# Titan_Teknic_v1p00a.net
KiCad netlist of a schematic drawn in EAGLE
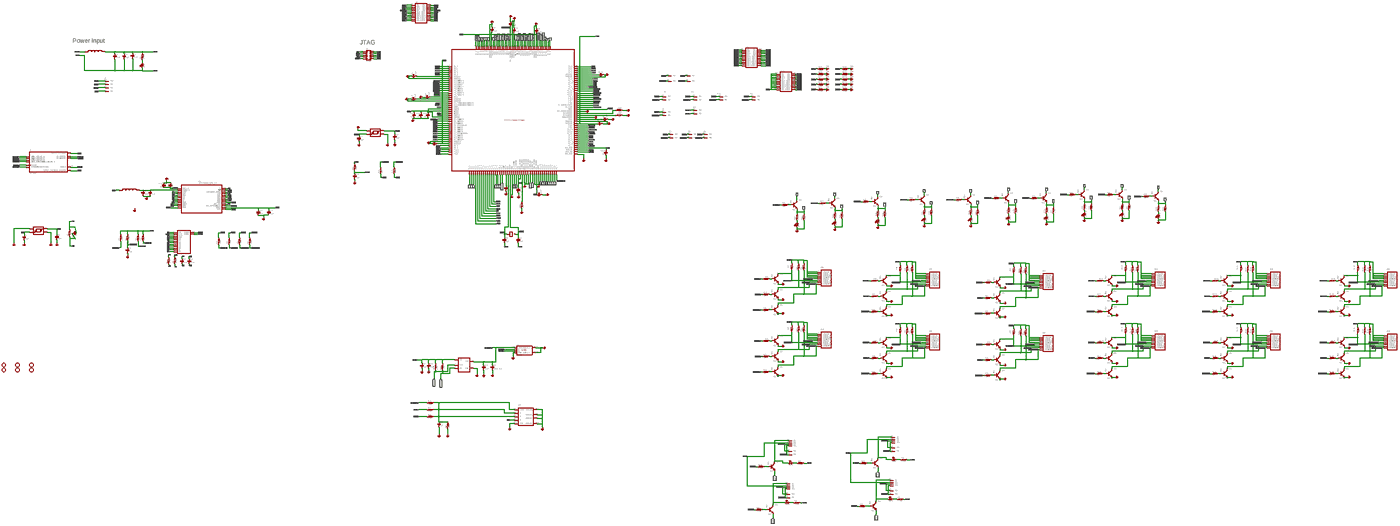
[diagram p0: schematic, sheet 1, overview]
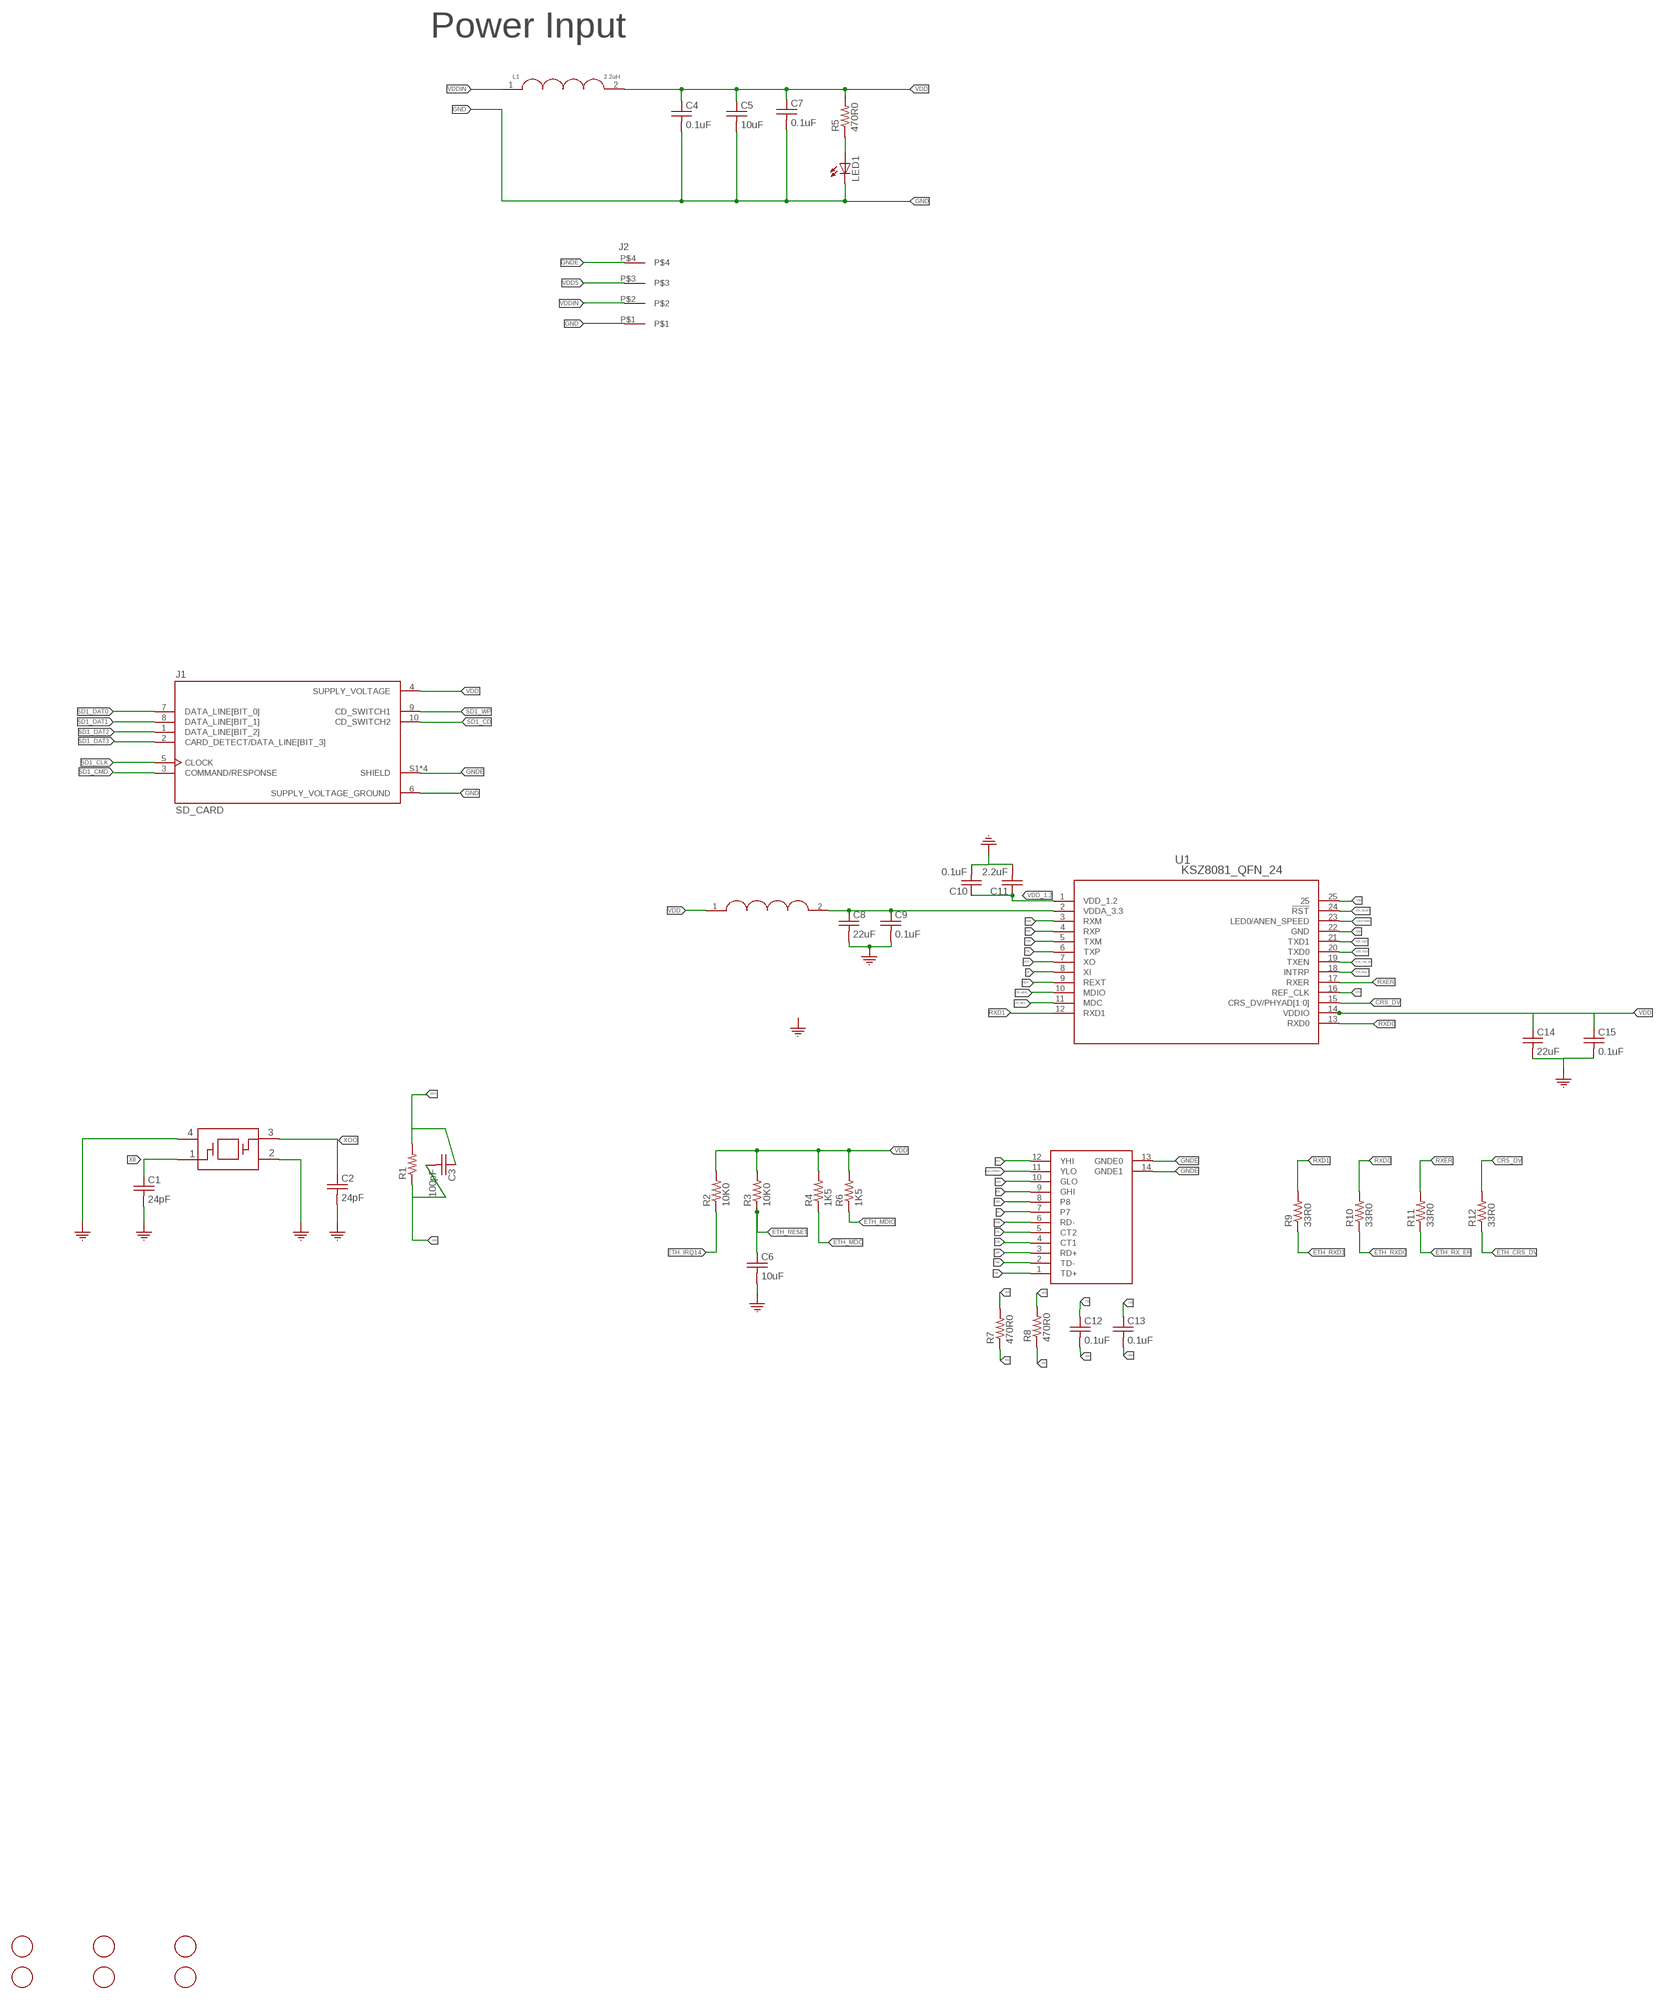
[diagram p1: schematic, sheet 1, part 1 of 6]
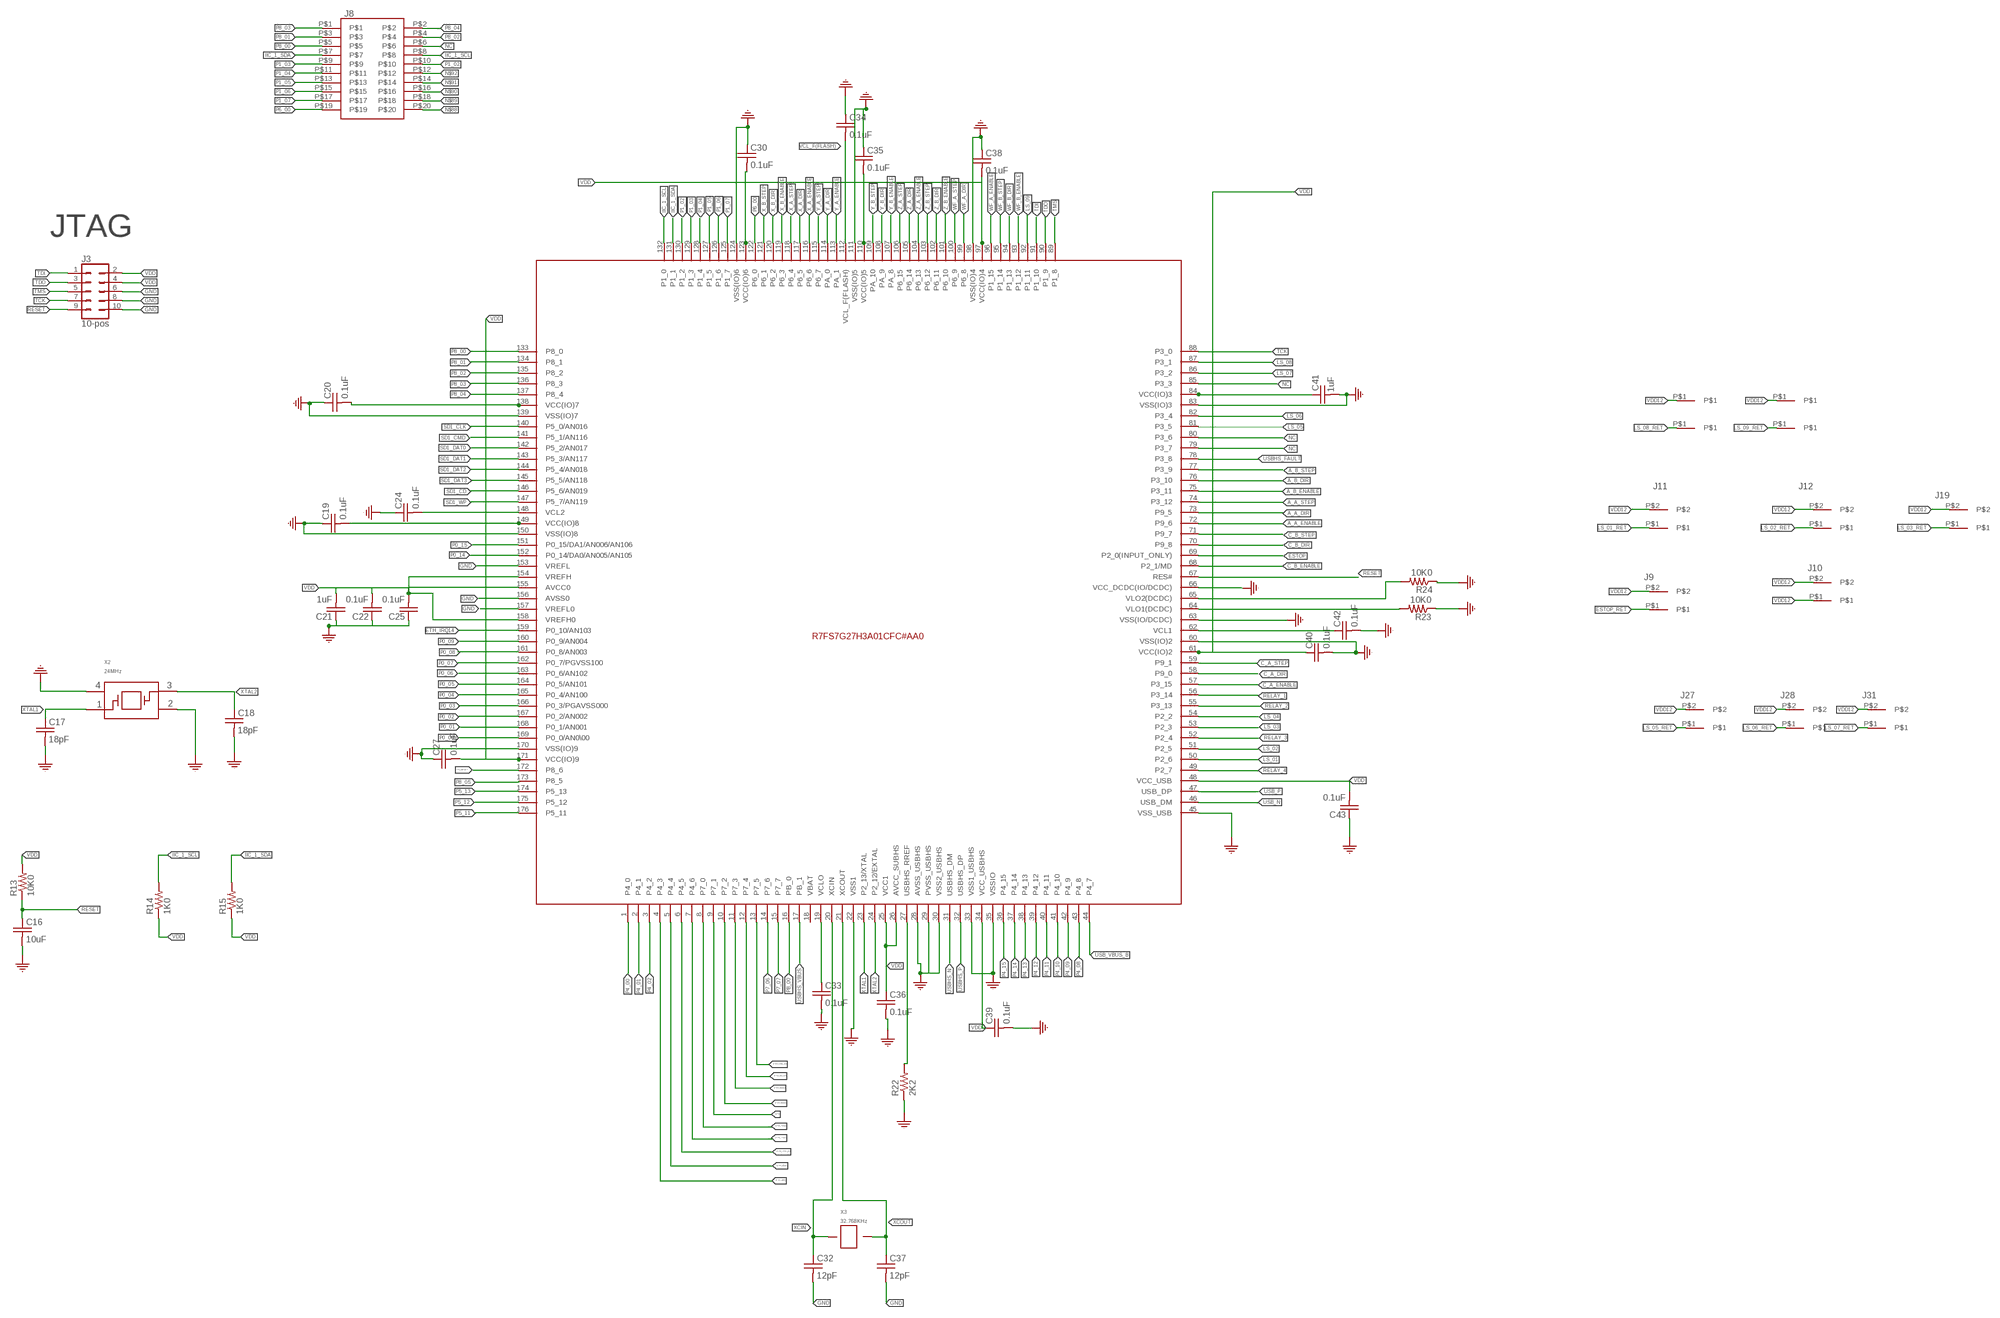
[diagram p2: schematic, sheet 1, part 2 of 6]
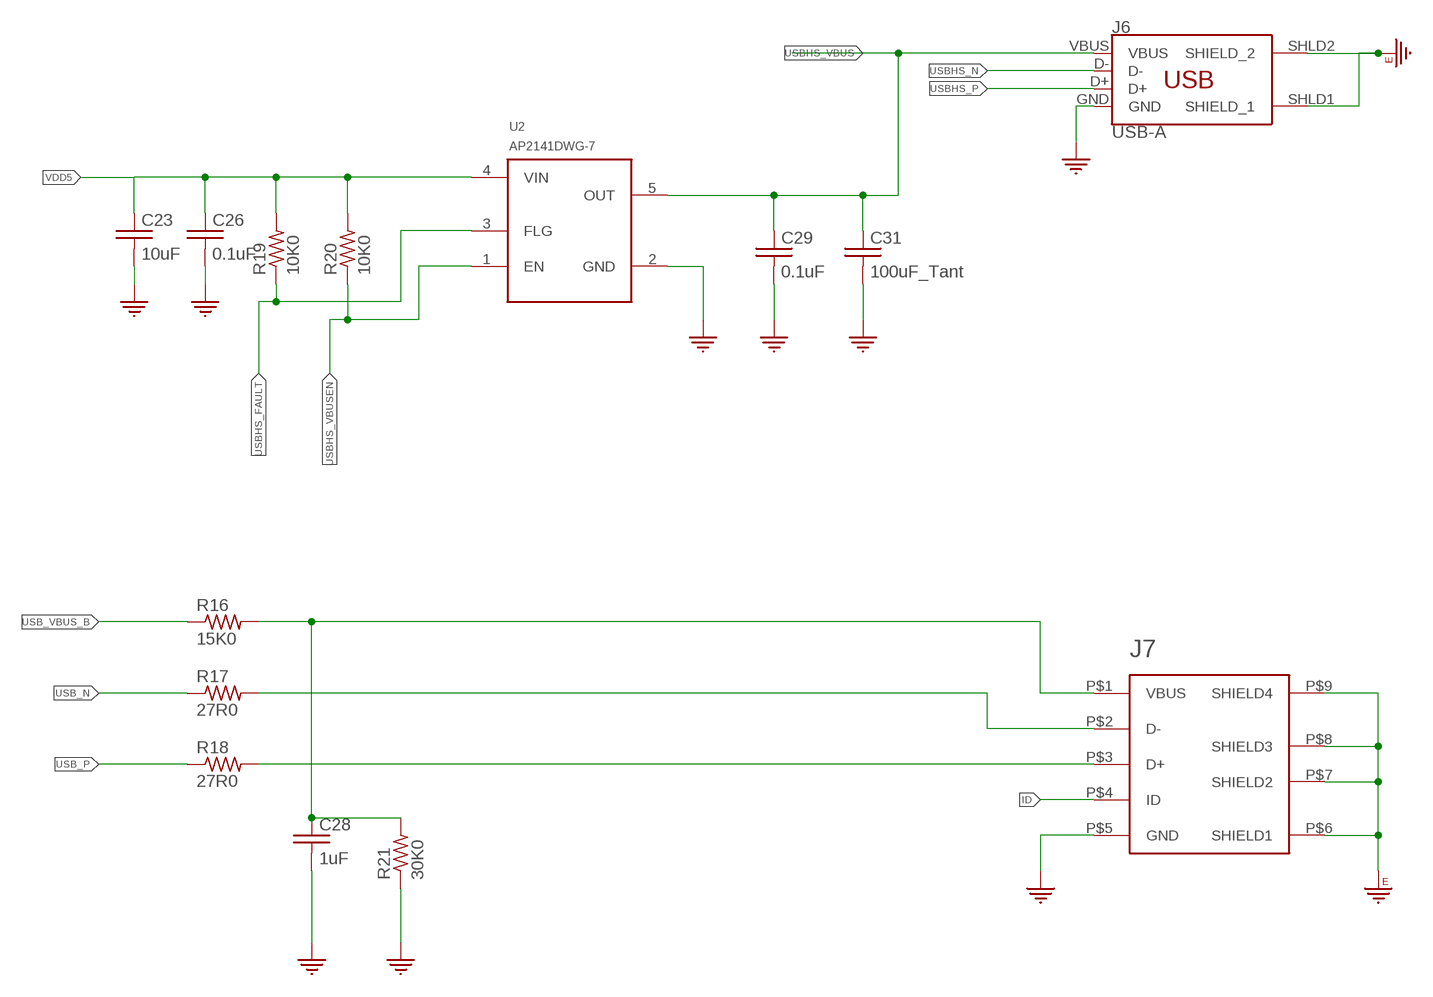
[diagram p3: schematic, sheet 1, part 3 of 6]
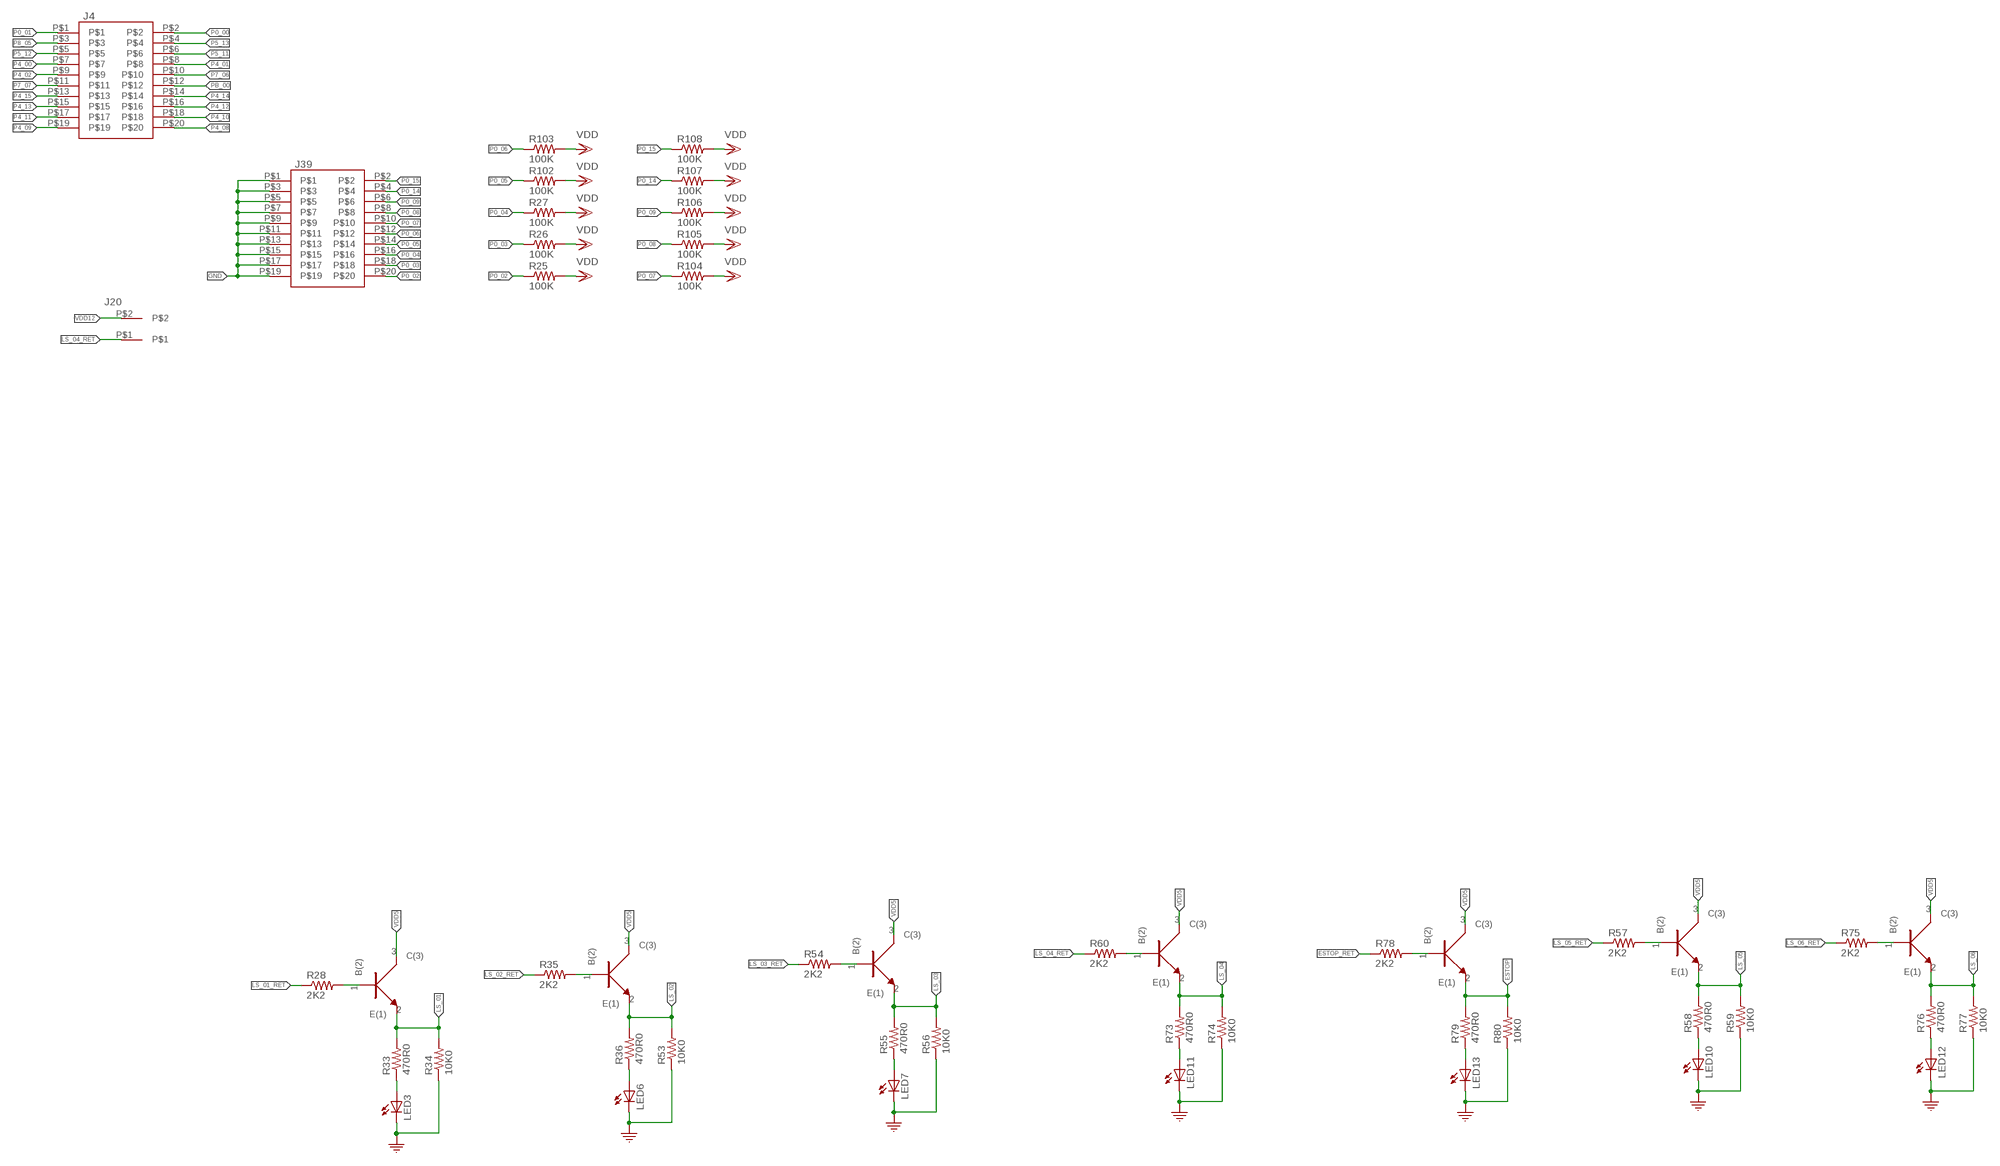
[diagram p4: schematic, sheet 1, part 4 of 6]
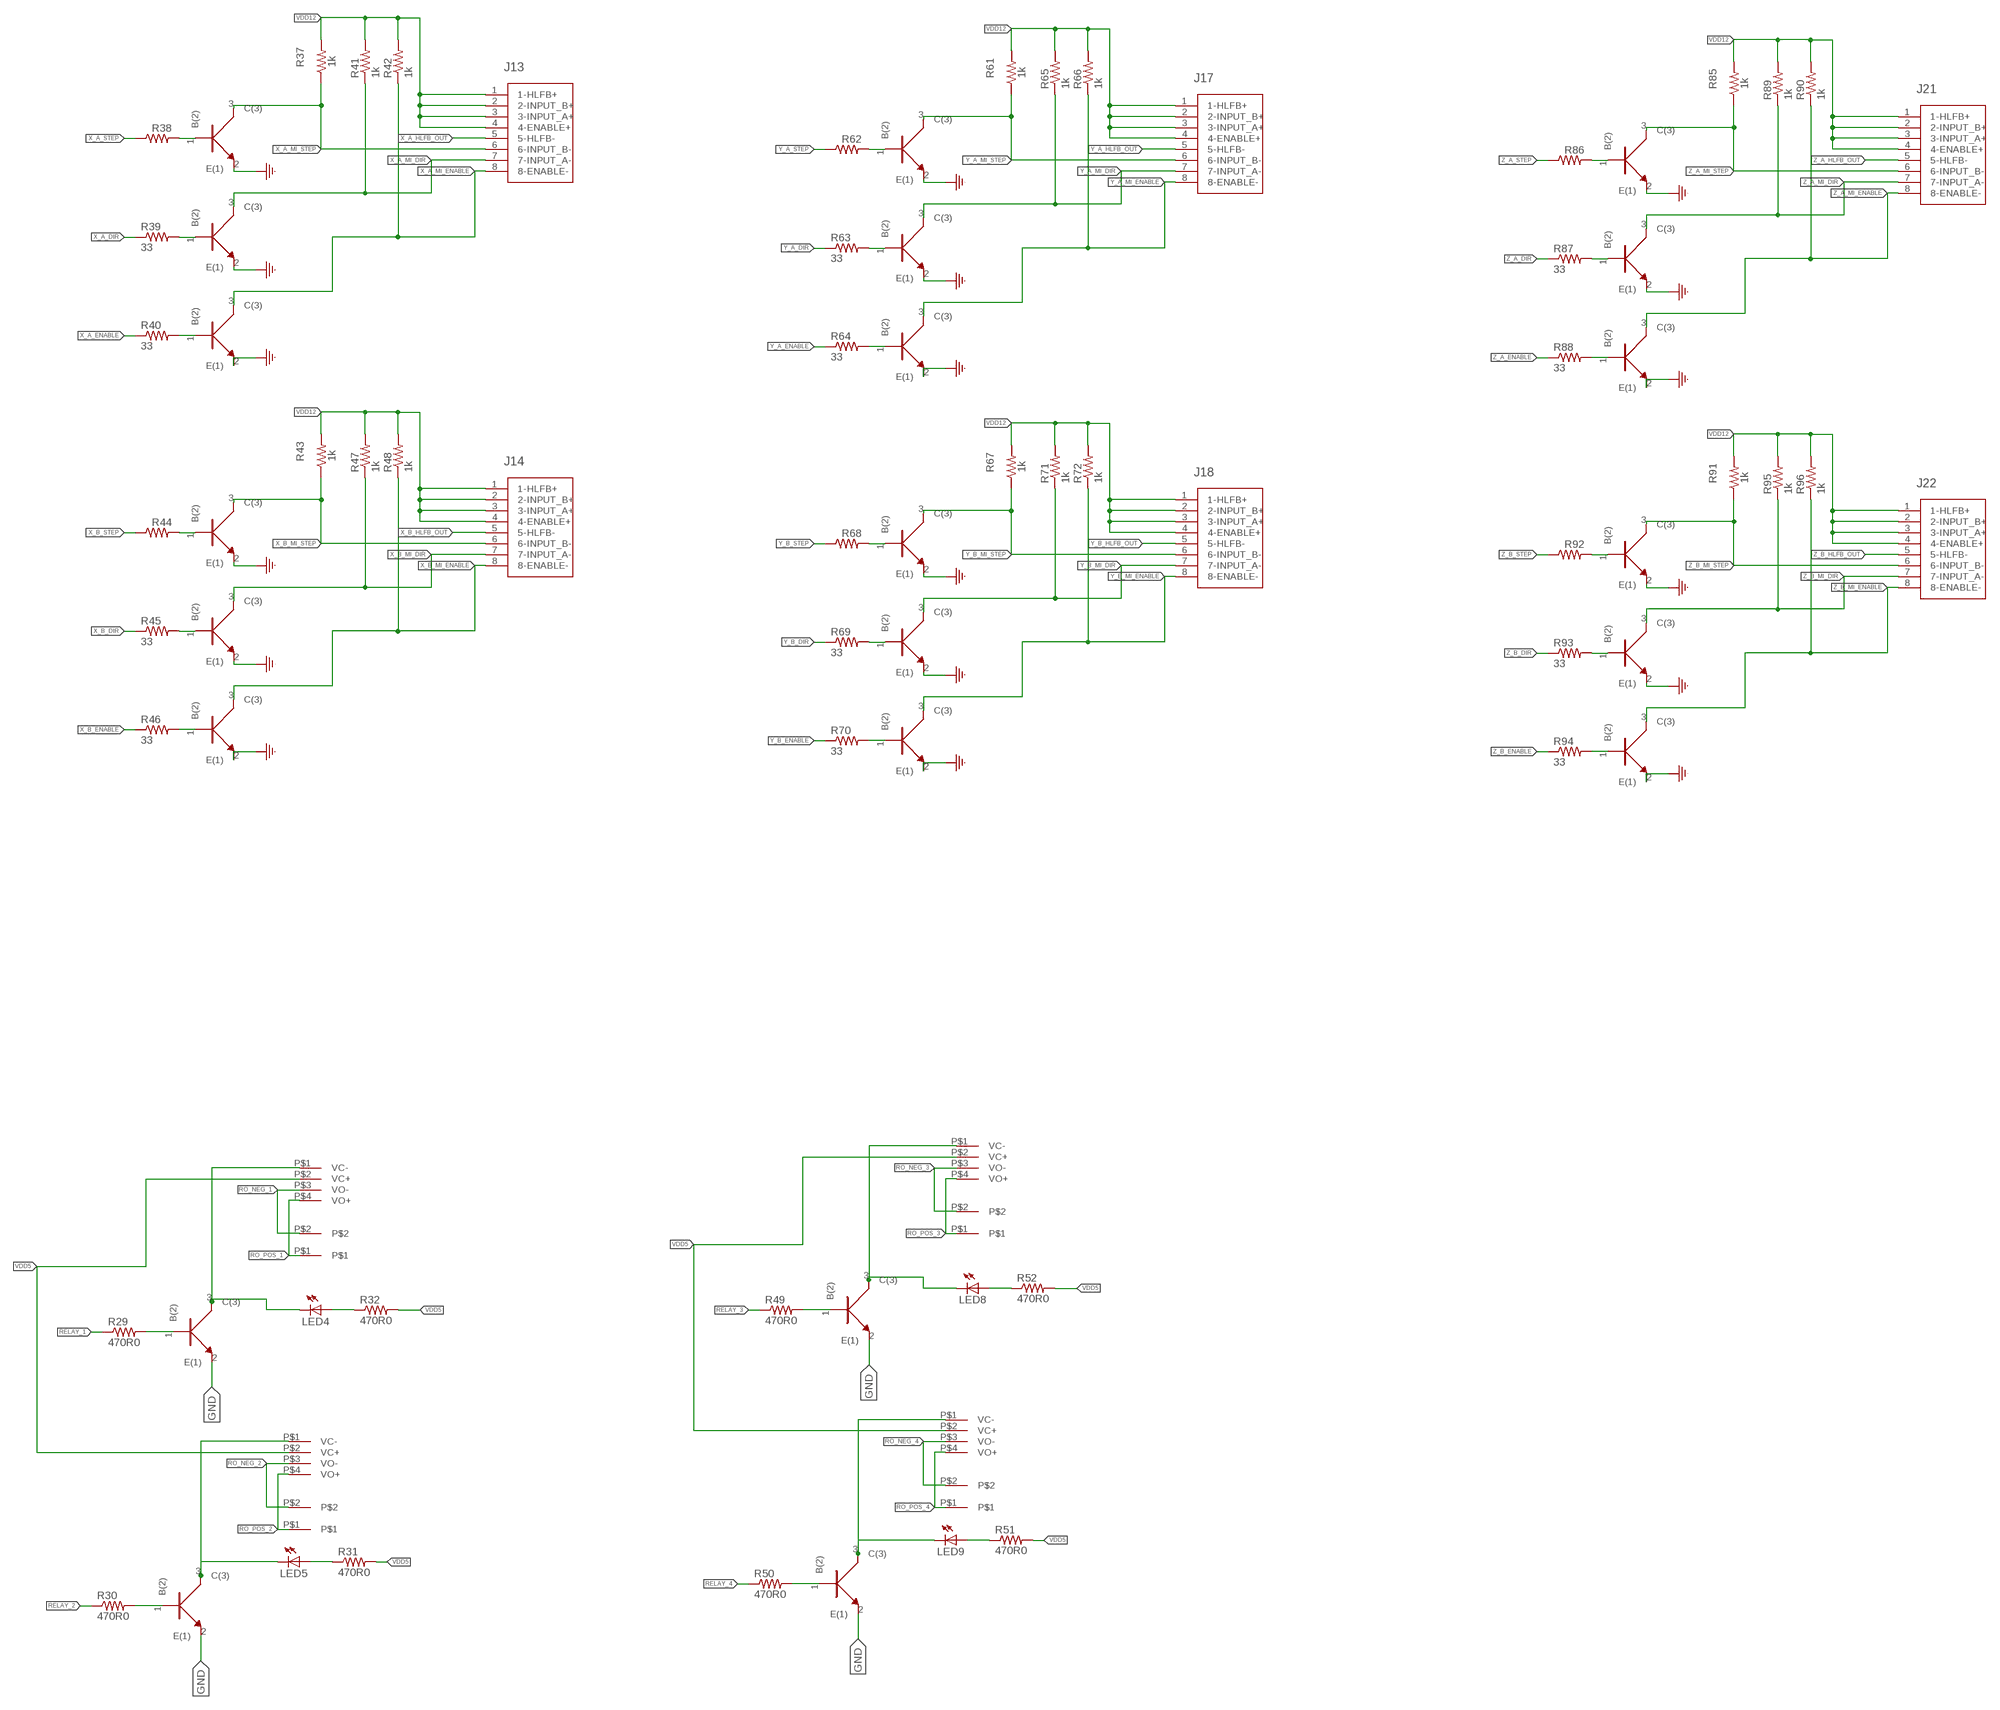
[diagram p5: schematic, sheet 1, part 5 of 6]
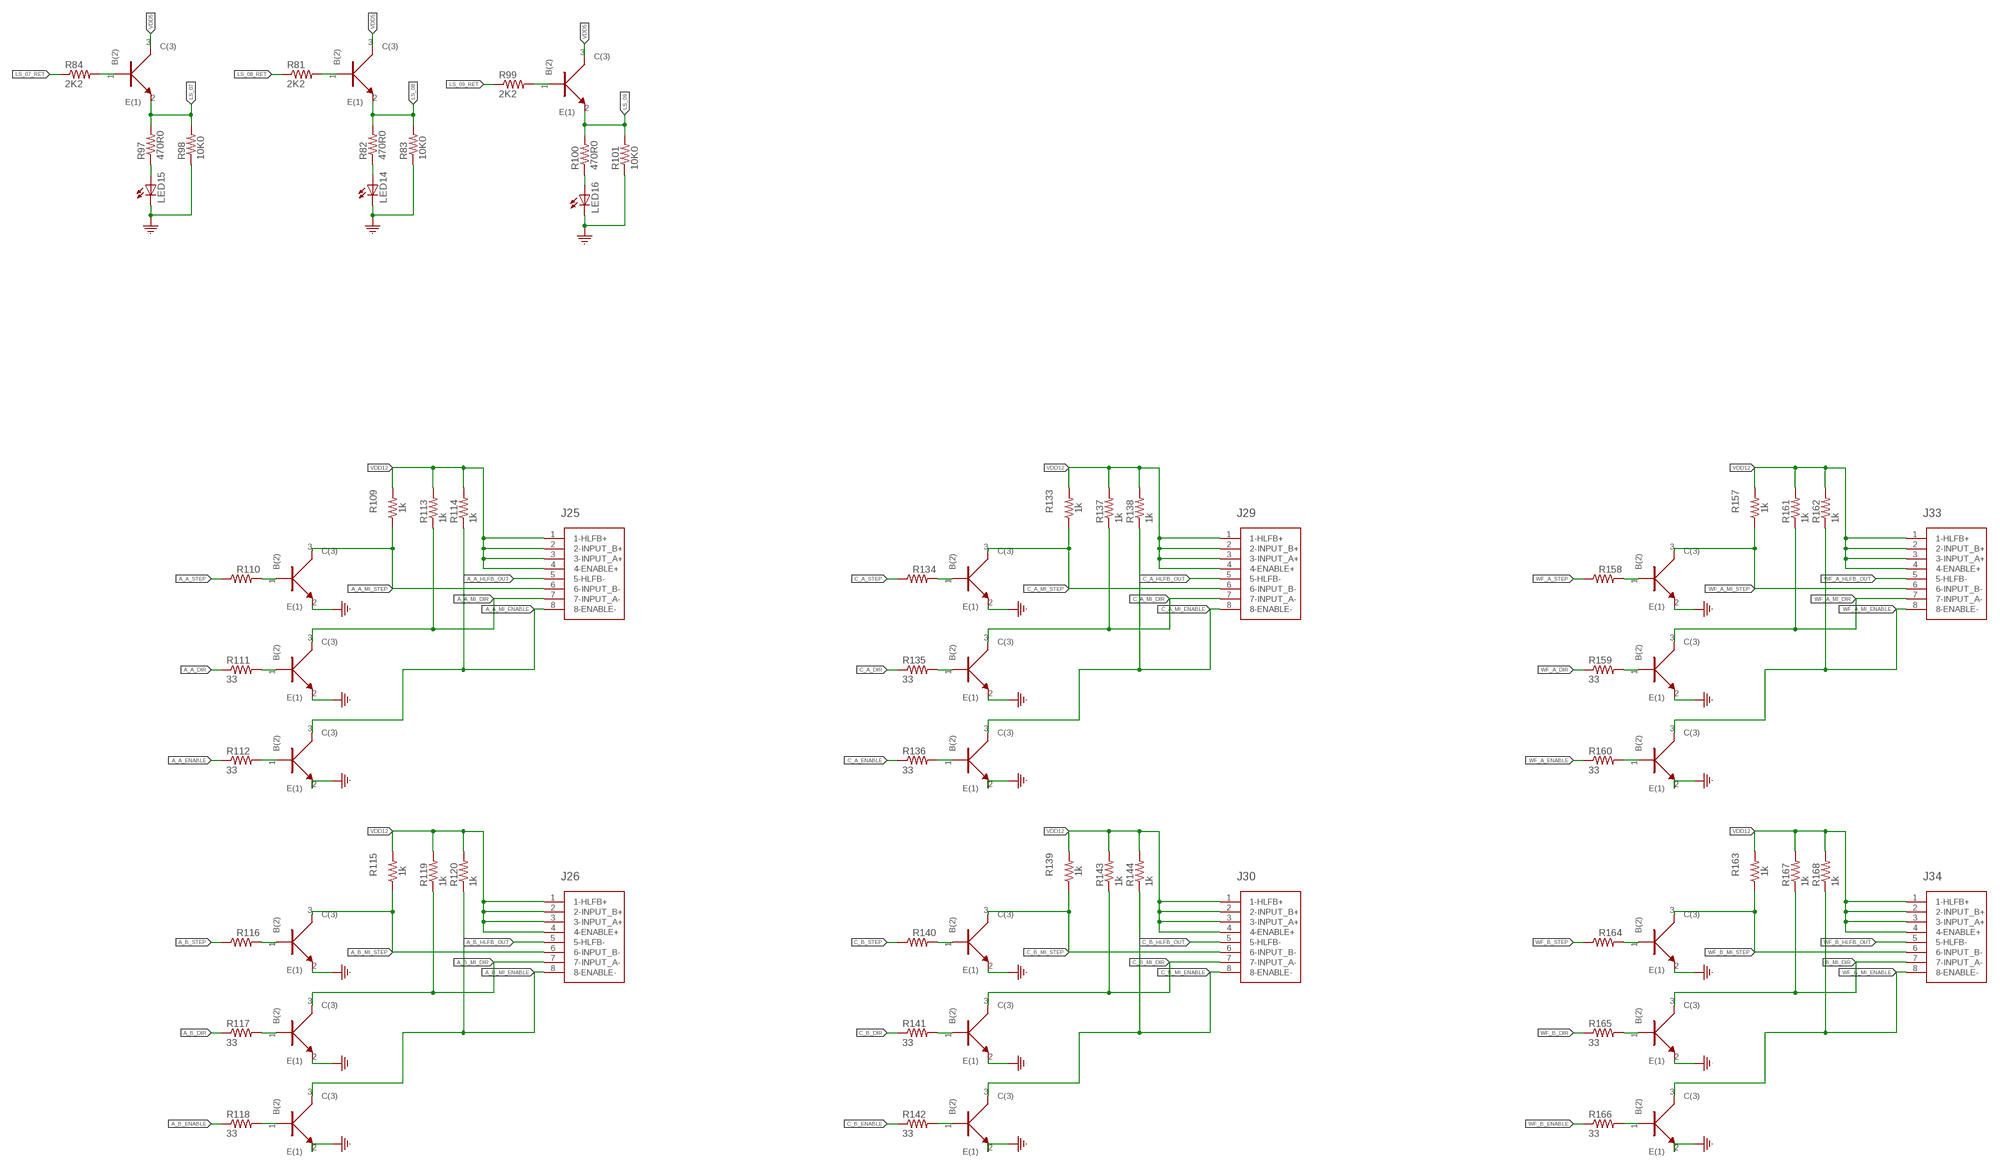
[diagram p6: schematic, sheet 1, part 6 of 6]

(export (version "E")
  (design (tool "Eeschema 10.0.6"))
  (components
    (comp (ref "AFID1")
      (value "FIDUCIAL_1MM")
      (footprint "eagle-import:FIDUCIAL_1MM")
      (libsource (lib "eagle-import") (part "FIDUCIAL_1MM"))
    )
    (comp (ref "AFID2")
      (value "FIDUCIAL_1MM")
      (footprint "eagle-import:FIDUCIAL_1MM")
      (libsource (lib "eagle-import") (part "FIDUCIAL_1MM"))
    )
    (comp (ref "AFID3")
      (value "FIDUCIAL_1MM")
      (footprint "eagle-import:FIDUCIAL_1MM")
      (libsource (lib "eagle-import") (part "FIDUCIAL_1MM"))
    )
    (comp (ref "AFID4")
      (value "FIDUCIAL_1MM")
      (footprint "eagle-import:FIDUCIAL_1MM")
      (libsource (lib "eagle-import") (part "FIDUCIAL_1MM"))
    )
    (comp (ref "AFID5")
      (value "FIDUCIAL_1MM")
      (footprint "eagle-import:FIDUCIAL_1MM")
      (libsource (lib "eagle-import") (part "FIDUCIAL_1MM"))
    )
    (comp (ref "AFID6")
      (value "FIDUCIAL_1MM")
      (footprint "eagle-import:FIDUCIAL_1MM")
      (libsource (lib "eagle-import") (part "FIDUCIAL_1MM"))
    )
    (comp (ref "C1")
      (value "24pF")
      (footprint "eagle-import:0402")
      (fields (field (name "PARTNO") "CC0402GRNPO9BN240"))
      (libsource (lib "eagle-import") (part "C_0402_24PF"))
    )
    (comp (ref "C2")
      (value "24pF")
      (footprint "eagle-import:0402")
      (fields (field (name "PARTNO") "CC0402GRNPO9BN240"))
      (libsource (lib "eagle-import") (part "C_0402_24PF"))
    )
    (comp (ref "C3")
      (value "100pF")
      (footprint "eagle-import:0402")
      (fields (field (name "PARTNO") "CL05C101JB5NNNC"))
      (libsource (lib "eagle-import") (part "C_0402_100PF"))
    )
    (comp (ref "C4")
      (value "0.1uF")
      (footprint "eagle-import:0402")
      (fields (field (name "PARTNO") "CL05F104ZO5NNNC"))
      (libsource (lib "eagle-import") (part "C_0402_0.1UF"))
    )
    (comp (ref "C5")
      (value "10uF")
      (footprint "eagle-import:0402")
      (fields (field (name "PARTNO") "CL05A106MP8NUB8"))
      (libsource (lib "eagle-import") (part "C_0402_10UF"))
    )
    (comp (ref "C6")
      (value "10uF")
      (footprint "eagle-import:0402")
      (fields (field (name "PARTNO") "CL05A106MP8NUB8"))
      (libsource (lib "eagle-import") (part "C_0402_10UF"))
    )
    (comp (ref "C7")
      (value "0.1uF")
      (footprint "eagle-import:0402")
      (fields (field (name "PARTNO") "CL05F104ZO5NNNC"))
      (libsource (lib "eagle-import") (part "C_0402_0.1UF"))
    )
    (comp (ref "C8")
      (value "22uF")
      (footprint "eagle-import:0402")
      (fields (field (name "PARTNO") "CL05A226MQ5N6J8"))
      (libsource (lib "eagle-import") (part "C_0402_22UF"))
    )
    (comp (ref "C9")
      (value "0.1uF")
      (footprint "eagle-import:0402")
      (fields (field (name "PARTNO") "CL05F104ZO5NNNC"))
      (libsource (lib "eagle-import") (part "C_0402_0.1UF"))
    )
    (comp (ref "C10")
      (value "0.1uF")
      (footprint "eagle-import:0402")
      (fields (field (name "PARTNO") "CL05F104ZO5NNNC"))
      (libsource (lib "eagle-import") (part "C_0402_0.1UF"))
    )
    (comp (ref "C11")
      (value "2.2uF")
      (footprint "eagle-import:0402")
      (fields (field (name "PARTNO") "GRM155C81C225ME15D"))
      (libsource (lib "eagle-import") (part "C_0402_2.2UF"))
    )
    (comp (ref "C12")
      (value "0.1uF")
      (footprint "eagle-import:0402")
      (fields (field (name "PARTNO") "CL05F104ZO5NNNC"))
      (libsource (lib "eagle-import") (part "C_0402_0.1UF"))
    )
    (comp (ref "C13")
      (value "0.1uF")
      (footprint "eagle-import:0402")
      (fields (field (name "PARTNO") "CL05F104ZO5NNNC"))
      (libsource (lib "eagle-import") (part "C_0402_0.1UF"))
    )
    (comp (ref "C14")
      (value "22uF")
      (footprint "eagle-import:0402")
      (fields (field (name "PARTNO") "CL05A226MQ5N6J8"))
      (libsource (lib "eagle-import") (part "C_0402_22UF"))
    )
    (comp (ref "C15")
      (value "0.1uF")
      (footprint "eagle-import:0402")
      (fields (field (name "PARTNO") "CL05F104ZO5NNNC"))
      (libsource (lib "eagle-import") (part "C_0402_0.1UF"))
    )
    (comp (ref "C16")
      (value "10uF")
      (footprint "eagle-import:0402")
      (fields (field (name "PARTNO") "CL05A106MP8NUB8"))
      (libsource (lib "eagle-import") (part "C_0402_10UF"))
    )
    (comp (ref "C17")
      (value "18pF")
      (footprint "eagle-import:0402")
      (fields (field (name "PARTNO") "UMK105CG180JV-F"))
      (libsource (lib "eagle-import") (part "C_0402_18PF"))
    )
    (comp (ref "C18")
      (value "18pF")
      (footprint "eagle-import:0402")
      (fields (field (name "PARTNO") "UMK105CG180JV-F"))
      (libsource (lib "eagle-import") (part "C_0402_18PF"))
    )
    (comp (ref "C19")
      (value "0.1uF")
      (footprint "eagle-import:0402")
      (fields (field (name "PARTNO") "CL05F104ZO5NNNC"))
      (libsource (lib "eagle-import") (part "C_0402_0.1UF"))
    )
    (comp (ref "C20")
      (value "0.1uF")
      (footprint "eagle-import:0402")
      (fields (field (name "PARTNO") "CL05F104ZO5NNNC"))
      (libsource (lib "eagle-import") (part "C_0402_0.1UF"))
    )
    (comp (ref "C21")
      (value "1uF")
      (footprint "eagle-import:0402")
      (fields (field (name "PARTNO") "CL05A105KO5NNNC"))
      (libsource (lib "eagle-import") (part "C_0402_1UF"))
    )
    (comp (ref "C22")
      (value "0.1uF")
      (footprint "eagle-import:0402")
      (fields (field (name "PARTNO") "CL05F104ZO5NNNC"))
      (libsource (lib "eagle-import") (part "C_0402_0.1UF"))
    )
    (comp (ref "C23")
      (value "10uF")
      (footprint "eagle-import:0402")
      (fields (field (name "PARTNO") "CL05A106MP8NUB8"))
      (libsource (lib "eagle-import") (part "C_0402_10UF"))
    )
    (comp (ref "C24")
      (value "0.1uF")
      (footprint "eagle-import:0402")
      (fields (field (name "PARTNO") "CL05F104ZO5NNNC"))
      (libsource (lib "eagle-import") (part "C_0402_0.1UF"))
    )
    (comp (ref "C25")
      (value "0.1uF")
      (footprint "eagle-import:0402")
      (fields (field (name "PARTNO") "CL05F104ZO5NNNC"))
      (libsource (lib "eagle-import") (part "C_0402_0.1UF"))
    )
    (comp (ref "C26")
      (value "0.1uF")
      (footprint "eagle-import:0402")
      (fields (field (name "PARTNO") "CL05F104ZO5NNNC"))
      (libsource (lib "eagle-import") (part "C_0402_0.1UF"))
    )
    (comp (ref "C27")
      (value "0.1uF")
      (footprint "eagle-import:0402")
      (fields (field (name "PARTNO") "CL05F104ZO5NNNC"))
      (libsource (lib "eagle-import") (part "C_0402_0.1UF"))
    )
    (comp (ref "C28")
      (value "1uF")
      (footprint "eagle-import:0402")
      (fields (field (name "PARTNO") "CL05A105KO5NNNC"))
      (libsource (lib "eagle-import") (part "C_0402_1UF"))
    )
    (comp (ref "C29")
      (value "0.1uF")
      (footprint "eagle-import:0402")
      (fields (field (name "PARTNO") "CL05F104ZO5NNNC"))
      (libsource (lib "eagle-import") (part "C_0402_0.1UF"))
    )
    (comp (ref "C30")
      (value "0.1uF")
      (footprint "eagle-import:0402")
      (fields (field (name "PARTNO") "CL05F104ZO5NNNC"))
      (libsource (lib "eagle-import") (part "C_0402_0.1UF"))
    )
    (comp (ref "C31")
      (value "100uF_Tant")
      (footprint "eagle-import:C1210")
      (fields (field (name "PARTNO") "TLJT107M010R0900"))
      (libsource (lib "eagle-import") (part "C_1210_100UF_TANT"))
    )
    (comp (ref "C32")
      (value "12pF")
      (footprint "eagle-import:0402")
      (fields (field (name "PARTNO") "CL05C120JB5NNNC"))
      (libsource (lib "eagle-import") (part "C_0402_12PF"))
    )
    (comp (ref "C33")
      (value "0.1uF")
      (footprint "eagle-import:0402")
      (fields (field (name "PARTNO") "CL05F104ZO5NNNC"))
      (libsource (lib "eagle-import") (part "C_0402_0.1UF"))
    )
    (comp (ref "C34")
      (value "0.1uF")
      (footprint "eagle-import:0402")
      (fields (field (name "PARTNO") "CL05F104ZO5NNNC"))
      (libsource (lib "eagle-import") (part "C_0402_0.1UF"))
    )
    (comp (ref "C35")
      (value "0.1uF")
      (footprint "eagle-import:0402")
      (fields (field (name "PARTNO") "CL05F104ZO5NNNC"))
      (libsource (lib "eagle-import") (part "C_0402_0.1UF"))
    )
    (comp (ref "C36")
      (value "0.1uF")
      (footprint "eagle-import:0402")
      (fields (field (name "PARTNO") "CL05F104ZO5NNNC"))
      (libsource (lib "eagle-import") (part "C_0402_0.1UF"))
    )
    (comp (ref "C37")
      (value "12pF")
      (footprint "eagle-import:0402")
      (fields (field (name "PARTNO") "CL05C120JB5NNNC"))
      (libsource (lib "eagle-import") (part "C_0402_12PF"))
    )
    (comp (ref "C38")
      (value "0.1uF")
      (footprint "eagle-import:0402")
      (fields (field (name "PARTNO") "CL05F104ZO5NNNC"))
      (libsource (lib "eagle-import") (part "C_0402_0.1UF"))
    )
    (comp (ref "C39")
      (value "0.1uF")
      (footprint "eagle-import:0402")
      (fields (field (name "PARTNO") "CL05F104ZO5NNNC"))
      (libsource (lib "eagle-import") (part "C_0402_0.1UF"))
    )
    (comp (ref "C40")
      (value "0.1uF")
      (footprint "eagle-import:0402")
      (fields (field (name "PARTNO") "CL05F104ZO5NNNC"))
      (libsource (lib "eagle-import") (part "C_0402_0.1UF"))
    )
    (comp (ref "C41")
      (value "1uF")
      (footprint "eagle-import:0402")
      (fields (field (name "PARTNO") "CL05A105KO5NNNC"))
      (libsource (lib "eagle-import") (part "C_0402_1UF"))
    )
    (comp (ref "C42")
      (value "0.1uF")
      (footprint "eagle-import:0402")
      (fields (field (name "PARTNO") "CL05F104ZO5NNNC"))
      (libsource (lib "eagle-import") (part "C_0402_0.1UF"))
    )
    (comp (ref "C43")
      (value "0.1uF")
      (footprint "eagle-import:0402")
      (fields (field (name "PARTNO") "CL05F104ZO5NNNC"))
      (libsource (lib "eagle-import") (part "C_0402_0.1UF"))
    )
    (comp (ref "FB1")
      (value "FB2_603")
      (footprint "eagle-import:0603")
      (fields (field (name "PARTNO") "BLM18PG121SN1D"))
      (libsource (lib "eagle-import") (part "FB_0603_120_OHM0603"))
    )
    (comp (ref "J1")
      (value "SD_CARD")
      (footprint "eagle-import:SD_CARD")
      (fields (field (name "MF") "Amphenol ICC") (field (name "PARTNO") "114-00841-68"))
      (libsource (lib "eagle-import") (part "SD_CARD_1140084168"))
    )
    (comp (ref "J2")
      (value "4-pos")
      (footprint "eagle-import:1X4_3.81MM_PITCH")
      (fields (field (name "PARTNO") "691322310004"))
      (libsource (lib "eagle-import") (part "3.81MM_1_X_4_RT_ANGLE_PLUG_HEADER"))
    )
    (comp (ref "J3")
      (value "10-pos")
      (footprint "eagle-import:2X5")
      (fields (field (name "PARTNO") "PH2RA-10-UA"))
      (libsource (lib "eagle-import") (part "CONN_05X2_RAPTH"))
    )
    (comp (ref "J4")
      (value "20-pos")
      (footprint "eagle-import:2_X_10_.1_INCH")
      (fields (field (name "PARTNO") "67996-420HLF"))
      (libsource (lib "eagle-import") (part "2_X_10_HEADER_GENERIC"))
    )
    (comp (ref "J6")
      (value "USB-A")
      (footprint "eagle-import:USB_A_SMT")
      (fields (field (name "PARTNO") "87583-3010RPALF"))
      (libsource (lib "eagle-import") (part "USB_A"))
    )
    (comp (ref "J7")
      (value "USB-B-Micro")
      (footprint "eagle-import:USB_MICRO-B")
      (fields (field (name "PARTNO") "10118192-0002LF"))
      (libsource (lib "eagle-import") (part "USB_MICRO-B"))
    )
    (comp (ref "J8")
      (value "2_X_10_HEADER_GENERIC")
      (footprint "eagle-import:2_X_10_.1_INCH")
      (fields (field (name "PARTNO") "67996-420HLF"))
      (libsource (lib "eagle-import") (part "2_X_10_HEADER_GENERIC"))
    )
    (comp (ref "J9")
      (value "2-pos")
      (footprint "eagle-import:2_3.81MM_PITCH")
      (fields (field (name "PARTNO") "691322310002"))
      (libsource (lib "eagle-import") (part "3.81MM_1_X_2_RT_ANGLE_PLUG_HEADER"))
    )
    (comp (ref "J10")
      (value "2-pos")
      (footprint "eagle-import:2_3.81MM_PITCH")
      (fields (field (name "PARTNO") "691322310002"))
      (libsource (lib "eagle-import") (part "3.81MM_1_X_2_RT_ANGLE_PLUG_HEADER"))
    )
    (comp (ref "J11")
      (value "2-pos")
      (footprint "eagle-import:2_3.81MM_PITCH")
      (fields (field (name "PARTNO") "691322310002"))
      (libsource (lib "eagle-import") (part "3.81MM_1_X_2_RT_ANGLE_PLUG_HEADER"))
    )
    (comp (ref "J12")
      (value "2-pos")
      (footprint "eagle-import:2_3.81MM_PITCH")
      (fields (field (name "PARTNO") "691322310002"))
      (libsource (lib "eagle-import") (part "3.81MM_1_X_2_RT_ANGLE_PLUG_HEADER"))
    )
    (comp (ref "J13")
      (value "TEKNIC_8PIN_MOTOR")
      (footprint "eagle-import:CON_39281083")
      (fields
        (field (name "MANUFACTURER_PART_NUMBER") "39281083")
        (field (name "COPYRIGHT") "Copyright (C) 2022 Ultra Librarian. All rights reserved.")
      )
      (libsource (lib "eagle-import") (part "TEKNIC_8PIN_MOTOR"))
    )
    (comp (ref "J14")
      (value "TEKNIC_8PIN_MOTOR")
      (footprint "eagle-import:CON_39281083")
      (fields
        (field (name "MANUFACTURER_PART_NUMBER") "39281083")
        (field (name "COPYRIGHT") "Copyright (C) 2022 Ultra Librarian. All rights reserved.")
      )
      (libsource (lib "eagle-import") (part "TEKNIC_8PIN_MOTOR"))
    )
    (comp (ref "J15")
      (value "2-pos")
      (footprint "eagle-import:2_3.81MM_PITCH")
      (fields (field (name "PARTNO") "691322310002"))
      (libsource (lib "eagle-import") (part "3.81MM_1_X_2_RT_ANGLE_PLUG_HEADER"))
    )
    (comp (ref "J16")
      (value "2-pos")
      (footprint "eagle-import:2_3.81MM_PITCH")
      (fields (field (name "PARTNO") "691322310002"))
      (libsource (lib "eagle-import") (part "3.81MM_1_X_2_RT_ANGLE_PLUG_HEADER"))
    )
    (comp (ref "J17")
      (value "TEKNIC_8PIN_MOTOR")
      (footprint "eagle-import:CON_39281083")
      (fields
        (field (name "MANUFACTURER_PART_NUMBER") "39281083")
        (field (name "COPYRIGHT") "Copyright (C) 2022 Ultra Librarian. All rights reserved.")
      )
      (libsource (lib "eagle-import") (part "TEKNIC_8PIN_MOTOR"))
    )
    (comp (ref "J18")
      (value "TEKNIC_8PIN_MOTOR")
      (footprint "eagle-import:CON_39281083")
      (fields
        (field (name "MANUFACTURER_PART_NUMBER") "39281083")
        (field (name "COPYRIGHT") "Copyright (C) 2022 Ultra Librarian. All rights reserved.")
      )
      (libsource (lib "eagle-import") (part "TEKNIC_8PIN_MOTOR"))
    )
    (comp (ref "J19")
      (value "2-pos")
      (footprint "eagle-import:2_3.81MM_PITCH")
      (fields (field (name "PARTNO") "691322310002"))
      (libsource (lib "eagle-import") (part "3.81MM_1_X_2_RT_ANGLE_PLUG_HEADER"))
    )
    (comp (ref "J20")
      (value "2-pos")
      (footprint "eagle-import:2_3.81MM_PITCH")
      (fields (field (name "PARTNO") "691322310002"))
      (libsource (lib "eagle-import") (part "3.81MM_1_X_2_RT_ANGLE_PLUG_HEADER"))
    )
    (comp (ref "J21")
      (value "TEKNIC_8PIN_MOTOR")
      (footprint "eagle-import:CON_39281083")
      (fields
        (field (name "MANUFACTURER_PART_NUMBER") "39281083")
        (field (name "COPYRIGHT") "Copyright (C) 2022 Ultra Librarian. All rights reserved.")
      )
      (libsource (lib "eagle-import") (part "TEKNIC_8PIN_MOTOR"))
    )
    (comp (ref "J22")
      (value "TEKNIC_8PIN_MOTOR")
      (footprint "eagle-import:CON_39281083")
      (fields
        (field (name "MANUFACTURER_PART_NUMBER") "39281083")
        (field (name "COPYRIGHT") "Copyright (C) 2022 Ultra Librarian. All rights reserved.")
      )
      (libsource (lib "eagle-import") (part "TEKNIC_8PIN_MOTOR"))
    )
    (comp (ref "J23")
      (value "2-pos")
      (footprint "eagle-import:2_3.81MM_PITCH")
      (fields (field (name "PARTNO") "691322310002"))
      (libsource (lib "eagle-import") (part "3.81MM_1_X_2_RT_ANGLE_PLUG_HEADER"))
    )
    (comp (ref "J24")
      (value "2-pos")
      (footprint "eagle-import:2_3.81MM_PITCH")
      (fields (field (name "PARTNO") "691322310002"))
      (libsource (lib "eagle-import") (part "3.81MM_1_X_2_RT_ANGLE_PLUG_HEADER"))
    )
    (comp (ref "J25")
      (value "TEKNIC_8PIN_MOTOR")
      (footprint "eagle-import:CON_39281083")
      (fields
        (field (name "MANUFACTURER_PART_NUMBER") "39281083")
        (field (name "COPYRIGHT") "Copyright (C) 2022 Ultra Librarian. All rights reserved.")
      )
      (libsource (lib "eagle-import") (part "TEKNIC_8PIN_MOTOR"))
    )
    (comp (ref "J26")
      (value "TEKNIC_8PIN_MOTOR")
      (footprint "eagle-import:CON_39281083")
      (fields
        (field (name "MANUFACTURER_PART_NUMBER") "39281083")
        (field (name "COPYRIGHT") "Copyright (C) 2022 Ultra Librarian. All rights reserved.")
      )
      (libsource (lib "eagle-import") (part "TEKNIC_8PIN_MOTOR"))
    )
    (comp (ref "J27")
      (value "2-pos")
      (footprint "eagle-import:2_3.81MM_PITCH")
      (fields (field (name "PARTNO") "691322310002"))
      (libsource (lib "eagle-import") (part "3.81MM_1_X_2_RT_ANGLE_PLUG_HEADER"))
    )
    (comp (ref "J28")
      (value "2-pos")
      (footprint "eagle-import:2_3.81MM_PITCH")
      (fields (field (name "PARTNO") "691322310002"))
      (libsource (lib "eagle-import") (part "3.81MM_1_X_2_RT_ANGLE_PLUG_HEADER"))
    )
    (comp (ref "J29")
      (value "TEKNIC_8PIN_MOTOR")
      (footprint "eagle-import:CON_39281083")
      (fields
        (field (name "MANUFACTURER_PART_NUMBER") "39281083")
        (field (name "COPYRIGHT") "Copyright (C) 2022 Ultra Librarian. All rights reserved.")
      )
      (libsource (lib "eagle-import") (part "TEKNIC_8PIN_MOTOR"))
    )
    (comp (ref "J30")
      (value "TEKNIC_8PIN_MOTOR")
      (footprint "eagle-import:CON_39281083")
      (fields
        (field (name "MANUFACTURER_PART_NUMBER") "39281083")
        (field (name "COPYRIGHT") "Copyright (C) 2022 Ultra Librarian. All rights reserved.")
      )
      (libsource (lib "eagle-import") (part "TEKNIC_8PIN_MOTOR"))
    )
    (comp (ref "J31")
      (value "2-pos")
      (footprint "eagle-import:2_3.81MM_PITCH")
      (fields (field (name "PARTNO") "691322310002"))
      (libsource (lib "eagle-import") (part "3.81MM_1_X_2_RT_ANGLE_PLUG_HEADER"))
    )
    (comp (ref "J33")
      (value "TEKNIC_8PIN_MOTOR")
      (footprint "eagle-import:CON_39281083")
      (fields
        (field (name "MANUFACTURER_PART_NUMBER") "39281083")
        (field (name "COPYRIGHT") "Copyright (C) 2022 Ultra Librarian. All rights reserved.")
      )
      (libsource (lib "eagle-import") (part "TEKNIC_8PIN_MOTOR"))
    )
    (comp (ref "J34")
      (value "TEKNIC_8PIN_MOTOR")
      (footprint "eagle-import:CON_39281083")
      (fields
        (field (name "MANUFACTURER_PART_NUMBER") "39281083")
        (field (name "COPYRIGHT") "Copyright (C) 2022 Ultra Librarian. All rights reserved.")
      )
      (libsource (lib "eagle-import") (part "TEKNIC_8PIN_MOTOR"))
    )
    (comp (ref "J39")
      (value "2_X_10_HEADER_GENERIC")
      (footprint "eagle-import:2_X_10_.1_INCH")
      (fields (field (name "PARTNO") "67996-420HLF"))
      (libsource (lib "eagle-import") (part "2_X_10_HEADER_GENERIC"))
    )
    (comp (ref "L1")
      (value "2.2uH")
      (footprint "eagle-import:1008")
      (fields (field (name "PARTNO") "LQM2HPN2R2MG0L"))
      (libsource (lib "eagle-import") (part "INDUCTOR_1008_2.2_MH_1.3A"))
    )
    (comp (ref "LED1")
      (value "Green")
      (footprint "eagle-import:0805")
      (fields (field (name "PARTNO") "LG R971-KN-1"))
      (libsource (lib "eagle-import") (part "LED_0805_GREEN"))
    )
    (comp (ref "LED3")
      (value "Green")
      (footprint "eagle-import:0805")
      (fields (field (name "PARTNO") "LG R971-KN-1"))
      (libsource (lib "eagle-import") (part "LED_0805_GREEN"))
    )
    (comp (ref "LED4")
      (value "Green")
      (footprint "eagle-import:0805")
      (fields (field (name "PARTNO") "LG R971-KN-1"))
      (libsource (lib "eagle-import") (part "LED_0805_GREEN"))
    )
    (comp (ref "LED5")
      (value "Green")
      (footprint "eagle-import:0805")
      (fields (field (name "PARTNO") "LG R971-KN-1"))
      (libsource (lib "eagle-import") (part "LED_0805_GREEN"))
    )
    (comp (ref "LED6")
      (value "Green")
      (footprint "eagle-import:0805")
      (fields (field (name "PARTNO") "LG R971-KN-1"))
      (libsource (lib "eagle-import") (part "LED_0805_GREEN"))
    )
    (comp (ref "LED7")
      (value "Green")
      (footprint "eagle-import:0805")
      (fields (field (name "PARTNO") "LG R971-KN-1"))
      (libsource (lib "eagle-import") (part "LED_0805_GREEN"))
    )
    (comp (ref "LED8")
      (value "Green")
      (footprint "eagle-import:0805")
      (fields (field (name "PARTNO") "LG R971-KN-1"))
      (libsource (lib "eagle-import") (part "LED_0805_GREEN"))
    )
    (comp (ref "LED9")
      (value "Green")
      (footprint "eagle-import:0805")
      (fields (field (name "PARTNO") "LG R971-KN-1"))
      (libsource (lib "eagle-import") (part "LED_0805_GREEN"))
    )
    (comp (ref "LED10")
      (value "Green")
      (footprint "eagle-import:0805")
      (fields (field (name "PARTNO") "LG R971-KN-1"))
      (libsource (lib "eagle-import") (part "LED_0805_GREEN"))
    )
    (comp (ref "LED11")
      (value "Green")
      (footprint "eagle-import:0805")
      (fields (field (name "PARTNO") "LG R971-KN-1"))
      (libsource (lib "eagle-import") (part "LED_0805_GREEN"))
    )
    (comp (ref "LED12")
      (value "Green")
      (footprint "eagle-import:0805")
      (fields (field (name "PARTNO") "LG R971-KN-1"))
      (libsource (lib "eagle-import") (part "LED_0805_GREEN"))
    )
    (comp (ref "LED13")
      (value "Green")
      (footprint "eagle-import:0805")
      (fields (field (name "PARTNO") "LG R971-KN-1"))
      (libsource (lib "eagle-import") (part "LED_0805_GREEN"))
    )
    (comp (ref "LED14")
      (value "Green")
      (footprint "eagle-import:0805")
      (fields (field (name "PARTNO") "LG R971-KN-1"))
      (libsource (lib "eagle-import") (part "LED_0805_GREEN"))
    )
    (comp (ref "LED15")
      (value "Green")
      (footprint "eagle-import:0805")
      (fields (field (name "PARTNO") "LG R971-KN-1"))
      (libsource (lib "eagle-import") (part "LED_0805_GREEN"))
    )
    (comp (ref "LED16")
      (value "Green")
      (footprint "eagle-import:0805")
      (fields (field (name "PARTNO") "LG R971-KN-1"))
      (libsource (lib "eagle-import") (part "LED_0805_GREEN"))
    )
    (comp (ref "P1")
      (value "1_X_1_1MM_PIN")
      (footprint "eagle-import:1_X_1_1MM_PIN")
      (libsource (lib "eagle-import") (part "1_X_1_1MM_PIN"))
    )
    (comp (ref "P2")
      (value "1_X_1_1MM_PIN")
      (footprint "eagle-import:1_X_1_1MM_PIN")
      (libsource (lib "eagle-import") (part "1_X_1_1MM_PIN"))
    )
    (comp (ref "P3")
      (value "1_X_1_1MM_PIN")
      (footprint "eagle-import:1_X_1_1MM_PIN")
      (libsource (lib "eagle-import") (part "1_X_1_1MM_PIN"))
    )
    (comp (ref "P4")
      (value "1_X_1_1MM_PIN")
      (footprint "eagle-import:1_X_1_1MM_PIN")
      (libsource (lib "eagle-import") (part "1_X_1_1MM_PIN"))
    )
    (comp (ref "R1")
      (value "6K49")
      (footprint "eagle-import:0402")
      (fields (field (name "PARTNO") "RMCF0402FT6K49"))
      (libsource (lib "eagle-import") (part "R_0402_6K49"))
    )
    (comp (ref "R2")
      (value "10K0")
      (footprint "eagle-import:0402")
      (fields (field (name "PARTNO") "RMCF0402JT10K0"))
      (libsource (lib "eagle-import") (part "R_0402_10K0"))
    )
    (comp (ref "R3")
      (value "10K0")
      (footprint "eagle-import:0402")
      (fields (field (name "PARTNO") "RMCF0402JT10K0"))
      (libsource (lib "eagle-import") (part "R_0402_10K0"))
    )
    (comp (ref "R4")
      (value "1K5")
      (footprint "eagle-import:0402")
      (fields (field (name "PARTNO") "RMCF0402JT1K50"))
      (libsource (lib "eagle-import") (part "R_0402_1K5"))
    )
    (comp (ref "R5")
      (value "470R0")
      (footprint "eagle-import:0402")
      (fields (field (name "PARTNO") "RMCF0402JT470R"))
      (libsource (lib "eagle-import") (part "R_0402_470R0"))
    )
    (comp (ref "R6")
      (value "1K5")
      (footprint "eagle-import:0402")
      (fields (field (name "PARTNO") "RMCF0402JT1K50"))
      (libsource (lib "eagle-import") (part "R_0402_1K5"))
    )
    (comp (ref "R7")
      (value "470R0")
      (footprint "eagle-import:0402")
      (fields (field (name "PARTNO") "RMCF0402JT470R"))
      (libsource (lib "eagle-import") (part "R_0402_470R0"))
    )
    (comp (ref "R8")
      (value "470R0")
      (footprint "eagle-import:0402")
      (fields (field (name "PARTNO") "RMCF0402JT470R"))
      (libsource (lib "eagle-import") (part "R_0402_470R0"))
    )
    (comp (ref "R9")
      (value "33R0")
      (footprint "eagle-import:0402")
      (fields (field (name "PARTNO") "RMCF0402JT33R0"))
      (libsource (lib "eagle-import") (part "R_0402_33R0"))
    )
    (comp (ref "R10")
      (value "33R0")
      (footprint "eagle-import:0402")
      (fields (field (name "PARTNO") "RMCF0402JT33R0"))
      (libsource (lib "eagle-import") (part "R_0402_33R0"))
    )
    (comp (ref "R11")
      (value "33R0")
      (footprint "eagle-import:0402")
      (fields (field (name "PARTNO") "RMCF0402JT33R0"))
      (libsource (lib "eagle-import") (part "R_0402_33R0"))
    )
    (comp (ref "R12")
      (value "33R0")
      (footprint "eagle-import:0402")
      (fields (field (name "PARTNO") "RMCF0402JT33R0"))
      (libsource (lib "eagle-import") (part "R_0402_33R0"))
    )
    (comp (ref "R13")
      (value "10K0")
      (footprint "eagle-import:0402")
      (fields (field (name "PARTNO") "RMCF0402JT10K0"))
      (libsource (lib "eagle-import") (part "R_0402_10K0"))
    )
    (comp (ref "R14")
      (value "1K0")
      (footprint "eagle-import:0402")
      (fields (field (name "PARTNO") "CRG0402J1K0"))
      (libsource (lib "eagle-import") (part "R_0402_1K0"))
    )
    (comp (ref "R15")
      (value "1K0")
      (footprint "eagle-import:0402")
      (fields (field (name "PARTNO") "CRG0402J1K0"))
      (libsource (lib "eagle-import") (part "R_0402_1K0"))
    )
    (comp (ref "R16")
      (value "15K0")
      (footprint "eagle-import:0402")
      (fields (field (name "PARTNO") "RMCF0402JT15K0"))
      (libsource (lib "eagle-import") (part "R_0402_15K0"))
    )
    (comp (ref "R17")
      (value "27R0")
      (footprint "eagle-import:0402")
      (fields (field (name "PARTNO") "RMCF0402JT27R0"))
      (libsource (lib "eagle-import") (part "R_0402_27R0"))
    )
    (comp (ref "R18")
      (value "27R0")
      (footprint "eagle-import:0402")
      (fields (field (name "PARTNO") "RMCF0402JT27R0"))
      (libsource (lib "eagle-import") (part "R_0402_27R0"))
    )
    (comp (ref "R19")
      (value "10K0")
      (footprint "eagle-import:0402")
      (fields (field (name "PARTNO") "RMCF0402JT10K0"))
      (libsource (lib "eagle-import") (part "R_0402_10K0"))
    )
    (comp (ref "R20")
      (value "10K0")
      (footprint "eagle-import:0402")
      (fields (field (name "PARTNO") "RMCF0402JT10K0"))
      (libsource (lib "eagle-import") (part "R_0402_10K0"))
    )
    (comp (ref "R21")
      (value "30K0")
      (footprint "eagle-import:0402")
      (fields (field (name "PARTNO") "RC0402JR-0730KL"))
      (libsource (lib "eagle-import") (part "R_0402_30K0"))
    )
    (comp (ref "R22")
      (value "2K2")
      (footprint "eagle-import:0402")
      (fields (field (name "PARTNO") "RMCF0402JT2K20"))
      (libsource (lib "eagle-import") (part "R_0402_2K2"))
    )
    (comp (ref "R23")
      (value "10K0")
      (footprint "eagle-import:0402")
      (fields (field (name "PARTNO") "RMCF0402JT10K0"))
      (libsource (lib "eagle-import") (part "R_0402_10K0"))
    )
    (comp (ref "R24")
      (value "10K0")
      (footprint "eagle-import:0402")
      (fields (field (name "PARTNO") "RMCF0402JT10K0"))
      (libsource (lib "eagle-import") (part "R_0402_10K0"))
    )
    (comp (ref "R25")
      (value "100K")
      (footprint "eagle-import:0402")
      (libsource (lib "eagle-import") (part "R_0402"))
    )
    (comp (ref "R26")
      (value "100K")
      (footprint "eagle-import:0402")
      (libsource (lib "eagle-import") (part "R_0402"))
    )
    (comp (ref "R27")
      (value "100K")
      (footprint "eagle-import:0402")
      (libsource (lib "eagle-import") (part "R_0402"))
    )
    (comp (ref "R28")
      (value "2K2")
      (footprint "eagle-import:0402")
      (libsource (lib "eagle-import") (part "R_0402"))
    )
    (comp (ref "R29")
      (value "470R0")
      (footprint "eagle-import:0402")
      (libsource (lib "eagle-import") (part "R_0402"))
    )
    (comp (ref "R30")
      (value "470R0")
      (footprint "eagle-import:0402")
      (libsource (lib "eagle-import") (part "R_0402"))
    )
    (comp (ref "R31")
      (value "470R0")
      (footprint "eagle-import:0402")
      (fields (field (name "PARTNO") "RMCF0402JT470R"))
      (libsource (lib "eagle-import") (part "R_0402_470R0"))
    )
    (comp (ref "R32")
      (value "470R0")
      (footprint "eagle-import:0402")
      (fields (field (name "PARTNO") "RMCF0402JT470R"))
      (libsource (lib "eagle-import") (part "R_0402_470R0"))
    )
    (comp (ref "R33")
      (value "470R0")
      (footprint "eagle-import:0402")
      (fields (field (name "PARTNO") "RMCF0402JT470R"))
      (libsource (lib "eagle-import") (part "R_0402_470R0"))
    )
    (comp (ref "R34")
      (value "10K0")
      (footprint "eagle-import:0402")
      (fields (field (name "PARTNO") "RMCF0402JT10K0"))
      (libsource (lib "eagle-import") (part "R_0402_10K0"))
    )
    (comp (ref "R35")
      (value "2K2")
      (footprint "eagle-import:0402")
      (libsource (lib "eagle-import") (part "R_0402"))
    )
    (comp (ref "R36")
      (value "470R0")
      (footprint "eagle-import:0402")
      (fields (field (name "PARTNO") "RMCF0402JT470R"))
      (libsource (lib "eagle-import") (part "R_0402_470R0"))
    )
    (comp (ref "R37")
      (value "1k")
      (footprint "eagle-import:0805")
      (libsource (lib "eagle-import") (part "R_0805"))
    )
    (comp (ref "R38")
      (value "33")
      (footprint "eagle-import:0805")
      (libsource (lib "eagle-import") (part "R_0805"))
    )
    (comp (ref "R39")
      (value "33")
      (footprint "eagle-import:0805")
      (libsource (lib "eagle-import") (part "R_0805"))
    )
    (comp (ref "R40")
      (value "33")
      (footprint "eagle-import:0805")
      (libsource (lib "eagle-import") (part "R_0805"))
    )
    (comp (ref "R41")
      (value "1k")
      (footprint "eagle-import:0805")
      (libsource (lib "eagle-import") (part "R_0805"))
    )
    (comp (ref "R42")
      (value "1k")
      (footprint "eagle-import:0805")
      (libsource (lib "eagle-import") (part "R_0805"))
    )
    (comp (ref "R43")
      (value "1k")
      (footprint "eagle-import:0805")
      (libsource (lib "eagle-import") (part "R_0805"))
    )
    (comp (ref "R44")
      (value "33")
      (footprint "eagle-import:0805")
      (libsource (lib "eagle-import") (part "R_0805"))
    )
    (comp (ref "R45")
      (value "33")
      (footprint "eagle-import:0805")
      (libsource (lib "eagle-import") (part "R_0805"))
    )
    (comp (ref "R46")
      (value "33")
      (footprint "eagle-import:0805")
      (libsource (lib "eagle-import") (part "R_0805"))
    )
    (comp (ref "R47")
      (value "1k")
      (footprint "eagle-import:0805")
      (libsource (lib "eagle-import") (part "R_0805"))
    )
    (comp (ref "R48")
      (value "1k")
      (footprint "eagle-import:0805")
      (libsource (lib "eagle-import") (part "R_0805"))
    )
    (comp (ref "R49")
      (value "470R0")
      (footprint "eagle-import:0402")
      (libsource (lib "eagle-import") (part "R_0402"))
    )
    (comp (ref "R50")
      (value "470R0")
      (footprint "eagle-import:0402")
      (libsource (lib "eagle-import") (part "R_0402"))
    )
    (comp (ref "R51")
      (value "470R0")
      (footprint "eagle-import:0402")
      (fields (field (name "PARTNO") "RMCF0402JT470R"))
      (libsource (lib "eagle-import") (part "R_0402_470R0"))
    )
    (comp (ref "R52")
      (value "470R0")
      (footprint "eagle-import:0402")
      (fields (field (name "PARTNO") "RMCF0402JT470R"))
      (libsource (lib "eagle-import") (part "R_0402_470R0"))
    )
    (comp (ref "R53")
      (value "10K0")
      (footprint "eagle-import:0402")
      (fields (field (name "PARTNO") "RMCF0402JT10K0"))
      (libsource (lib "eagle-import") (part "R_0402_10K0"))
    )
    (comp (ref "R54")
      (value "2K2")
      (footprint "eagle-import:0402")
      (libsource (lib "eagle-import") (part "R_0402"))
    )
    (comp (ref "R55")
      (value "470R0")
      (footprint "eagle-import:0402")
      (fields (field (name "PARTNO") "RMCF0402JT470R"))
      (libsource (lib "eagle-import") (part "R_0402_470R0"))
    )
    (comp (ref "R56")
      (value "10K0")
      (footprint "eagle-import:0402")
      (fields (field (name "PARTNO") "RMCF0402JT10K0"))
      (libsource (lib "eagle-import") (part "R_0402_10K0"))
    )
    (comp (ref "R57")
      (value "2K2")
      (footprint "eagle-import:0402")
      (libsource (lib "eagle-import") (part "R_0402"))
    )
    (comp (ref "R58")
      (value "470R0")
      (footprint "eagle-import:0402")
      (fields (field (name "PARTNO") "RMCF0402JT470R"))
      (libsource (lib "eagle-import") (part "R_0402_470R0"))
    )
    (comp (ref "R59")
      (value "10K0")
      (footprint "eagle-import:0402")
      (fields (field (name "PARTNO") "RMCF0402JT10K0"))
      (libsource (lib "eagle-import") (part "R_0402_10K0"))
    )
    (comp (ref "R60")
      (value "2K2")
      (footprint "eagle-import:0402")
      (libsource (lib "eagle-import") (part "R_0402"))
    )
    (comp (ref "R61")
      (value "1k")
      (footprint "eagle-import:0805")
      (libsource (lib "eagle-import") (part "R_0805"))
    )
    (comp (ref "R62")
      (value "33")
      (footprint "eagle-import:0805")
      (libsource (lib "eagle-import") (part "R_0805"))
    )
    (comp (ref "R63")
      (value "33")
      (footprint "eagle-import:0805")
      (libsource (lib "eagle-import") (part "R_0805"))
    )
    (comp (ref "R64")
      (value "33")
      (footprint "eagle-import:0805")
      (libsource (lib "eagle-import") (part "R_0805"))
    )
    (comp (ref "R65")
      (value "1k")
      (footprint "eagle-import:0805")
      (libsource (lib "eagle-import") (part "R_0805"))
    )
    (comp (ref "R66")
      (value "1k")
      (footprint "eagle-import:0805")
      (libsource (lib "eagle-import") (part "R_0805"))
    )
    (comp (ref "R67")
      (value "1k")
      (footprint "eagle-import:0805")
      (libsource (lib "eagle-import") (part "R_0805"))
    )
    (comp (ref "R68")
      (value "33")
      (footprint "eagle-import:0805")
      (libsource (lib "eagle-import") (part "R_0805"))
    )
    (comp (ref "R69")
      (value "33")
      (footprint "eagle-import:0805")
      (libsource (lib "eagle-import") (part "R_0805"))
    )
    (comp (ref "R70")
      (value "33")
      (footprint "eagle-import:0805")
      (libsource (lib "eagle-import") (part "R_0805"))
    )
    (comp (ref "R71")
      (value "1k")
      (footprint "eagle-import:0805")
      (libsource (lib "eagle-import") (part "R_0805"))
    )
    (comp (ref "R72")
      (value "1k")
      (footprint "eagle-import:0805")
      (libsource (lib "eagle-import") (part "R_0805"))
    )
    (comp (ref "R73")
      (value "470R0")
      (footprint "eagle-import:0402")
      (fields (field (name "PARTNO") "RMCF0402JT470R"))
      (libsource (lib "eagle-import") (part "R_0402_470R0"))
    )
    (comp (ref "R74")
      (value "10K0")
      (footprint "eagle-import:0402")
      (fields (field (name "PARTNO") "RMCF0402JT10K0"))
      (libsource (lib "eagle-import") (part "R_0402_10K0"))
    )
    (comp (ref "R75")
      (value "2K2")
      (footprint "eagle-import:0402")
      (libsource (lib "eagle-import") (part "R_0402"))
    )
    (comp (ref "R76")
      (value "470R0")
      (footprint "eagle-import:0402")
      (fields (field (name "PARTNO") "RMCF0402JT470R"))
      (libsource (lib "eagle-import") (part "R_0402_470R0"))
    )
    (comp (ref "R77")
      (value "10K0")
      (footprint "eagle-import:0402")
      (fields (field (name "PARTNO") "RMCF0402JT10K0"))
      (libsource (lib "eagle-import") (part "R_0402_10K0"))
    )
    (comp (ref "R78")
      (value "2K2")
      (footprint "eagle-import:0402")
      (libsource (lib "eagle-import") (part "R_0402"))
    )
    (comp (ref "R79")
      (value "470R0")
      (footprint "eagle-import:0402")
      (fields (field (name "PARTNO") "RMCF0402JT470R"))
      (libsource (lib "eagle-import") (part "R_0402_470R0"))
    )
    (comp (ref "R80")
      (value "10K0")
      (footprint "eagle-import:0402")
      (fields (field (name "PARTNO") "RMCF0402JT10K0"))
      (libsource (lib "eagle-import") (part "R_0402_10K0"))
    )
    (comp (ref "R81")
      (value "2K2")
      (footprint "eagle-import:0402")
      (libsource (lib "eagle-import") (part "R_0402"))
    )
    (comp (ref "R82")
      (value "470R0")
      (footprint "eagle-import:0402")
      (fields (field (name "PARTNO") "RMCF0402JT470R"))
      (libsource (lib "eagle-import") (part "R_0402_470R0"))
    )
    (comp (ref "R83")
      (value "10K0")
      (footprint "eagle-import:0402")
      (fields (field (name "PARTNO") "RMCF0402JT10K0"))
      (libsource (lib "eagle-import") (part "R_0402_10K0"))
    )
    (comp (ref "R84")
      (value "2K2")
      (footprint "eagle-import:0402")
      (libsource (lib "eagle-import") (part "R_0402"))
    )
    (comp (ref "R85")
      (value "1k")
      (footprint "eagle-import:0805")
      (libsource (lib "eagle-import") (part "R_0805"))
    )
    (comp (ref "R86")
      (value "33")
      (footprint "eagle-import:0805")
      (libsource (lib "eagle-import") (part "R_0805"))
    )
    (comp (ref "R87")
      (value "33")
      (footprint "eagle-import:0805")
      (libsource (lib "eagle-import") (part "R_0805"))
    )
    (comp (ref "R88")
      (value "33")
      (footprint "eagle-import:0805")
      (libsource (lib "eagle-import") (part "R_0805"))
    )
    (comp (ref "R89")
      (value "1k")
      (footprint "eagle-import:0805")
      (libsource (lib "eagle-import") (part "R_0805"))
    )
    (comp (ref "R90")
      (value "1k")
      (footprint "eagle-import:0805")
      (libsource (lib "eagle-import") (part "R_0805"))
    )
    (comp (ref "R91")
      (value "1k")
      (footprint "eagle-import:0805")
      (libsource (lib "eagle-import") (part "R_0805"))
    )
    (comp (ref "R92")
      (value "33")
      (footprint "eagle-import:0805")
      (libsource (lib "eagle-import") (part "R_0805"))
    )
    (comp (ref "R93")
      (value "33")
      (footprint "eagle-import:0805")
      (libsource (lib "eagle-import") (part "R_0805"))
    )
    (comp (ref "R94")
      (value "33")
      (footprint "eagle-import:0805")
      (libsource (lib "eagle-import") (part "R_0805"))
    )
    (comp (ref "R95")
      (value "1k")
      (footprint "eagle-import:0805")
      (libsource (lib "eagle-import") (part "R_0805"))
    )
    (comp (ref "R96")
      (value "1k")
      (footprint "eagle-import:0805")
      (libsource (lib "eagle-import") (part "R_0805"))
    )
    (comp (ref "R97")
      (value "470R0")
      (footprint "eagle-import:0402")
      (fields (field (name "PARTNO") "RMCF0402JT470R"))
      (libsource (lib "eagle-import") (part "R_0402_470R0"))
    )
    (comp (ref "R98")
      (value "10K0")
      (footprint "eagle-import:0402")
      (fields (field (name "PARTNO") "RMCF0402JT10K0"))
      (libsource (lib "eagle-import") (part "R_0402_10K0"))
    )
    (comp (ref "R99")
      (value "2K2")
      (footprint "eagle-import:0402")
      (libsource (lib "eagle-import") (part "R_0402"))
    )
    (comp (ref "R100")
      (value "470R0")
      (footprint "eagle-import:0402")
      (fields (field (name "PARTNO") "RMCF0402JT470R"))
      (libsource (lib "eagle-import") (part "R_0402_470R0"))
    )
    (comp (ref "R101")
      (value "10K0")
      (footprint "eagle-import:0402")
      (fields (field (name "PARTNO") "RMCF0402JT10K0"))
      (libsource (lib "eagle-import") (part "R_0402_10K0"))
    )
    (comp (ref "R102")
      (value "100K")
      (footprint "eagle-import:0402")
      (libsource (lib "eagle-import") (part "R_0402"))
    )
    (comp (ref "R103")
      (value "100K")
      (footprint "eagle-import:0402")
      (libsource (lib "eagle-import") (part "R_0402"))
    )
    (comp (ref "R104")
      (value "100K")
      (footprint "eagle-import:0402")
      (libsource (lib "eagle-import") (part "R_0402"))
    )
    (comp (ref "R105")
      (value "100K")
      (footprint "eagle-import:0402")
      (libsource (lib "eagle-import") (part "R_0402"))
    )
    (comp (ref "R106")
      (value "100K")
      (footprint "eagle-import:0402")
      (libsource (lib "eagle-import") (part "R_0402"))
    )
    (comp (ref "R107")
      (value "100K")
      (footprint "eagle-import:0402")
      (libsource (lib "eagle-import") (part "R_0402"))
    )
    (comp (ref "R108")
      (value "100K")
      (footprint "eagle-import:0402")
      (libsource (lib "eagle-import") (part "R_0402"))
    )
    (comp (ref "R109")
      (value "1k")
      (footprint "eagle-import:0805")
      (libsource (lib "eagle-import") (part "R_0805"))
    )
    (comp (ref "R110")
      (value "33")
      (footprint "eagle-import:0805")
      (libsource (lib "eagle-import") (part "R_0805"))
    )
    (comp (ref "R111")
      (value "33")
      (footprint "eagle-import:0805")
      (libsource (lib "eagle-import") (part "R_0805"))
    )
    (comp (ref "R112")
      (value "33")
      (footprint "eagle-import:0805")
      (libsource (lib "eagle-import") (part "R_0805"))
    )
    (comp (ref "R113")
      (value "1k")
      (footprint "eagle-import:0805")
      (libsource (lib "eagle-import") (part "R_0805"))
    )
    (comp (ref "R114")
      (value "1k")
      (footprint "eagle-import:0805")
      (libsource (lib "eagle-import") (part "R_0805"))
    )
    (comp (ref "R115")
      (value "1k")
      (footprint "eagle-import:0805")
      (libsource (lib "eagle-import") (part "R_0805"))
    )
    (comp (ref "R116")
      (value "33")
      (footprint "eagle-import:0805")
      (libsource (lib "eagle-import") (part "R_0805"))
    )
    (comp (ref "R117")
      (value "33")
      (footprint "eagle-import:0805")
      (libsource (lib "eagle-import") (part "R_0805"))
    )
    (comp (ref "R118")
      (value "33")
      (footprint "eagle-import:0805")
      (libsource (lib "eagle-import") (part "R_0805"))
    )
    (comp (ref "R119")
      (value "1k")
      (footprint "eagle-import:0805")
      (libsource (lib "eagle-import") (part "R_0805"))
    )
    (comp (ref "R120")
      (value "1k")
      (footprint "eagle-import:0805")
      (libsource (lib "eagle-import") (part "R_0805"))
    )
    (comp (ref "R133")
      (value "1k")
      (footprint "eagle-import:0805")
      (libsource (lib "eagle-import") (part "R_0805"))
    )
    (comp (ref "R134")
      (value "33")
      (footprint "eagle-import:0805")
      (libsource (lib "eagle-import") (part "R_0805"))
    )
    (comp (ref "R135")
      (value "33")
      (footprint "eagle-import:0805")
      (libsource (lib "eagle-import") (part "R_0805"))
    )
    (comp (ref "R136")
      (value "33")
      (footprint "eagle-import:0805")
      (libsource (lib "eagle-import") (part "R_0805"))
    )
    (comp (ref "R137")
      (value "1k")
      (footprint "eagle-import:0805")
      (libsource (lib "eagle-import") (part "R_0805"))
    )
    (comp (ref "R138")
      (value "1k")
      (footprint "eagle-import:0805")
      (libsource (lib "eagle-import") (part "R_0805"))
    )
    (comp (ref "R139")
      (value "1k")
      (footprint "eagle-import:0805")
      (libsource (lib "eagle-import") (part "R_0805"))
    )
    (comp (ref "R140")
      (value "33")
      (footprint "eagle-import:0805")
      (libsource (lib "eagle-import") (part "R_0805"))
    )
    (comp (ref "R141")
      (value "33")
      (footprint "eagle-import:0805")
      (libsource (lib "eagle-import") (part "R_0805"))
    )
    (comp (ref "R142")
      (value "33")
      (footprint "eagle-import:0805")
      (libsource (lib "eagle-import") (part "R_0805"))
    )
    (comp (ref "R143")
      (value "1k")
      (footprint "eagle-import:0805")
      (libsource (lib "eagle-import") (part "R_0805"))
    )
    (comp (ref "R144")
      (value "1k")
      (footprint "eagle-import:0805")
      (libsource (lib "eagle-import") (part "R_0805"))
    )
    (comp (ref "R157")
      (value "1k")
      (footprint "eagle-import:0805")
      (libsource (lib "eagle-import") (part "R_0805"))
    )
    (comp (ref "R158")
      (value "33")
      (footprint "eagle-import:0805")
      (libsource (lib "eagle-import") (part "R_0805"))
    )
    (comp (ref "R159")
      (value "33")
      (footprint "eagle-import:0805")
      (libsource (lib "eagle-import") (part "R_0805"))
    )
    (comp (ref "R160")
      (value "33")
      (footprint "eagle-import:0805")
      (libsource (lib "eagle-import") (part "R_0805"))
    )
    (comp (ref "R161")
      (value "1k")
      (footprint "eagle-import:0805")
      (libsource (lib "eagle-import") (part "R_0805"))
    )
    (comp (ref "R162")
      (value "1k")
      (footprint "eagle-import:0805")
      (libsource (lib "eagle-import") (part "R_0805"))
    )
    (comp (ref "R163")
      (value "1k")
      (footprint "eagle-import:0805")
      (libsource (lib "eagle-import") (part "R_0805"))
    )
    (comp (ref "R164")
      (value "33")
      (footprint "eagle-import:0805")
      (libsource (lib "eagle-import") (part "R_0805"))
    )
    (comp (ref "R165")
      (value "33")
      (footprint "eagle-import:0805")
      (libsource (lib "eagle-import") (part "R_0805"))
    )
    (comp (ref "R166")
      (value "33")
      (footprint "eagle-import:0805")
      (libsource (lib "eagle-import") (part "R_0805"))
    )
    (comp (ref "R167")
      (value "1k")
      (footprint "eagle-import:0805")
      (libsource (lib "eagle-import") (part "R_0805"))
    )
    (comp (ref "R168")
      (value "1k")
      (footprint "eagle-import:0805")
      (libsource (lib "eagle-import") (part "R_0805"))
    )
    (comp (ref "RJ1")
      (value "RJ45")
      (footprint "eagle-import:RJ45_TH_ELEC")
      (fields (field (name "PARTNO") "13F-64GYD2PL2NL"))
      (libsource (lib "eagle-import") (part "RJ45_WITH_ELEC"))
    )
    (comp (ref "U$1")
      (value "RELAY_KYOTO_KF0604D")
      (footprint "eagle-import:RELAY_KYOTO_KF0604D")
      (libsource (lib "eagle-import") (part "RELAY_KYOTO_KF0604D"))
    )
    (comp (ref "U$2")
      (value "RELAY_KYOTO_KF0604D")
      (footprint "eagle-import:RELAY_KYOTO_KF0604D")
      (libsource (lib "eagle-import") (part "RELAY_KYOTO_KF0604D"))
    )
    (comp (ref "U$7")
      (value "RELAY_KYOTO_KF0604D")
      (footprint "eagle-import:RELAY_KYOTO_KF0604D")
      (libsource (lib "eagle-import") (part "RELAY_KYOTO_KF0604D"))
    )
    (comp (ref "U$8")
      (value "RELAY_KYOTO_KF0604D")
      (footprint "eagle-import:RELAY_KYOTO_KF0604D")
      (libsource (lib "eagle-import") (part "RELAY_KYOTO_KF0604D"))
    )
    (comp (ref "U1")
      (value "KSZ8081_QFN_24")
      (footprint "eagle-import:QFN-24-M")
      (fields (field (name "PARTNO") "KSZ8081RNACA"))
      (libsource (lib "eagle-import") (part "KSZ8081RNACAQFN-24-M"))
    )
    (comp (ref "U2")
      (value "AP2151DWG-7")
      (footprint "eagle-import:SOT-23-5")
      (fields (field (name "PARTNO") "AP2151WG-7"))
      (libsource (lib "eagle-import") (part "AP2151DWG-7"))
    )
    (comp (ref "U3")
      (value "S7G2LQFP176")
      (footprint "eagle-import:LQFP176_24X24")
      (fields (field (name "PARTNO") "R7FS7G27H3A01CFC#AA0"))
      (libsource (lib "eagle-import") (part "RENESAS_S7G2_X_176"))
    )
    (comp (ref "U5")
      (value "NPN")
      (footprint "eagle-import:SOT323")
      (fields (field (name "PARTNO") "BC846BW_NPN"))
      (libsource (lib "eagle-import") (part "BC846BW"))
    )
    (comp (ref "U6")
      (value "NPN")
      (footprint "eagle-import:SOT323")
      (fields (field (name "PARTNO") "BC846BW_NPN"))
      (libsource (lib "eagle-import") (part "BC846BW"))
    )
    (comp (ref "U7")
      (value "NPN")
      (footprint "eagle-import:SOT323")
      (fields (field (name "PARTNO") "BC846BW_NPN"))
      (libsource (lib "eagle-import") (part "BC846BW"))
    )
    (comp (ref "U8")
      (value "NPN")
      (footprint "eagle-import:SOT323")
      (fields (field (name "PARTNO") "BC846BW_NPN"))
      (libsource (lib "eagle-import") (part "BC846BW"))
    )
    (comp (ref "U9")
      (value "NPN")
      (footprint "eagle-import:SOT323")
      (fields (field (name "PARTNO") "BC846BW_NPN"))
      (libsource (lib "eagle-import") (part "BC846BW"))
    )
    (comp (ref "U10")
      (value "NPN")
      (footprint "eagle-import:SOT323")
      (fields (field (name "PARTNO") "BC846BW_NPN"))
      (libsource (lib "eagle-import") (part "BC846BW"))
    )
    (comp (ref "U11")
      (value "NPN")
      (footprint "eagle-import:SOT323")
      (fields (field (name "PARTNO") "BC846BW_NPN"))
      (libsource (lib "eagle-import") (part "BC846BW"))
    )
    (comp (ref "U12")
      (value "NPN")
      (footprint "eagle-import:SOT323")
      (fields (field (name "PARTNO") "BC846BW_NPN"))
      (libsource (lib "eagle-import") (part "BC846BW"))
    )
    (comp (ref "U13")
      (value "NPN")
      (footprint "eagle-import:SOT323")
      (fields (field (name "PARTNO") "BC846BW_NPN"))
      (libsource (lib "eagle-import") (part "BC846BW"))
    )
    (comp (ref "U14")
      (value "NPN")
      (footprint "eagle-import:SOT323")
      (fields (field (name "PARTNO") "BC846BW_NPN"))
      (libsource (lib "eagle-import") (part "BC846BW"))
    )
    (comp (ref "U15")
      (value "NPN")
      (footprint "eagle-import:SOT323")
      (fields (field (name "PARTNO") "BC846BW_NPN"))
      (libsource (lib "eagle-import") (part "BC846BW"))
    )
    (comp (ref "U16")
      (value "NPN")
      (footprint "eagle-import:SOT323")
      (fields (field (name "PARTNO") "BC846BW_NPN"))
      (libsource (lib "eagle-import") (part "BC846BW"))
    )
    (comp (ref "U17")
      (value "NPN")
      (footprint "eagle-import:SOT323")
      (fields (field (name "PARTNO") "BC846BW_NPN"))
      (libsource (lib "eagle-import") (part "BC846BW"))
    )
    (comp (ref "U18")
      (value "NPN")
      (footprint "eagle-import:SOT323")
      (fields (field (name "PARTNO") "BC846BW_NPN"))
      (libsource (lib "eagle-import") (part "BC846BW"))
    )
    (comp (ref "U19")
      (value "NPN")
      (footprint "eagle-import:SOT323")
      (fields (field (name "PARTNO") "BC846BW_NPN"))
      (libsource (lib "eagle-import") (part "BC846BW"))
    )
    (comp (ref "U20")
      (value "NPN")
      (footprint "eagle-import:SOT323")
      (fields (field (name "PARTNO") "BC846BW_NPN"))
      (libsource (lib "eagle-import") (part "BC846BW"))
    )
    (comp (ref "U21")
      (value "NPN")
      (footprint "eagle-import:SOT323")
      (fields (field (name "PARTNO") "BC846BW_NPN"))
      (libsource (lib "eagle-import") (part "BC846BW"))
    )
    (comp (ref "U22")
      (value "NPN")
      (footprint "eagle-import:SOT323")
      (fields (field (name "PARTNO") "BC846BW_NPN"))
      (libsource (lib "eagle-import") (part "BC846BW"))
    )
    (comp (ref "U23")
      (value "NPN")
      (footprint "eagle-import:SOT323")
      (fields (field (name "PARTNO") "BC846BW_NPN"))
      (libsource (lib "eagle-import") (part "BC846BW"))
    )
    (comp (ref "U24")
      (value "NPN")
      (footprint "eagle-import:SOT323")
      (fields (field (name "PARTNO") "BC846BW_NPN"))
      (libsource (lib "eagle-import") (part "BC846BW"))
    )
    (comp (ref "U25")
      (value "NPN")
      (footprint "eagle-import:SOT323")
      (fields (field (name "PARTNO") "BC846BW_NPN"))
      (libsource (lib "eagle-import") (part "BC846BW"))
    )
    (comp (ref "U26")
      (value "NPN")
      (footprint "eagle-import:SOT323")
      (fields (field (name "PARTNO") "BC846BW_NPN"))
      (libsource (lib "eagle-import") (part "BC846BW"))
    )
    (comp (ref "U27")
      (value "NPN")
      (footprint "eagle-import:SOT323")
      (fields (field (name "PARTNO") "BC846BW_NPN"))
      (libsource (lib "eagle-import") (part "BC846BW"))
    )
    (comp (ref "U28")
      (value "NPN")
      (footprint "eagle-import:SOT323")
      (fields (field (name "PARTNO") "BC846BW_NPN"))
      (libsource (lib "eagle-import") (part "BC846BW"))
    )
    (comp (ref "U29")
      (value "NPN")
      (footprint "eagle-import:SOT323")
      (fields (field (name "PARTNO") "BC846BW_NPN"))
      (libsource (lib "eagle-import") (part "BC846BW"))
    )
    (comp (ref "U30")
      (value "NPN")
      (footprint "eagle-import:SOT323")
      (fields (field (name "PARTNO") "BC846BW_NPN"))
      (libsource (lib "eagle-import") (part "BC846BW"))
    )
    (comp (ref "U34")
      (value "NPN")
      (footprint "eagle-import:SOT323")
      (fields (field (name "PARTNO") "BC846BW_NPN"))
      (libsource (lib "eagle-import") (part "BC846BW"))
    )
    (comp (ref "U35")
      (value "NPN")
      (footprint "eagle-import:SOT323")
      (fields (field (name "PARTNO") "BC846BW_NPN"))
      (libsource (lib "eagle-import") (part "BC846BW"))
    )
    (comp (ref "U36")
      (value "NPN")
      (footprint "eagle-import:SOT323")
      (fields (field (name "PARTNO") "BC846BW_NPN"))
      (libsource (lib "eagle-import") (part "BC846BW"))
    )
    (comp (ref "U37")
      (value "NPN")
      (footprint "eagle-import:SOT323")
      (fields (field (name "PARTNO") "BC846BW_NPN"))
      (libsource (lib "eagle-import") (part "BC846BW"))
    )
    (comp (ref "U38")
      (value "NPN")
      (footprint "eagle-import:SOT323")
      (fields (field (name "PARTNO") "BC846BW_NPN"))
      (libsource (lib "eagle-import") (part "BC846BW"))
    )
    (comp (ref "U39")
      (value "NPN")
      (footprint "eagle-import:SOT323")
      (fields (field (name "PARTNO") "BC846BW_NPN"))
      (libsource (lib "eagle-import") (part "BC846BW"))
    )
    (comp (ref "U46")
      (value "NPN")
      (footprint "eagle-import:SOT323")
      (fields (field (name "PARTNO") "BC846BW_NPN"))
      (libsource (lib "eagle-import") (part "BC846BW"))
    )
    (comp (ref "U47")
      (value "NPN")
      (footprint "eagle-import:SOT323")
      (fields (field (name "PARTNO") "BC846BW_NPN"))
      (libsource (lib "eagle-import") (part "BC846BW"))
    )
    (comp (ref "U48")
      (value "NPN")
      (footprint "eagle-import:SOT323")
      (fields (field (name "PARTNO") "BC846BW_NPN"))
      (libsource (lib "eagle-import") (part "BC846BW"))
    )
    (comp (ref "U49")
      (value "NPN")
      (footprint "eagle-import:SOT323")
      (fields (field (name "PARTNO") "BC846BW_NPN"))
      (libsource (lib "eagle-import") (part "BC846BW"))
    )
    (comp (ref "U50")
      (value "NPN")
      (footprint "eagle-import:SOT323")
      (fields (field (name "PARTNO") "BC846BW_NPN"))
      (libsource (lib "eagle-import") (part "BC846BW"))
    )
    (comp (ref "U51")
      (value "NPN")
      (footprint "eagle-import:SOT323")
      (fields (field (name "PARTNO") "BC846BW_NPN"))
      (libsource (lib "eagle-import") (part "BC846BW"))
    )
    (comp (ref "U58")
      (value "NPN")
      (footprint "eagle-import:SOT323")
      (fields (field (name "PARTNO") "BC846BW_NPN"))
      (libsource (lib "eagle-import") (part "BC846BW"))
    )
    (comp (ref "U59")
      (value "NPN")
      (footprint "eagle-import:SOT323")
      (fields (field (name "PARTNO") "BC846BW_NPN"))
      (libsource (lib "eagle-import") (part "BC846BW"))
    )
    (comp (ref "U60")
      (value "NPN")
      (footprint "eagle-import:SOT323")
      (fields (field (name "PARTNO") "BC846BW_NPN"))
      (libsource (lib "eagle-import") (part "BC846BW"))
    )
    (comp (ref "U61")
      (value "NPN")
      (footprint "eagle-import:SOT323")
      (fields (field (name "PARTNO") "BC846BW_NPN"))
      (libsource (lib "eagle-import") (part "BC846BW"))
    )
    (comp (ref "U62")
      (value "NPN")
      (footprint "eagle-import:SOT323")
      (fields (field (name "PARTNO") "BC846BW_NPN"))
      (libsource (lib "eagle-import") (part "BC846BW"))
    )
    (comp (ref "U63")
      (value "NPN")
      (footprint "eagle-import:SOT323")
      (fields (field (name "PARTNO") "BC846BW_NPN"))
      (libsource (lib "eagle-import") (part "BC846BW"))
    )
    (comp (ref "U70")
      (value "NPN")
      (footprint "eagle-import:SOT323")
      (fields (field (name "PARTNO") "BC846BW_NPN"))
      (libsource (lib "eagle-import") (part "BC846BW"))
    )
    (comp (ref "U71")
      (value "NPN")
      (footprint "eagle-import:SOT323")
      (fields (field (name "PARTNO") "BC846BW_NPN"))
      (libsource (lib "eagle-import") (part "BC846BW"))
    )
    (comp (ref "U72")
      (value "NPN")
      (footprint "eagle-import:SOT323")
      (fields (field (name "PARTNO") "BC846BW_NPN"))
      (libsource (lib "eagle-import") (part "BC846BW"))
    )
    (comp (ref "U73")
      (value "NPN")
      (footprint "eagle-import:SOT323")
      (fields (field (name "PARTNO") "BC846BW_NPN"))
      (libsource (lib "eagle-import") (part "BC846BW"))
    )
    (comp (ref "U74")
      (value "NPN")
      (footprint "eagle-import:SOT323")
      (fields (field (name "PARTNO") "BC846BW_NPN"))
      (libsource (lib "eagle-import") (part "BC846BW"))
    )
    (comp (ref "U75")
      (value "NPN")
      (footprint "eagle-import:SOT323")
      (fields (field (name "PARTNO") "BC846BW_NPN"))
      (libsource (lib "eagle-import") (part "BC846BW"))
    )
    (comp (ref "X1")
      (value "25MHz")
      (footprint "eagle-import:SMD_3225")
      (fields (field (name "PARTNO") "FA-238 25.0000MB-B3"))
      (libsource (lib "eagle-import") (part "XTAL_25_MHZ"))
    )
    (comp (ref "X2")
      (value "24MHz")
      (footprint "eagle-import:SMD_3225")
      (fields (field (name "PARTNO") "FA-238 24.0000MB-C3 "))
      (libsource (lib "eagle-import") (part "XTAL_24_MHZ"))
    )
    (comp (ref "X3")
      (value "32.768KHz")
      (footprint "eagle-import:SMD_X_2_PADS")
      (fields (field (name "PARTNO") "ABS07-32.768KHZ-T"))
      (libsource (lib "eagle-import") (part "XTAL_32.768KHZ"))
    )
  )
  (nets
    (net (code "1") (name "A_A_DIR") (class "Default")
      (node (ref "R111") (pin "1") (pinfunction "1_1") (pintype "passive"))
      (node (ref "U3") (pin "73") (pinfunction "P9_5_73") (pintype "bidirectional"))
    )
    (net (code "2") (name "A_A_ENABLE") (class "Default")
      (node (ref "R112") (pin "1") (pinfunction "1_1") (pintype "passive"))
      (node (ref "U3") (pin "72") (pinfunction "P9_6_72") (pintype "bidirectional"))
    )
    (net (code "3") (name "A_A_HLFB_OUT") (class "Default")
      (node (ref "J25") (pin "5") (pinfunction "5-HLFB-_5") (pintype "passive"))
    )
    (net (code "4") (name "A_A_MI_DIR") (class "Default")
      (node (ref "J25") (pin "7") (pinfunction "7-INPUT_A-_7") (pintype "passive"))
      (node (ref "R113") (pin "1") (pinfunction "1_1") (pintype "passive"))
      (node (ref "U47") (pin "3") (pinfunction "C(3)_3") (pintype "input"))
    )
    (net (code "5") (name "A_A_MI_ENABLE") (class "Default")
      (node (ref "J25") (pin "8") (pinfunction "8-ENABLE-_8") (pintype "passive"))
      (node (ref "R114") (pin "1") (pinfunction "1_1") (pintype "passive"))
      (node (ref "U48") (pin "3") (pinfunction "C(3)_3") (pintype "input"))
    )
    (net (code "6") (name "A_A_MI_STEP") (class "Default")
      (node (ref "J25") (pin "6") (pinfunction "6-INPUT_B-_6") (pintype "passive"))
      (node (ref "R109") (pin "1") (pinfunction "1_1") (pintype "passive"))
      (node (ref "U46") (pin "3") (pinfunction "C(3)_3") (pintype "input"))
    )
    (net (code "7") (name "A_A_STEP") (class "Default")
      (node (ref "R110") (pin "1") (pinfunction "1_1") (pintype "passive"))
      (node (ref "U3") (pin "74") (pinfunction "P3_12_74") (pintype "bidirectional"))
    )
    (net (code "8") (name "A_B_DIR") (class "Default")
      (node (ref "R117") (pin "1") (pinfunction "1_1") (pintype "passive"))
      (node (ref "U3") (pin "76") (pinfunction "P3_10_76") (pintype "bidirectional"))
    )
    (net (code "9") (name "A_B_ENABLE") (class "Default")
      (node (ref "R118") (pin "1") (pinfunction "1_1") (pintype "passive"))
      (node (ref "U3") (pin "75") (pinfunction "P3_11_75") (pintype "bidirectional"))
    )
    (net (code "10") (name "A_B_HLFB_OUT") (class "Default")
      (node (ref "J26") (pin "5") (pinfunction "5-HLFB-_5") (pintype "passive"))
    )
    (net (code "11") (name "A_B_MI_DIR") (class "Default")
      (node (ref "J26") (pin "7") (pinfunction "7-INPUT_A-_7") (pintype "passive"))
      (node (ref "R119") (pin "1") (pinfunction "1_1") (pintype "passive"))
      (node (ref "U50") (pin "3") (pinfunction "C(3)_3") (pintype "input"))
    )
    (net (code "12") (name "A_B_MI_ENABLE") (class "Default")
      (node (ref "J26") (pin "8") (pinfunction "8-ENABLE-_8") (pintype "passive"))
      (node (ref "R120") (pin "1") (pinfunction "1_1") (pintype "passive"))
      (node (ref "U51") (pin "3") (pinfunction "C(3)_3") (pintype "input"))
    )
    (net (code "13") (name "A_B_MI_STEP") (class "Default")
      (node (ref "J26") (pin "6") (pinfunction "6-INPUT_B-_6") (pintype "passive"))
      (node (ref "R115") (pin "1") (pinfunction "1_1") (pintype "passive"))
      (node (ref "U49") (pin "3") (pinfunction "C(3)_3") (pintype "input"))
    )
    (net (code "14") (name "A_B_STEP") (class "Default")
      (node (ref "R116") (pin "1") (pinfunction "1_1") (pintype "passive"))
      (node (ref "U3") (pin "77") (pinfunction "P3_9_77") (pintype "bidirectional"))
    )
    (net (code "15") (name "B_MI_DIR") (class "Default")
      (node (ref "J34") (pin "7") (pinfunction "7-INPUT_A-_7") (pintype "passive"))
      (node (ref "R167") (pin "1") (pinfunction "1_1") (pintype "passive"))
      (node (ref "U74") (pin "3") (pinfunction "C(3)_3") (pintype "input"))
    )
    (net (code "16") (name "C58") (class "Default")
      (node (ref "C12") (pin "P$1") (pinfunction "1_P$1") (pintype "passive"))
      (node (ref "RJ1") (pin "4") (pinfunction "CT1_4") (pintype "bidirectional"))
    )
    (net (code "17") (name "C60") (class "Default")
      (node (ref "C13") (pin "P$1") (pinfunction "1_P$1") (pintype "passive"))
      (node (ref "RJ1") (pin "5") (pinfunction "CT2_5") (pintype "bidirectional"))
    )
    (net (code "18") (name "CRS_DV") (class "Default")
      (node (ref "R12") (pin "P$2") (pinfunction "2_P$2") (pintype "passive"))
      (node (ref "U1") (pin "15") (pinfunction "CRS_DV/PHYAD[1:0]_15") (pintype "bidirectional"))
    )
    (net (code "19") (name "C_A_DIR") (class "Default")
      (node (ref "R135") (pin "1") (pinfunction "1_1") (pintype "passive"))
      (node (ref "U3") (pin "58") (pinfunction "P9_0_58") (pintype "bidirectional"))
    )
    (net (code "20") (name "C_A_ENABLE") (class "Default")
      (node (ref "R136") (pin "1") (pinfunction "1_1") (pintype "passive"))
      (node (ref "U3") (pin "57") (pinfunction "P3_15_57") (pintype "bidirectional"))
    )
    (net (code "21") (name "C_A_HLFB_OUT") (class "Default")
      (node (ref "J29") (pin "5") (pinfunction "5-HLFB-_5") (pintype "passive"))
    )
    (net (code "22") (name "C_A_MI_DIR") (class "Default")
      (node (ref "J29") (pin "7") (pinfunction "7-INPUT_A-_7") (pintype "passive"))
      (node (ref "R137") (pin "1") (pinfunction "1_1") (pintype "passive"))
      (node (ref "U59") (pin "3") (pinfunction "C(3)_3") (pintype "input"))
    )
    (net (code "23") (name "C_A_MI_ENABLE") (class "Default")
      (node (ref "J29") (pin "8") (pinfunction "8-ENABLE-_8") (pintype "passive"))
      (node (ref "R138") (pin "1") (pinfunction "1_1") (pintype "passive"))
      (node (ref "U60") (pin "3") (pinfunction "C(3)_3") (pintype "input"))
    )
    (net (code "24") (name "C_A_MI_STEP") (class "Default")
      (node (ref "J29") (pin "6") (pinfunction "6-INPUT_B-_6") (pintype "passive"))
      (node (ref "R133") (pin "1") (pinfunction "1_1") (pintype "passive"))
      (node (ref "U58") (pin "3") (pinfunction "C(3)_3") (pintype "input"))
    )
    (net (code "25") (name "C_A_STEP") (class "Default")
      (node (ref "R134") (pin "1") (pinfunction "1_1") (pintype "passive"))
      (node (ref "U3") (pin "59") (pinfunction "P9_1_59") (pintype "bidirectional"))
    )
    (net (code "26") (name "C_B_DIR") (class "Default")
      (node (ref "R141") (pin "1") (pinfunction "1_1") (pintype "passive"))
      (node (ref "U3") (pin "70") (pinfunction "P9_8_70") (pintype "bidirectional"))
    )
    (net (code "27") (name "C_B_ENABLE") (class "Default")
      (node (ref "R142") (pin "1") (pinfunction "1_1") (pintype "passive"))
      (node (ref "U3") (pin "68") (pinfunction "P2_1/MD_68") (pintype "bidirectional"))
    )
    (net (code "28") (name "C_B_HLFB_OUT") (class "Default")
      (node (ref "J30") (pin "5") (pinfunction "5-HLFB-_5") (pintype "passive"))
    )
    (net (code "29") (name "C_B_MI_DIR") (class "Default")
      (node (ref "J30") (pin "7") (pinfunction "7-INPUT_A-_7") (pintype "passive"))
      (node (ref "R143") (pin "1") (pinfunction "1_1") (pintype "passive"))
      (node (ref "U62") (pin "3") (pinfunction "C(3)_3") (pintype "input"))
    )
    (net (code "30") (name "C_B_MI_ENABLE") (class "Default")
      (node (ref "J30") (pin "8") (pinfunction "8-ENABLE-_8") (pintype "passive"))
      (node (ref "R144") (pin "1") (pinfunction "1_1") (pintype "passive"))
      (node (ref "U63") (pin "3") (pinfunction "C(3)_3") (pintype "input"))
    )
    (net (code "31") (name "C_B_MI_STEP") (class "Default")
      (node (ref "J30") (pin "6") (pinfunction "6-INPUT_B-_6") (pintype "passive"))
      (node (ref "R139") (pin "1") (pinfunction "1_1") (pintype "passive"))
      (node (ref "U61") (pin "3") (pinfunction "C(3)_3") (pintype "input"))
    )
    (net (code "32") (name "C_B_STEP") (class "Default")
      (node (ref "R140") (pin "1") (pinfunction "1_1") (pintype "passive"))
      (node (ref "U3") (pin "71") (pinfunction "P9_7_71") (pintype "bidirectional"))
    )
    (net (code "33") (name "ESTOP") (class "Default")
      (node (ref "R79") (pin "P$2") (pinfunction "2_P$2") (pintype "passive"))
      (node (ref "R80") (pin "P$2") (pinfunction "2_P$2") (pintype "passive"))
      (node (ref "U21") (pin "2") (pinfunction "E(1)_2") (pintype "output"))
      (node (ref "U3") (pin "69") (pinfunction "P2_0(INPUT_ONLY)_69") (pintype "bidirectional"))
    )
    (net (code "34") (name "ESTOP_RET") (class "Default")
      (node (ref "J9") (pin "P$1") (pinfunction "P$1_P$1") (pintype "bidirectional"))
      (node (ref "R78") (pin "P$1") (pinfunction "1_P$1") (pintype "passive"))
    )
    (net (code "35") (name "ETH") (class "Default")
      (node (ref "U1") (pin "16") (pinfunction "REF_CLK_16") (pintype "bidirectional"))
      (node (ref "U3") (pin "9") (pinfunction "P7_1_9") (pintype "bidirectional"))
    )
    (net (code "36") (name "ETH_CRS_DV") (class "Default")
      (node (ref "R12") (pin "P$1") (pinfunction "1_P$1") (pintype "passive"))
      (node (ref "U3") (pin "13") (pinfunction "P7_5_13") (pintype "bidirectional"))
    )
    (net (code "37") (name "ETH_IRQ14") (class "Default")
      (node (ref "R2") (pin "P$1") (pinfunction "1_P$1") (pintype "passive"))
      (node (ref "U1") (pin "18") (pinfunction "INTRP_18") (pintype "bidirectional"))
      (node (ref "U3") (pin "159") (pinfunction "P0_10/AN103_159") (pintype "bidirectional"))
    )
    (net (code "38") (name "ETH_MDC") (class "Default")
      (node (ref "R4") (pin "P$1") (pinfunction "1_P$1") (pintype "passive"))
      (node (ref "U1") (pin "11") (pinfunction "MDC_11") (pintype "input"))
      (node (ref "U3") (pin "4") (pinfunction "P4_3_4") (pintype "bidirectional"))
    )
    (net (code "39") (name "ETH_MDIO") (class "Default")
      (node (ref "R6") (pin "P$1") (pinfunction "1_P$1") (pintype "passive"))
      (node (ref "U1") (pin "10") (pinfunction "MDIO_10") (pintype "bidirectional"))
      (node (ref "U3") (pin "5") (pinfunction "P4_4_5") (pintype "bidirectional"))
    )
    (net (code "40") (name "ETH_RESET") (class "Default")
      (node (ref "C6") (pin "P$1") (pinfunction "1_P$1") (pintype "passive"))
      (node (ref "R3") (pin "P$1") (pinfunction "1_P$1") (pintype "passive"))
      (node (ref "U1") (pin "24") (pinfunction "~{RST}_24") (pintype "input"))
      (node (ref "U3") (pin "172") (pinfunction "P8_6_172") (pintype "bidirectional"))
    )
    (net (code "41") (name "ETH_RXD0") (class "Default")
      (node (ref "R10") (pin "P$1") (pinfunction "1_P$1") (pintype "passive"))
      (node (ref "U3") (pin "10") (pinfunction "P7_2_10") (pintype "bidirectional"))
    )
    (net (code "42") (name "ETH_RXD1") (class "Default")
      (node (ref "R9") (pin "P$1") (pinfunction "1_P$1") (pintype "passive"))
      (node (ref "U3") (pin "11") (pinfunction "P7_3_11") (pintype "bidirectional"))
    )
    (net (code "43") (name "ETH_RX_ER") (class "Default")
      (node (ref "R11") (pin "P$1") (pinfunction "1_P$1") (pintype "passive"))
      (node (ref "U3") (pin "12") (pinfunction "P7_4_12") (pintype "bidirectional"))
    )
    (net (code "44") (name "ETH_TXD0") (class "Default")
      (node (ref "U1") (pin "20") (pinfunction "TXD0_20") (pintype "input"))
      (node (ref "U3") (pin "8") (pinfunction "P7_0_8") (pintype "bidirectional"))
    )
    (net (code "45") (name "ETH_TXD1") (class "Default")
      (node (ref "U1") (pin "21") (pinfunction "TXD1_21") (pintype "bidirectional"))
      (node (ref "U3") (pin "7") (pinfunction "P4_6_7") (pintype "bidirectional"))
    )
    (net (code "46") (name "ETH_TXD_EN") (class "Default")
      (node (ref "U1") (pin "19") (pinfunction "TXEN_19") (pintype "input"))
      (node (ref "U3") (pin "6") (pinfunction "P4_5_6") (pintype "bidirectional"))
    )
    (net (code "47") (name "GND") (class "Default")
      (node (ref "C1") (pin "P$2") (pinfunction "2_P$2") (pintype "passive"))
      (node (ref "C10") (pin "P$2") (pinfunction "2_P$2") (pintype "passive"))
      (node (ref "C11") (pin "P$2") (pinfunction "2_P$2") (pintype "passive"))
      (node (ref "C12") (pin "P$2") (pinfunction "2_P$2") (pintype "passive"))
      (node (ref "C13") (pin "P$2") (pinfunction "2_P$2") (pintype "passive"))
      (node (ref "C14") (pin "P$2") (pinfunction "2_P$2") (pintype "passive"))
      (node (ref "C15") (pin "P$2") (pinfunction "2_P$2") (pintype "passive"))
      (node (ref "C16") (pin "P$2") (pinfunction "2_P$2") (pintype "passive"))
      (node (ref "C17") (pin "P$2") (pinfunction "2_P$2") (pintype "passive"))
      (node (ref "C18") (pin "P$2") (pinfunction "2_P$2") (pintype "passive"))
      (node (ref "C19") (pin "P$1") (pinfunction "1_P$1") (pintype "passive"))
      (node (ref "C2") (pin "P$2") (pinfunction "2_P$2") (pintype "passive"))
      (node (ref "C20") (pin "P$1") (pinfunction "1_P$1") (pintype "passive"))
      (node (ref "C21") (pin "P$1") (pinfunction "1_P$1") (pintype "passive"))
      (node (ref "C22") (pin "P$1") (pinfunction "1_P$1") (pintype "passive"))
      (node (ref "C23") (pin "P$2") (pinfunction "2_P$2") (pintype "passive"))
      (node (ref "C24") (pin "P$1") (pinfunction "1_P$1") (pintype "passive"))
      (node (ref "C25") (pin "P$1") (pinfunction "1_P$1") (pintype "passive"))
      (node (ref "C26") (pin "P$2") (pinfunction "2_P$2") (pintype "passive"))
      (node (ref "C27") (pin "P$1") (pinfunction "1_P$1") (pintype "passive"))
      (node (ref "C28") (pin "P$2") (pinfunction "2_P$2") (pintype "passive"))
      (node (ref "C29") (pin "P$2") (pinfunction "2_P$2") (pintype "passive"))
      (node (ref "C3") (pin "P$2") (pinfunction "2_P$2") (pintype "passive"))
      (node (ref "C30") (pin "P$1") (pinfunction "1_P$1") (pintype "passive"))
      (node (ref "C31") (pin "2") (pinfunction "2_2") (pintype "passive"))
      (node (ref "C32") (pin "P$2") (pinfunction "2_P$2") (pintype "passive"))
      (node (ref "C33") (pin "P$2") (pinfunction "2_P$2") (pintype "passive"))
      (node (ref "C34") (pin "P$1") (pinfunction "1_P$1") (pintype "passive"))
      (node (ref "C35") (pin "P$1") (pinfunction "1_P$1") (pintype "passive"))
      (node (ref "C36") (pin "P$2") (pinfunction "2_P$2") (pintype "passive"))
      (node (ref "C37") (pin "P$2") (pinfunction "2_P$2") (pintype "passive"))
      (node (ref "C38") (pin "P$1") (pinfunction "1_P$1") (pintype "passive"))
      (node (ref "C39") (pin "P$2") (pinfunction "2_P$2") (pintype "passive"))
      (node (ref "C4") (pin "P$2") (pinfunction "2_P$2") (pintype "passive"))
      (node (ref "C40") (pin "P$2") (pinfunction "2_P$2") (pintype "passive"))
      (node (ref "C41") (pin "P$2") (pinfunction "2_P$2") (pintype "passive"))
      (node (ref "C42") (pin "P$2") (pinfunction "2_P$2") (pintype "passive"))
      (node (ref "C43") (pin "P$1") (pinfunction "1_P$1") (pintype "passive"))
      (node (ref "C5") (pin "P$2") (pinfunction "2_P$2") (pintype "passive"))
      (node (ref "C6") (pin "P$2") (pinfunction "2_P$2") (pintype "passive"))
      (node (ref "C7") (pin "P$2") (pinfunction "2_P$2") (pintype "passive"))
      (node (ref "C8") (pin "P$2") (pinfunction "2_P$2") (pintype "passive"))
      (node (ref "C9") (pin "P$2") (pinfunction "2_P$2") (pintype "passive"))
      (node (ref "J1") (pin "6") (pinfunction "SUPPLY_VOLTAGE_GROUND_6") (pintype "power_in"))
      (node (ref "J2") (pin "P$1") (pinfunction "P$1_P$1") (pintype "bidirectional"))
      (node (ref "J3") (pin "10") (pinfunction "10_10") (pintype "passive"))
      (node (ref "J3") (pin "6") (pinfunction "6_6") (pintype "passive"))
      (node (ref "J3") (pin "8") (pinfunction "8_8") (pintype "passive"))
      (node (ref "J39") (pin "P$1") (pinfunction "P$1_P$1") (pintype "bidirectional"))
      (node (ref "J39") (pin "P$11") (pinfunction "P$11_P$11") (pintype "bidirectional"))
      (node (ref "J39") (pin "P$13") (pinfunction "P$13_P$13") (pintype "bidirectional"))
      (node (ref "J39") (pin "P$15") (pinfunction "P$15_P$15") (pintype "bidirectional"))
      (node (ref "J39") (pin "P$17") (pinfunction "P$17_P$17") (pintype "bidirectional"))
      (node (ref "J39") (pin "P$19") (pinfunction "P$19_P$19") (pintype "bidirectional"))
      (node (ref "J39") (pin "P$3") (pinfunction "P$3_P$3") (pintype "bidirectional"))
      (node (ref "J39") (pin "P$5") (pinfunction "P$5_P$5") (pintype "bidirectional"))
      (node (ref "J39") (pin "P$7") (pinfunction "P$7_P$7") (pintype "bidirectional"))
      (node (ref "J39") (pin "P$9") (pinfunction "P$9_P$9") (pintype "bidirectional"))
      (node (ref "J6") (pin "GND") (pinfunction "GND_GND") (pintype "power_in"))
      (node (ref "J7") (pin "P$5") (pinfunction "GND_P$5") (pintype "bidirectional"))
      (node (ref "LED1") (pin "2") (pinfunction "C_2") (pintype "passive"))
      (node (ref "LED10") (pin "2") (pinfunction "C_2") (pintype "passive"))
      (node (ref "LED11") (pin "2") (pinfunction "C_2") (pintype "passive"))
      (node (ref "LED12") (pin "2") (pinfunction "C_2") (pintype "passive"))
      (node (ref "LED13") (pin "2") (pinfunction "C_2") (pintype "passive"))
      (node (ref "LED14") (pin "2") (pinfunction "C_2") (pintype "passive"))
      (node (ref "LED15") (pin "2") (pinfunction "C_2") (pintype "passive"))
      (node (ref "LED16") (pin "2") (pinfunction "C_2") (pintype "passive"))
      (node (ref "LED3") (pin "2") (pinfunction "C_2") (pintype "passive"))
      (node (ref "LED6") (pin "2") (pinfunction "C_2") (pintype "passive"))
      (node (ref "LED7") (pin "2") (pinfunction "C_2") (pintype "passive"))
      (node (ref "R1") (pin "P$1") (pinfunction "1_P$1") (pintype "passive"))
      (node (ref "R101") (pin "P$1") (pinfunction "1_P$1") (pintype "passive"))
      (node (ref "R21") (pin "P$1") (pinfunction "1_P$1") (pintype "passive"))
      (node (ref "R22") (pin "P$1") (pinfunction "1_P$1") (pintype "passive"))
      (node (ref "R23") (pin "P$1") (pinfunction "1_P$1") (pintype "passive"))
      (node (ref "R24") (pin "P$1") (pinfunction "1_P$1") (pintype "passive"))
      (node (ref "R34") (pin "P$1") (pinfunction "1_P$1") (pintype "passive"))
      (node (ref "R53") (pin "P$1") (pinfunction "1_P$1") (pintype "passive"))
      (node (ref "R56") (pin "P$1") (pinfunction "1_P$1") (pintype "passive"))
      (node (ref "R59") (pin "P$1") (pinfunction "1_P$1") (pintype "passive"))
      (node (ref "R74") (pin "P$1") (pinfunction "1_P$1") (pintype "passive"))
      (node (ref "R77") (pin "P$1") (pinfunction "1_P$1") (pintype "passive"))
      (node (ref "R80") (pin "P$1") (pinfunction "1_P$1") (pintype "passive"))
      (node (ref "R83") (pin "P$1") (pinfunction "1_P$1") (pintype "passive"))
      (node (ref "R98") (pin "P$1") (pinfunction "1_P$1") (pintype "passive"))
      (node (ref "RJ1") (pin "10") (pinfunction "GLO_10") (pintype "bidirectional"))
      (node (ref "RJ1") (pin "8") (pinfunction "P8_8") (pintype "bidirectional"))
      (node (ref "U1") (pin "22") (pinfunction "GND_22") (pintype "power_in"))
      (node (ref "U1") (pin "25") (pinfunction "25_25") (pintype "passive"))
      (node (ref "U10") (pin "2") (pinfunction "E(1)_2") (pintype "output"))
      (node (ref "U11") (pin "2") (pinfunction "E(1)_2") (pintype "output"))
      (node (ref "U12") (pin "2") (pinfunction "E(1)_2") (pintype "output"))
      (node (ref "U13") (pin "2") (pinfunction "E(1)_2") (pintype "output"))
      (node (ref "U14") (pin "2") (pinfunction "E(1)_2") (pintype "output"))
      (node (ref "U15") (pin "2") (pinfunction "E(1)_2") (pintype "output"))
      (node (ref "U16") (pin "2") (pinfunction "E(1)_2") (pintype "output"))
      (node (ref "U17") (pin "2") (pinfunction "E(1)_2") (pintype "output"))
      (node (ref "U2") (pin "2") (pinfunction "GND_2") (pintype "input"))
      (node (ref "U22") (pin "2") (pinfunction "E(1)_2") (pintype "output"))
      (node (ref "U23") (pin "2") (pinfunction "E(1)_2") (pintype "output"))
      (node (ref "U24") (pin "2") (pinfunction "E(1)_2") (pintype "output"))
      (node (ref "U25") (pin "2") (pinfunction "E(1)_2") (pintype "output"))
      (node (ref "U26") (pin "2") (pinfunction "E(1)_2") (pintype "output"))
      (node (ref "U27") (pin "2") (pinfunction "E(1)_2") (pintype "output"))
      (node (ref "U3") (pin "111") (pinfunction "VSS(IO)5_111") (pintype "bidirectional"))
      (node (ref "U3") (pin "124") (pinfunction "VSS(IO)6_124") (pintype "bidirectional"))
      (node (ref "U3") (pin "139") (pinfunction "VSS(IO)7_139") (pintype "bidirectional"))
      (node (ref "U3") (pin "150") (pinfunction "VSS(IO)8_150") (pintype "bidirectional"))
      (node (ref "U3") (pin "153") (pinfunction "VREFL_153") (pintype "bidirectional"))
      (node (ref "U3") (pin "156") (pinfunction "AVSS0_156") (pintype "bidirectional"))
      (node (ref "U3") (pin "157") (pinfunction "VREFL0_157") (pintype "bidirectional"))
      (node (ref "U3") (pin "170") (pinfunction "VSS(IO)9_170") (pintype "bidirectional"))
      (node (ref "U3") (pin "22") (pinfunction "VSS1_22") (pintype "bidirectional"))
      (node (ref "U3") (pin "28") (pinfunction "AVSS_USBHS_28") (pintype "bidirectional"))
      (node (ref "U3") (pin "29") (pinfunction "PVSS_USBHS_29") (pintype "bidirectional"))
      (node (ref "U3") (pin "30") (pinfunction "VSS2_USBHS_30") (pintype "bidirectional"))
      (node (ref "U3") (pin "33") (pinfunction "VSS1_USBHS_33") (pintype "bidirectional"))
      (node (ref "U3") (pin "35") (pinfunction "VSSIO_35") (pintype "bidirectional"))
      (node (ref "U3") (pin "45") (pinfunction "VSS_USB_45") (pintype "bidirectional"))
      (node (ref "U3") (pin "60") (pinfunction "VSS(IO)2_60") (pintype "bidirectional"))
      (node (ref "U3") (pin "63") (pinfunction "VSS(IO/DCDC)_63") (pintype "bidirectional"))
      (node (ref "U3") (pin "66") (pinfunction "VCC_DCDC(IO/DCDC)_66") (pintype "bidirectional"))
      (node (ref "U3") (pin "83") (pinfunction "VSS(IO)3_83") (pintype "bidirectional"))
      (node (ref "U3") (pin "98") (pinfunction "VSS(IO)4_98") (pintype "bidirectional"))
      (node (ref "U34") (pin "2") (pinfunction "E(1)_2") (pintype "output"))
      (node (ref "U35") (pin "2") (pinfunction "E(1)_2") (pintype "output"))
      (node (ref "U36") (pin "2") (pinfunction "E(1)_2") (pintype "output"))
      (node (ref "U37") (pin "2") (pinfunction "E(1)_2") (pintype "output"))
      (node (ref "U38") (pin "2") (pinfunction "E(1)_2") (pintype "output"))
      (node (ref "U39") (pin "2") (pinfunction "E(1)_2") (pintype "output"))
      (node (ref "U46") (pin "2") (pinfunction "E(1)_2") (pintype "output"))
      (node (ref "U47") (pin "2") (pinfunction "E(1)_2") (pintype "output"))
      (node (ref "U48") (pin "2") (pinfunction "E(1)_2") (pintype "output"))
      (node (ref "U49") (pin "2") (pinfunction "E(1)_2") (pintype "output"))
      (node (ref "U50") (pin "2") (pinfunction "E(1)_2") (pintype "output"))
      (node (ref "U51") (pin "2") (pinfunction "E(1)_2") (pintype "output"))
      (node (ref "U58") (pin "2") (pinfunction "E(1)_2") (pintype "output"))
      (node (ref "U59") (pin "2") (pinfunction "E(1)_2") (pintype "output"))
      (node (ref "U6") (pin "2") (pinfunction "E(1)_2") (pintype "output"))
      (node (ref "U60") (pin "2") (pinfunction "E(1)_2") (pintype "output"))
      (node (ref "U61") (pin "2") (pinfunction "E(1)_2") (pintype "output"))
      (node (ref "U62") (pin "2") (pinfunction "E(1)_2") (pintype "output"))
      (node (ref "U63") (pin "2") (pinfunction "E(1)_2") (pintype "output"))
      (node (ref "U7") (pin "2") (pinfunction "E(1)_2") (pintype "output"))
      (node (ref "U70") (pin "2") (pinfunction "E(1)_2") (pintype "output"))
      (node (ref "U71") (pin "2") (pinfunction "E(1)_2") (pintype "output"))
      (node (ref "U72") (pin "2") (pinfunction "E(1)_2") (pintype "output"))
      (node (ref "U73") (pin "2") (pinfunction "E(1)_2") (pintype "output"))
      (node (ref "U74") (pin "2") (pinfunction "E(1)_2") (pintype "output"))
      (node (ref "U75") (pin "2") (pinfunction "E(1)_2") (pintype "output"))
      (node (ref "X1") (pin "2") (pinfunction "2_2") (pintype "bidirectional"))
      (node (ref "X1") (pin "4") (pinfunction "4_4") (pintype "bidirectional"))
      (node (ref "X2") (pin "2") (pinfunction "2_2") (pintype "bidirectional"))
      (node (ref "X2") (pin "4") (pinfunction "4_4") (pintype "bidirectional"))
    )
    (net (code "48") (name "GNDE") (class "Default")
      (node (ref "J1") (pin "S1") (pinfunction "SHIELD_S1") (pintype "passive"))
      (node (ref "J1") (pin "S2") (pinfunction "SHIELD_S2") (pintype "passive"))
      (node (ref "J1") (pin "S3") (pinfunction "SHIELD_S3") (pintype "passive"))
      (node (ref "J1") (pin "S4") (pinfunction "SHIELD_S4") (pintype "passive"))
      (node (ref "J2") (pin "P$4") (pinfunction "P$4_P$4") (pintype "bidirectional"))
      (node (ref "J6") (pin "SHLD1") (pinfunction "SHIELD_1_SHLD1") (pintype "bidirectional"))
      (node (ref "J6") (pin "SHLD2") (pinfunction "SHIELD_2_SHLD2") (pintype "bidirectional"))
      (node (ref "J7") (pin "P$6") (pinfunction "SHIELD1_P$6") (pintype "bidirectional"))
      (node (ref "J7") (pin "P$7") (pinfunction "SHIELD2_P$7") (pintype "bidirectional"))
      (node (ref "J7") (pin "P$8") (pinfunction "SHIELD3_P$8") (pintype "bidirectional"))
      (node (ref "J7") (pin "P$9") (pinfunction "SHIELD4_P$9") (pintype "bidirectional"))
      (node (ref "RJ1") (pin "13") (pinfunction "GNDE0_13") (pintype "bidirectional"))
      (node (ref "RJ1") (pin "14") (pinfunction "GNDE1_14") (pintype "bidirectional"))
    )
    (net (code "49") (name "ID") (class "Default")
      (node (ref "J7") (pin "P$4") (pinfunction "ID_P$4") (pintype "bidirectional"))
    )
    (net (code "50") (name "IIC_1_SCL") (class "Default")
      (node (ref "J8") (pin "P$8") (pinfunction "P$8_P$8") (pintype "bidirectional"))
      (node (ref "R14") (pin "P$2") (pinfunction "2_P$2") (pintype "passive"))
      (node (ref "U3") (pin "132") (pinfunction "P1_0_132") (pintype "bidirectional"))
    )
    (net (code "51") (name "IIC_1_SDA") (class "Default")
      (node (ref "J8") (pin "P$7") (pinfunction "P$7_P$7") (pintype "bidirectional"))
      (node (ref "R15") (pin "P$2") (pinfunction "2_P$2") (pintype "passive"))
      (node (ref "U3") (pin "131") (pinfunction "P1_1_131") (pintype "bidirectional"))
    )
    (net (code "52") (name "LED1{slash}SPEED") (class "Default")
      (node (ref "RJ1") (pin "11") (pinfunction "YLO_11") (pintype "bidirectional"))
      (node (ref "U1") (pin "23") (pinfunction "LED0/ANEN_SPEED_23") (pintype "bidirectional"))
    )
    (net (code "53") (name "LS_01") (class "Default")
      (node (ref "R33") (pin "P$2") (pinfunction "2_P$2") (pintype "passive"))
      (node (ref "R34") (pin "P$2") (pinfunction "2_P$2") (pintype "passive"))
      (node (ref "U3") (pin "50") (pinfunction "P2_6_50") (pintype "bidirectional"))
      (node (ref "U5") (pin "2") (pinfunction "E(1)_2") (pintype "output"))
    )
    (net (code "54") (name "LS_01_RET") (class "Default")
      (node (ref "J11") (pin "P$1") (pinfunction "P$1_P$1") (pintype "bidirectional"))
      (node (ref "R28") (pin "P$1") (pinfunction "1_P$1") (pintype "passive"))
    )
    (net (code "55") (name "LS_02") (class "Default")
      (node (ref "R36") (pin "P$2") (pinfunction "2_P$2") (pintype "passive"))
      (node (ref "R53") (pin "P$2") (pinfunction "2_P$2") (pintype "passive"))
      (node (ref "U3") (pin "51") (pinfunction "P2_5_51") (pintype "bidirectional"))
      (node (ref "U8") (pin "2") (pinfunction "E(1)_2") (pintype "output"))
    )
    (net (code "56") (name "LS_02_RET") (class "Default")
      (node (ref "J12") (pin "P$1") (pinfunction "P$1_P$1") (pintype "bidirectional"))
      (node (ref "R35") (pin "P$1") (pinfunction "1_P$1") (pintype "passive"))
    )
    (net (code "57") (name "LS_03") (class "Default")
      (node (ref "R55") (pin "P$2") (pinfunction "2_P$2") (pintype "passive"))
      (node (ref "R56") (pin "P$2") (pinfunction "2_P$2") (pintype "passive"))
      (node (ref "U3") (pin "53") (pinfunction "P2_3_53") (pintype "bidirectional"))
      (node (ref "U9") (pin "2") (pinfunction "E(1)_2") (pintype "output"))
    )
    (net (code "58") (name "LS_03_RET") (class "Default")
      (node (ref "J19") (pin "P$1") (pinfunction "P$1_P$1") (pintype "bidirectional"))
      (node (ref "R54") (pin "P$1") (pinfunction "1_P$1") (pintype "passive"))
    )
    (net (code "59") (name "LS_04") (class "Default")
      (node (ref "R73") (pin "P$2") (pinfunction "2_P$2") (pintype "passive"))
      (node (ref "R74") (pin "P$2") (pinfunction "2_P$2") (pintype "passive"))
      (node (ref "U19") (pin "2") (pinfunction "E(1)_2") (pintype "output"))
      (node (ref "U3") (pin "54") (pinfunction "P2_2_54") (pintype "bidirectional"))
    )
    (net (code "60") (name "LS_04_RET") (class "Default")
      (node (ref "J20") (pin "P$1") (pinfunction "P$1_P$1") (pintype "bidirectional"))
      (node (ref "R60") (pin "P$1") (pinfunction "1_P$1") (pintype "passive"))
    )
    (net (code "61") (name "LS_05") (class "Default")
      (node (ref "R58") (pin "P$2") (pinfunction "2_P$2") (pintype "passive"))
      (node (ref "R59") (pin "P$2") (pinfunction "2_P$2") (pintype "passive"))
      (node (ref "U18") (pin "2") (pinfunction "E(1)_2") (pintype "output"))
      (node (ref "U3") (pin "81") (pinfunction "P3_5_81") (pintype "bidirectional"))
    )
    (net (code "62") (name "LS_05_RET") (class "Default")
      (node (ref "J27") (pin "P$1") (pinfunction "P$1_P$1") (pintype "bidirectional"))
      (node (ref "R57") (pin "P$1") (pinfunction "1_P$1") (pintype "passive"))
    )
    (net (code "63") (name "LS_06") (class "Default")
      (node (ref "R76") (pin "P$2") (pinfunction "2_P$2") (pintype "passive"))
      (node (ref "R77") (pin "P$2") (pinfunction "2_P$2") (pintype "passive"))
      (node (ref "U20") (pin "2") (pinfunction "E(1)_2") (pintype "output"))
      (node (ref "U3") (pin "82") (pinfunction "P3_4_82") (pintype "bidirectional"))
    )
    (net (code "64") (name "LS_06_RET") (class "Default")
      (node (ref "J28") (pin "P$1") (pinfunction "P$1_P$1") (pintype "bidirectional"))
      (node (ref "R75") (pin "P$1") (pinfunction "1_P$1") (pintype "passive"))
    )
    (net (code "65") (name "LS_07") (class "Default")
      (node (ref "R97") (pin "P$2") (pinfunction "2_P$2") (pintype "passive"))
      (node (ref "R98") (pin "P$2") (pinfunction "2_P$2") (pintype "passive"))
      (node (ref "U29") (pin "2") (pinfunction "E(1)_2") (pintype "output"))
      (node (ref "U3") (pin "86") (pinfunction "P3_2_86") (pintype "bidirectional"))
    )
    (net (code "66") (name "LS_07_RET") (class "Default")
      (node (ref "J31") (pin "P$1") (pinfunction "P$1_P$1") (pintype "bidirectional"))
      (node (ref "R84") (pin "P$1") (pinfunction "1_P$1") (pintype "passive"))
    )
    (net (code "67") (name "LS_08") (class "Default")
      (node (ref "R82") (pin "P$2") (pinfunction "2_P$2") (pintype "passive"))
      (node (ref "R83") (pin "P$2") (pinfunction "2_P$2") (pintype "passive"))
      (node (ref "U28") (pin "2") (pinfunction "E(1)_2") (pintype "output"))
      (node (ref "U3") (pin "87") (pinfunction "P3_1_87") (pintype "bidirectional"))
    )
    (net (code "68") (name "LS_08_RET") (class "Default")
      (node (ref "P1") (pin "P$1") (pinfunction "P$1_P$1") (pintype "bidirectional"))
      (node (ref "R81") (pin "P$1") (pinfunction "1_P$1") (pintype "passive"))
    )
    (net (code "69") (name "LS_09") (class "Default")
      (node (ref "R100") (pin "P$2") (pinfunction "2_P$2") (pintype "passive"))
      (node (ref "R101") (pin "P$2") (pinfunction "2_P$2") (pintype "passive"))
      (node (ref "U3") (pin "92") (pinfunction "P1_11_92") (pintype "bidirectional"))
      (node (ref "U30") (pin "2") (pinfunction "E(1)_2") (pintype "output"))
    )
    (net (code "70") (name "LS_09_RET") (class "Default")
      (node (ref "P3") (pin "P$1") (pinfunction "P$1_P$1") (pintype "bidirectional"))
      (node (ref "R99") (pin "P$1") (pinfunction "1_P$1") (pintype "passive"))
    )
    (net (code "71") (name "N$88") (class "Default")
      (node (ref "J8") (pin "P$20") (pinfunction "P$20_P$20") (pintype "bidirectional"))
    )
    (net (code "72") (name "N$89") (class "Default")
      (node (ref "J8") (pin "P$18") (pinfunction "P$18_P$18") (pintype "bidirectional"))
    )
    (net (code "73") (name "N$90") (class "Default")
      (node (ref "J8") (pin "P$16") (pinfunction "P$16_P$16") (pintype "bidirectional"))
    )
    (net (code "74") (name "N$91") (class "Default")
      (node (ref "J8") (pin "P$14") (pinfunction "P$14_P$14") (pintype "bidirectional"))
    )
    (net (code "75") (name "N$92") (class "Default")
      (node (ref "J8") (pin "P$12") (pinfunction "P$12_P$12") (pintype "bidirectional"))
    )
    (net (code "76") (name "NC") (class "Default")
      (node (ref "J8") (pin "P$6") (pinfunction "P$6_P$6") (pintype "bidirectional"))
      (node (ref "RJ1") (pin "7") (pinfunction "P7_7") (pintype "bidirectional"))
      (node (ref "U3") (pin "79") (pinfunction "P3_7_79") (pintype "bidirectional"))
      (node (ref "U3") (pin "80") (pinfunction "P3_6_80") (pintype "bidirectional"))
      (node (ref "U3") (pin "85") (pinfunction "P3_3_85") (pintype "bidirectional"))
    )
    (net (code "77") (name "Net-(C8-1)") (class "Default")
      (node (ref "C8") (pin "P$1") (pinfunction "1_P$1") (pintype "passive"))
      (node (ref "C9") (pin "P$1") (pinfunction "1_P$1") (pintype "passive"))
      (node (ref "FB1") (pin "2") (pinfunction "P$2_2") (pintype "bidirectional"))
      (node (ref "U1") (pin "2") (pinfunction "VDDA_3.3_2") (pintype "power_in"))
    )
    (net (code "78") (name "Net-(C24-2)") (class "Default")
      (node (ref "C24") (pin "P$2") (pinfunction "2_P$2") (pintype "passive"))
      (node (ref "U3") (pin "148") (pinfunction "VCL2_148") (pintype "bidirectional"))
    )
    (net (code "79") (name "Net-(C28-1)") (class "Default")
      (node (ref "C28") (pin "P$1") (pinfunction "1_P$1") (pintype "passive"))
      (node (ref "J7") (pin "P$1") (pinfunction "VBUS_P$1") (pintype "bidirectional"))
      (node (ref "R16") (pin "P$2") (pinfunction "2_P$2") (pintype "passive"))
      (node (ref "R21") (pin "P$2") (pinfunction "2_P$2") (pintype "passive"))
    )
    (net (code "80") (name "Net-(C33-1)") (class "Default")
      (node (ref "C33") (pin "P$1") (pinfunction "1_P$1") (pintype "passive"))
      (node (ref "U3") (pin "19") (pinfunction "VCLO_19") (pintype "bidirectional"))
    )
    (net (code "81") (name "Net-(C42-1)") (class "Default")
      (node (ref "C42") (pin "P$1") (pinfunction "1_P$1") (pintype "passive"))
      (node (ref "U3") (pin "62") (pinfunction "VCL1_62") (pintype "bidirectional"))
    )
    (net (code "82") (name "Net-(J7-D+)") (class "Default")
      (node (ref "J7") (pin "P$3") (pinfunction "D+_P$3") (pintype "bidirectional"))
      (node (ref "R18") (pin "P$2") (pinfunction "2_P$2") (pintype "passive"))
    )
    (net (code "83") (name "Net-(J7-D-)") (class "Default")
      (node (ref "J7") (pin "P$2") (pinfunction "D-_P$2") (pintype "bidirectional"))
      (node (ref "R17") (pin "P$2") (pinfunction "2_P$2") (pintype "passive"))
    )
    (net (code "84") (name "Net-(LED1-A)") (class "Default")
      (node (ref "LED1") (pin "1") (pinfunction "A_1") (pintype "passive"))
      (node (ref "R5") (pin "P$1") (pinfunction "1_P$1") (pintype "passive"))
    )
    (net (code "85") (name "Net-(LED3-A)") (class "Default")
      (node (ref "LED3") (pin "1") (pinfunction "A_1") (pintype "passive"))
      (node (ref "R33") (pin "P$1") (pinfunction "1_P$1") (pintype "passive"))
    )
    (net (code "86") (name "Net-(LED4-A)") (class "Default")
      (node (ref "LED4") (pin "1") (pinfunction "A_1") (pintype "passive"))
      (node (ref "R32") (pin "P$1") (pinfunction "1_P$1") (pintype "passive"))
    )
    (net (code "87") (name "Net-(LED4-C)") (class "Default")
      (node (ref "LED4") (pin "2") (pinfunction "C_2") (pintype "passive"))
      (node (ref "U$1") (pin "P$1") (pinfunction "VC-_P$1") (pintype "bidirectional"))
      (node (ref "U6") (pin "3") (pinfunction "C(3)_3") (pintype "input"))
    )
    (net (code "88") (name "Net-(LED5-A)") (class "Default")
      (node (ref "LED5") (pin "1") (pinfunction "A_1") (pintype "passive"))
      (node (ref "R31") (pin "P$1") (pinfunction "1_P$1") (pintype "passive"))
    )
    (net (code "89") (name "Net-(LED5-C)") (class "Default")
      (node (ref "LED5") (pin "2") (pinfunction "C_2") (pintype "passive"))
      (node (ref "U$2") (pin "P$1") (pinfunction "VC-_P$1") (pintype "bidirectional"))
      (node (ref "U7") (pin "3") (pinfunction "C(3)_3") (pintype "input"))
    )
    (net (code "90") (name "Net-(LED6-A)") (class "Default")
      (node (ref "LED6") (pin "1") (pinfunction "A_1") (pintype "passive"))
      (node (ref "R36") (pin "P$1") (pinfunction "1_P$1") (pintype "passive"))
    )
    (net (code "91") (name "Net-(LED7-A)") (class "Default")
      (node (ref "LED7") (pin "1") (pinfunction "A_1") (pintype "passive"))
      (node (ref "R55") (pin "P$1") (pinfunction "1_P$1") (pintype "passive"))
    )
    (net (code "92") (name "Net-(LED8-A)") (class "Default")
      (node (ref "LED8") (pin "1") (pinfunction "A_1") (pintype "passive"))
      (node (ref "R52") (pin "P$1") (pinfunction "1_P$1") (pintype "passive"))
    )
    (net (code "93") (name "Net-(LED8-C)") (class "Default")
      (node (ref "LED8") (pin "2") (pinfunction "C_2") (pintype "passive"))
      (node (ref "U$7") (pin "P$1") (pinfunction "VC-_P$1") (pintype "bidirectional"))
      (node (ref "U16") (pin "3") (pinfunction "C(3)_3") (pintype "input"))
    )
    (net (code "94") (name "Net-(LED9-A)") (class "Default")
      (node (ref "LED9") (pin "1") (pinfunction "A_1") (pintype "passive"))
      (node (ref "R51") (pin "P$1") (pinfunction "1_P$1") (pintype "passive"))
    )
    (net (code "95") (name "Net-(LED9-C)") (class "Default")
      (node (ref "LED9") (pin "2") (pinfunction "C_2") (pintype "passive"))
      (node (ref "U$8") (pin "P$1") (pinfunction "VC-_P$1") (pintype "bidirectional"))
      (node (ref "U17") (pin "3") (pinfunction "C(3)_3") (pintype "input"))
    )
    (net (code "96") (name "Net-(LED10-A)") (class "Default")
      (node (ref "LED10") (pin "1") (pinfunction "A_1") (pintype "passive"))
      (node (ref "R58") (pin "P$1") (pinfunction "1_P$1") (pintype "passive"))
    )
    (net (code "97") (name "Net-(LED11-A)") (class "Default")
      (node (ref "LED11") (pin "1") (pinfunction "A_1") (pintype "passive"))
      (node (ref "R73") (pin "P$1") (pinfunction "1_P$1") (pintype "passive"))
    )
    (net (code "98") (name "Net-(LED12-A)") (class "Default")
      (node (ref "LED12") (pin "1") (pinfunction "A_1") (pintype "passive"))
      (node (ref "R76") (pin "P$1") (pinfunction "1_P$1") (pintype "passive"))
    )
    (net (code "99") (name "Net-(LED13-A)") (class "Default")
      (node (ref "LED13") (pin "1") (pinfunction "A_1") (pintype "passive"))
      (node (ref "R79") (pin "P$1") (pinfunction "1_P$1") (pintype "passive"))
    )
    (net (code "100") (name "Net-(LED14-A)") (class "Default")
      (node (ref "LED14") (pin "1") (pinfunction "A_1") (pintype "passive"))
      (node (ref "R82") (pin "P$1") (pinfunction "1_P$1") (pintype "passive"))
    )
    (net (code "101") (name "Net-(LED15-A)") (class "Default")
      (node (ref "LED15") (pin "1") (pinfunction "A_1") (pintype "passive"))
      (node (ref "R97") (pin "P$1") (pinfunction "1_P$1") (pintype "passive"))
    )
    (net (code "102") (name "Net-(LED16-A)") (class "Default")
      (node (ref "LED16") (pin "1") (pinfunction "A_1") (pintype "passive"))
      (node (ref "R100") (pin "P$1") (pinfunction "1_P$1") (pintype "passive"))
    )
    (net (code "103") (name "Net-(R22-2)") (class "Default")
      (node (ref "R22") (pin "P$2") (pinfunction "2_P$2") (pintype "passive"))
      (node (ref "U3") (pin "27") (pinfunction "USBHS_RREF_27") (pintype "bidirectional"))
    )
    (net (code "104") (name "Net-(R23-2)") (class "Default")
      (node (ref "R23") (pin "P$2") (pinfunction "2_P$2") (pintype "passive"))
      (node (ref "U3") (pin "64") (pinfunction "VLO1(DCDC)_64") (pintype "bidirectional"))
    )
    (net (code "105") (name "Net-(R24-2)") (class "Default")
      (node (ref "R24") (pin "P$2") (pinfunction "2_P$2") (pintype "passive"))
      (node (ref "U3") (pin "65") (pinfunction "VLO2(DCDC)_65") (pintype "bidirectional"))
    )
    (net (code "106") (name "Net-(R28-2)") (class "Default")
      (node (ref "R28") (pin "P$2") (pinfunction "2_P$2") (pintype "passive"))
      (node (ref "U5") (pin "1") (pinfunction "B(2)_1") (pintype "input"))
    )
    (net (code "107") (name "Net-(R29-2)") (class "Default")
      (node (ref "R29") (pin "P$2") (pinfunction "2_P$2") (pintype "passive"))
      (node (ref "U6") (pin "1") (pinfunction "B(2)_1") (pintype "input"))
    )
    (net (code "108") (name "Net-(R30-2)") (class "Default")
      (node (ref "R30") (pin "P$2") (pinfunction "2_P$2") (pintype "passive"))
      (node (ref "U7") (pin "1") (pinfunction "B(2)_1") (pintype "input"))
    )
    (net (code "109") (name "Net-(R35-2)") (class "Default")
      (node (ref "R35") (pin "P$2") (pinfunction "2_P$2") (pintype "passive"))
      (node (ref "U8") (pin "1") (pinfunction "B(2)_1") (pintype "input"))
    )
    (net (code "110") (name "Net-(R49-2)") (class "Default")
      (node (ref "R49") (pin "P$2") (pinfunction "2_P$2") (pintype "passive"))
      (node (ref "U16") (pin "1") (pinfunction "B(2)_1") (pintype "input"))
    )
    (net (code "111") (name "Net-(R50-2)") (class "Default")
      (node (ref "R50") (pin "P$2") (pinfunction "2_P$2") (pintype "passive"))
      (node (ref "U17") (pin "1") (pinfunction "B(2)_1") (pintype "input"))
    )
    (net (code "112") (name "Net-(R54-2)") (class "Default")
      (node (ref "R54") (pin "P$2") (pinfunction "2_P$2") (pintype "passive"))
      (node (ref "U9") (pin "1") (pinfunction "B(2)_1") (pintype "input"))
    )
    (net (code "113") (name "Net-(R57-2)") (class "Default")
      (node (ref "R57") (pin "P$2") (pinfunction "2_P$2") (pintype "passive"))
      (node (ref "U18") (pin "1") (pinfunction "B(2)_1") (pintype "input"))
    )
    (net (code "114") (name "Net-(R60-2)") (class "Default")
      (node (ref "R60") (pin "P$2") (pinfunction "2_P$2") (pintype "passive"))
      (node (ref "U19") (pin "1") (pinfunction "B(2)_1") (pintype "input"))
    )
    (net (code "115") (name "Net-(R75-2)") (class "Default")
      (node (ref "R75") (pin "P$2") (pinfunction "2_P$2") (pintype "passive"))
      (node (ref "U20") (pin "1") (pinfunction "B(2)_1") (pintype "input"))
    )
    (net (code "116") (name "Net-(R78-2)") (class "Default")
      (node (ref "R78") (pin "P$2") (pinfunction "2_P$2") (pintype "passive"))
      (node (ref "U21") (pin "1") (pinfunction "B(2)_1") (pintype "input"))
    )
    (net (code "117") (name "Net-(R81-2)") (class "Default")
      (node (ref "R81") (pin "P$2") (pinfunction "2_P$2") (pintype "passive"))
      (node (ref "U28") (pin "1") (pinfunction "B(2)_1") (pintype "input"))
    )
    (net (code "118") (name "Net-(R84-2)") (class "Default")
      (node (ref "R84") (pin "P$2") (pinfunction "2_P$2") (pintype "passive"))
      (node (ref "U29") (pin "1") (pinfunction "B(2)_1") (pintype "input"))
    )
    (net (code "119") (name "Net-(R99-2)") (class "Default")
      (node (ref "R99") (pin "P$2") (pinfunction "2_P$2") (pintype "passive"))
      (node (ref "U30") (pin "1") (pinfunction "B(2)_1") (pintype "input"))
    )
    (net (code "120") (name "Net-(U10-B(2))") (class "Default")
      (node (ref "R38") (pin "2") (pinfunction "2_2") (pintype "passive"))
      (node (ref "U10") (pin "1") (pinfunction "B(2)_1") (pintype "input"))
    )
    (net (code "121") (name "Net-(U11-B(2))") (class "Default")
      (node (ref "R39") (pin "2") (pinfunction "2_2") (pintype "passive"))
      (node (ref "U11") (pin "1") (pinfunction "B(2)_1") (pintype "input"))
    )
    (net (code "122") (name "Net-(U12-B(2))") (class "Default")
      (node (ref "R40") (pin "2") (pinfunction "2_2") (pintype "passive"))
      (node (ref "U12") (pin "1") (pinfunction "B(2)_1") (pintype "input"))
    )
    (net (code "123") (name "Net-(U13-B(2))") (class "Default")
      (node (ref "R44") (pin "2") (pinfunction "2_2") (pintype "passive"))
      (node (ref "U13") (pin "1") (pinfunction "B(2)_1") (pintype "input"))
    )
    (net (code "124") (name "Net-(U14-B(2))") (class "Default")
      (node (ref "R45") (pin "2") (pinfunction "2_2") (pintype "passive"))
      (node (ref "U14") (pin "1") (pinfunction "B(2)_1") (pintype "input"))
    )
    (net (code "125") (name "Net-(U15-B(2))") (class "Default")
      (node (ref "R46") (pin "2") (pinfunction "2_2") (pintype "passive"))
      (node (ref "U15") (pin "1") (pinfunction "B(2)_1") (pintype "input"))
    )
    (net (code "126") (name "Net-(U22-B(2))") (class "Default")
      (node (ref "R62") (pin "2") (pinfunction "2_2") (pintype "passive"))
      (node (ref "U22") (pin "1") (pinfunction "B(2)_1") (pintype "input"))
    )
    (net (code "127") (name "Net-(U23-B(2))") (class "Default")
      (node (ref "R63") (pin "2") (pinfunction "2_2") (pintype "passive"))
      (node (ref "U23") (pin "1") (pinfunction "B(2)_1") (pintype "input"))
    )
    (net (code "128") (name "Net-(U24-B(2))") (class "Default")
      (node (ref "R64") (pin "2") (pinfunction "2_2") (pintype "passive"))
      (node (ref "U24") (pin "1") (pinfunction "B(2)_1") (pintype "input"))
    )
    (net (code "129") (name "Net-(U25-B(2))") (class "Default")
      (node (ref "R68") (pin "2") (pinfunction "2_2") (pintype "passive"))
      (node (ref "U25") (pin "1") (pinfunction "B(2)_1") (pintype "input"))
    )
    (net (code "130") (name "Net-(U26-B(2))") (class "Default")
      (node (ref "R69") (pin "2") (pinfunction "2_2") (pintype "passive"))
      (node (ref "U26") (pin "1") (pinfunction "B(2)_1") (pintype "input"))
    )
    (net (code "131") (name "Net-(U27-B(2))") (class "Default")
      (node (ref "R70") (pin "2") (pinfunction "2_2") (pintype "passive"))
      (node (ref "U27") (pin "1") (pinfunction "B(2)_1") (pintype "input"))
    )
    (net (code "132") (name "Net-(U34-B(2))") (class "Default")
      (node (ref "R86") (pin "2") (pinfunction "2_2") (pintype "passive"))
      (node (ref "U34") (pin "1") (pinfunction "B(2)_1") (pintype "input"))
    )
    (net (code "133") (name "Net-(U35-B(2))") (class "Default")
      (node (ref "R87") (pin "2") (pinfunction "2_2") (pintype "passive"))
      (node (ref "U35") (pin "1") (pinfunction "B(2)_1") (pintype "input"))
    )
    (net (code "134") (name "Net-(U36-B(2))") (class "Default")
      (node (ref "R88") (pin "2") (pinfunction "2_2") (pintype "passive"))
      (node (ref "U36") (pin "1") (pinfunction "B(2)_1") (pintype "input"))
    )
    (net (code "135") (name "Net-(U37-B(2))") (class "Default")
      (node (ref "R92") (pin "2") (pinfunction "2_2") (pintype "passive"))
      (node (ref "U37") (pin "1") (pinfunction "B(2)_1") (pintype "input"))
    )
    (net (code "136") (name "Net-(U38-B(2))") (class "Default")
      (node (ref "R93") (pin "2") (pinfunction "2_2") (pintype "passive"))
      (node (ref "U38") (pin "1") (pinfunction "B(2)_1") (pintype "input"))
    )
    (net (code "137") (name "Net-(U39-B(2))") (class "Default")
      (node (ref "R94") (pin "2") (pinfunction "2_2") (pintype "passive"))
      (node (ref "U39") (pin "1") (pinfunction "B(2)_1") (pintype "input"))
    )
    (net (code "138") (name "Net-(U46-B(2))") (class "Default")
      (node (ref "R110") (pin "2") (pinfunction "2_2") (pintype "passive"))
      (node (ref "U46") (pin "1") (pinfunction "B(2)_1") (pintype "input"))
    )
    (net (code "139") (name "Net-(U47-B(2))") (class "Default")
      (node (ref "R111") (pin "2") (pinfunction "2_2") (pintype "passive"))
      (node (ref "U47") (pin "1") (pinfunction "B(2)_1") (pintype "input"))
    )
    (net (code "140") (name "Net-(U48-B(2))") (class "Default")
      (node (ref "R112") (pin "2") (pinfunction "2_2") (pintype "passive"))
      (node (ref "U48") (pin "1") (pinfunction "B(2)_1") (pintype "input"))
    )
    (net (code "141") (name "Net-(U49-B(2))") (class "Default")
      (node (ref "R116") (pin "2") (pinfunction "2_2") (pintype "passive"))
      (node (ref "U49") (pin "1") (pinfunction "B(2)_1") (pintype "input"))
    )
    (net (code "142") (name "Net-(U50-B(2))") (class "Default")
      (node (ref "R117") (pin "2") (pinfunction "2_2") (pintype "passive"))
      (node (ref "U50") (pin "1") (pinfunction "B(2)_1") (pintype "input"))
    )
    (net (code "143") (name "Net-(U51-B(2))") (class "Default")
      (node (ref "R118") (pin "2") (pinfunction "2_2") (pintype "passive"))
      (node (ref "U51") (pin "1") (pinfunction "B(2)_1") (pintype "input"))
    )
    (net (code "144") (name "Net-(U58-B(2))") (class "Default")
      (node (ref "R134") (pin "2") (pinfunction "2_2") (pintype "passive"))
      (node (ref "U58") (pin "1") (pinfunction "B(2)_1") (pintype "input"))
    )
    (net (code "145") (name "Net-(U59-B(2))") (class "Default")
      (node (ref "R135") (pin "2") (pinfunction "2_2") (pintype "passive"))
      (node (ref "U59") (pin "1") (pinfunction "B(2)_1") (pintype "input"))
    )
    (net (code "146") (name "Net-(U60-B(2))") (class "Default")
      (node (ref "R136") (pin "2") (pinfunction "2_2") (pintype "passive"))
      (node (ref "U60") (pin "1") (pinfunction "B(2)_1") (pintype "input"))
    )
    (net (code "147") (name "Net-(U61-B(2))") (class "Default")
      (node (ref "R140") (pin "2") (pinfunction "2_2") (pintype "passive"))
      (node (ref "U61") (pin "1") (pinfunction "B(2)_1") (pintype "input"))
    )
    (net (code "148") (name "Net-(U62-B(2))") (class "Default")
      (node (ref "R141") (pin "2") (pinfunction "2_2") (pintype "passive"))
      (node (ref "U62") (pin "1") (pinfunction "B(2)_1") (pintype "input"))
    )
    (net (code "149") (name "Net-(U63-B(2))") (class "Default")
      (node (ref "R142") (pin "2") (pinfunction "2_2") (pintype "passive"))
      (node (ref "U63") (pin "1") (pinfunction "B(2)_1") (pintype "input"))
    )
    (net (code "150") (name "Net-(U70-B(2))") (class "Default")
      (node (ref "R158") (pin "2") (pinfunction "2_2") (pintype "passive"))
      (node (ref "U70") (pin "1") (pinfunction "B(2)_1") (pintype "input"))
    )
    (net (code "151") (name "Net-(U71-B(2))") (class "Default")
      (node (ref "R159") (pin "2") (pinfunction "2_2") (pintype "passive"))
      (node (ref "U71") (pin "1") (pinfunction "B(2)_1") (pintype "input"))
    )
    (net (code "152") (name "Net-(U72-B(2))") (class "Default")
      (node (ref "R160") (pin "2") (pinfunction "2_2") (pintype "passive"))
      (node (ref "U72") (pin "1") (pinfunction "B(2)_1") (pintype "input"))
    )
    (net (code "153") (name "Net-(U73-B(2))") (class "Default")
      (node (ref "R164") (pin "2") (pinfunction "2_2") (pintype "passive"))
      (node (ref "U73") (pin "1") (pinfunction "B(2)_1") (pintype "input"))
    )
    (net (code "154") (name "Net-(U74-B(2))") (class "Default")
      (node (ref "R165") (pin "2") (pinfunction "2_2") (pintype "passive"))
      (node (ref "U74") (pin "1") (pinfunction "B(2)_1") (pintype "input"))
    )
    (net (code "155") (name "Net-(U75-B(2))") (class "Default")
      (node (ref "R166") (pin "2") (pinfunction "2_2") (pintype "passive"))
      (node (ref "U75") (pin "1") (pinfunction "B(2)_1") (pintype "input"))
    )
    (net (code "156") (name "P0_00") (class "Default")
      (node (ref "J4") (pin "P$2") (pinfunction "P$2_P$2") (pintype "bidirectional"))
      (node (ref "U3") (pin "169") (pinfunction "P0_0/AN0\\00_169") (pintype "bidirectional"))
    )
    (net (code "157") (name "P0_01") (class "Default")
      (node (ref "J4") (pin "P$1") (pinfunction "P$1_P$1") (pintype "bidirectional"))
      (node (ref "U3") (pin "168") (pinfunction "P0_1/AN001_168") (pintype "bidirectional"))
    )
    (net (code "158") (name "P0_02") (class "Default")
      (node (ref "J39") (pin "P$20") (pinfunction "P$20_P$20") (pintype "bidirectional"))
      (node (ref "R25") (pin "P$1") (pinfunction "1_P$1") (pintype "passive"))
      (node (ref "U3") (pin "167") (pinfunction "P0_2/AN002_167") (pintype "bidirectional"))
    )
    (net (code "159") (name "P0_03") (class "Default")
      (node (ref "J39") (pin "P$18") (pinfunction "P$18_P$18") (pintype "bidirectional"))
      (node (ref "R26") (pin "P$1") (pinfunction "1_P$1") (pintype "passive"))
      (node (ref "U3") (pin "166") (pinfunction "P0_3/PGAVSS000_166") (pintype "bidirectional"))
    )
    (net (code "160") (name "P0_04") (class "Default")
      (node (ref "J39") (pin "P$16") (pinfunction "P$16_P$16") (pintype "bidirectional"))
      (node (ref "R27") (pin "P$1") (pinfunction "1_P$1") (pintype "passive"))
      (node (ref "U3") (pin "165") (pinfunction "P0_4/AN100_165") (pintype "bidirectional"))
    )
    (net (code "161") (name "P0_05") (class "Default")
      (node (ref "J39") (pin "P$14") (pinfunction "P$14_P$14") (pintype "bidirectional"))
      (node (ref "R102") (pin "P$1") (pinfunction "1_P$1") (pintype "passive"))
      (node (ref "U3") (pin "164") (pinfunction "P0_5/AN101_164") (pintype "bidirectional"))
    )
    (net (code "162") (name "P0_06") (class "Default")
      (node (ref "J39") (pin "P$12") (pinfunction "P$12_P$12") (pintype "bidirectional"))
      (node (ref "R103") (pin "P$1") (pinfunction "1_P$1") (pintype "passive"))
      (node (ref "U3") (pin "163") (pinfunction "P0_6/AN102_163") (pintype "bidirectional"))
    )
    (net (code "163") (name "P0_07") (class "Default")
      (node (ref "J39") (pin "P$10") (pinfunction "P$10_P$10") (pintype "bidirectional"))
      (node (ref "R104") (pin "P$1") (pinfunction "1_P$1") (pintype "passive"))
      (node (ref "U3") (pin "162") (pinfunction "P0_7/PGVSS100_162") (pintype "bidirectional"))
    )
    (net (code "164") (name "P0_08") (class "Default")
      (node (ref "J39") (pin "P$8") (pinfunction "P$8_P$8") (pintype "bidirectional"))
      (node (ref "R105") (pin "P$1") (pinfunction "1_P$1") (pintype "passive"))
      (node (ref "U3") (pin "161") (pinfunction "P0_8/AN003_161") (pintype "bidirectional"))
    )
    (net (code "165") (name "P0_09") (class "Default")
      (node (ref "J39") (pin "P$6") (pinfunction "P$6_P$6") (pintype "bidirectional"))
      (node (ref "R106") (pin "P$1") (pinfunction "1_P$1") (pintype "passive"))
      (node (ref "U3") (pin "160") (pinfunction "P0_9/AN004_160") (pintype "bidirectional"))
    )
    (net (code "166") (name "P0_14") (class "Default")
      (node (ref "J39") (pin "P$4") (pinfunction "P$4_P$4") (pintype "bidirectional"))
      (node (ref "R107") (pin "P$1") (pinfunction "1_P$1") (pintype "passive"))
      (node (ref "U3") (pin "152") (pinfunction "P0_14/DA0/AN005/AN105_152") (pintype "bidirectional"))
    )
    (net (code "167") (name "P0_15") (class "Default")
      (node (ref "J39") (pin "P$2") (pinfunction "P$2_P$2") (pintype "bidirectional"))
      (node (ref "R108") (pin "P$1") (pinfunction "1_P$1") (pintype "passive"))
      (node (ref "U3") (pin "151") (pinfunction "P0_15/DA1/AN006/AN106_151") (pintype "bidirectional"))
    )
    (net (code "168") (name "P1_02") (class "Default")
      (node (ref "J8") (pin "P$10") (pinfunction "P$10_P$10") (pintype "bidirectional"))
      (node (ref "U3") (pin "130") (pinfunction "P1_2_130") (pintype "bidirectional"))
    )
    (net (code "169") (name "P1_03") (class "Default")
      (node (ref "J8") (pin "P$9") (pinfunction "P$9_P$9") (pintype "bidirectional"))
      (node (ref "U3") (pin "129") (pinfunction "P1_3_129") (pintype "bidirectional"))
    )
    (net (code "170") (name "P1_04") (class "Default")
      (node (ref "J8") (pin "P$11") (pinfunction "P$11_P$11") (pintype "bidirectional"))
      (node (ref "U3") (pin "128") (pinfunction "P1_4_128") (pintype "bidirectional"))
    )
    (net (code "171") (name "P1_05") (class "Default")
      (node (ref "J8") (pin "P$13") (pinfunction "P$13_P$13") (pintype "bidirectional"))
      (node (ref "U3") (pin "127") (pinfunction "P1_5_127") (pintype "bidirectional"))
    )
    (net (code "172") (name "P1_06") (class "Default")
      (node (ref "J8") (pin "P$15") (pinfunction "P$15_P$15") (pintype "bidirectional"))
      (node (ref "U3") (pin "126") (pinfunction "P1_6_126") (pintype "bidirectional"))
    )
    (net (code "173") (name "P1_07") (class "Default")
      (node (ref "J8") (pin "P$17") (pinfunction "P$17_P$17") (pintype "bidirectional"))
      (node (ref "U3") (pin "125") (pinfunction "P1_7_125") (pintype "bidirectional"))
    )
    (net (code "174") (name "P4_00") (class "Default")
      (node (ref "J4") (pin "P$7") (pinfunction "P$7_P$7") (pintype "bidirectional"))
      (node (ref "U3") (pin "1") (pinfunction "P4_0_1") (pintype "bidirectional"))
    )
    (net (code "175") (name "P4_01") (class "Default")
      (node (ref "J4") (pin "P$8") (pinfunction "P$8_P$8") (pintype "bidirectional"))
      (node (ref "U3") (pin "2") (pinfunction "P4_1_2") (pintype "bidirectional"))
    )
    (net (code "176") (name "P4_02") (class "Default")
      (node (ref "J4") (pin "P$9") (pinfunction "P$9_P$9") (pintype "bidirectional"))
      (node (ref "U3") (pin "3") (pinfunction "P4_2_3") (pintype "bidirectional"))
    )
    (net (code "177") (name "P4_08") (class "Default")
      (node (ref "J4") (pin "P$20") (pinfunction "P$20_P$20") (pintype "bidirectional"))
      (node (ref "U3") (pin "43") (pinfunction "P4_8_43") (pintype "bidirectional"))
    )
    (net (code "178") (name "P4_09") (class "Default")
      (node (ref "J4") (pin "P$19") (pinfunction "P$19_P$19") (pintype "bidirectional"))
      (node (ref "U3") (pin "42") (pinfunction "P4_9_42") (pintype "bidirectional"))
    )
    (net (code "179") (name "P4_10") (class "Default")
      (node (ref "J4") (pin "P$18") (pinfunction "P$18_P$18") (pintype "bidirectional"))
      (node (ref "U3") (pin "41") (pinfunction "P4_10_41") (pintype "bidirectional"))
    )
    (net (code "180") (name "P4_11") (class "Default")
      (node (ref "J4") (pin "P$17") (pinfunction "P$17_P$17") (pintype "bidirectional"))
      (node (ref "U3") (pin "40") (pinfunction "P4_11_40") (pintype "bidirectional"))
    )
    (net (code "181") (name "P4_12") (class "Default")
      (node (ref "J4") (pin "P$16") (pinfunction "P$16_P$16") (pintype "bidirectional"))
      (node (ref "U3") (pin "39") (pinfunction "P4_12_39") (pintype "bidirectional"))
    )
    (net (code "182") (name "P4_13") (class "Default")
      (node (ref "J4") (pin "P$15") (pinfunction "P$15_P$15") (pintype "bidirectional"))
      (node (ref "U3") (pin "38") (pinfunction "P4_13_38") (pintype "bidirectional"))
    )
    (net (code "183") (name "P4_14") (class "Default")
      (node (ref "J4") (pin "P$14") (pinfunction "P$14_P$14") (pintype "bidirectional"))
      (node (ref "U3") (pin "37") (pinfunction "P4_14_37") (pintype "bidirectional"))
    )
    (net (code "184") (name "P4_15") (class "Default")
      (node (ref "J4") (pin "P$13") (pinfunction "P$13_P$13") (pintype "bidirectional"))
      (node (ref "U3") (pin "36") (pinfunction "P4_15_36") (pintype "bidirectional"))
    )
    (net (code "185") (name "P5_11") (class "Default")
      (node (ref "J4") (pin "P$6") (pinfunction "P$6_P$6") (pintype "bidirectional"))
      (node (ref "U3") (pin "176") (pinfunction "P5_11_176") (pintype "bidirectional"))
    )
    (net (code "186") (name "P5_12") (class "Default")
      (node (ref "J4") (pin "P$5") (pinfunction "P$5_P$5") (pintype "bidirectional"))
      (node (ref "U3") (pin "175") (pinfunction "P5_12_175") (pintype "bidirectional"))
    )
    (net (code "187") (name "P5_13") (class "Default")
      (node (ref "J4") (pin "P$4") (pinfunction "P$4_P$4") (pintype "bidirectional"))
      (node (ref "U3") (pin "174") (pinfunction "P5_13_174") (pintype "bidirectional"))
    )
    (net (code "188") (name "P6_00") (class "Default")
      (node (ref "J8") (pin "P$19") (pinfunction "P$19_P$19") (pintype "bidirectional"))
      (node (ref "U3") (pin "122") (pinfunction "P6_0_122") (pintype "bidirectional"))
    )
    (net (code "189") (name "P7_06") (class "Default")
      (node (ref "J4") (pin "P$10") (pinfunction "P$10_P$10") (pintype "bidirectional"))
      (node (ref "U3") (pin "14") (pinfunction "P7_6_14") (pintype "bidirectional"))
    )
    (net (code "190") (name "P7_07") (class "Default")
      (node (ref "J4") (pin "P$11") (pinfunction "P$11_P$11") (pintype "bidirectional"))
      (node (ref "U3") (pin "15") (pinfunction "P7_7_15") (pintype "bidirectional"))
    )
    (net (code "191") (name "P8_00") (class "Default")
      (node (ref "J8") (pin "P$5") (pinfunction "P$5_P$5") (pintype "bidirectional"))
      (node (ref "U3") (pin "133") (pinfunction "P8_0_133") (pintype "bidirectional"))
    )
    (net (code "192") (name "P8_01") (class "Default")
      (node (ref "J8") (pin "P$3") (pinfunction "P$3_P$3") (pintype "bidirectional"))
      (node (ref "U3") (pin "134") (pinfunction "P8_1_134") (pintype "bidirectional"))
    )
    (net (code "193") (name "P8_02") (class "Default")
      (node (ref "J8") (pin "P$4") (pinfunction "P$4_P$4") (pintype "bidirectional"))
      (node (ref "U3") (pin "135") (pinfunction "P8_2_135") (pintype "bidirectional"))
    )
    (net (code "194") (name "P8_03") (class "Default")
      (node (ref "J8") (pin "P$1") (pinfunction "P$1_P$1") (pintype "bidirectional"))
      (node (ref "U3") (pin "136") (pinfunction "P8_3_136") (pintype "bidirectional"))
    )
    (net (code "195") (name "P8_04") (class "Default")
      (node (ref "J8") (pin "P$2") (pinfunction "P$2_P$2") (pintype "bidirectional"))
      (node (ref "U3") (pin "137") (pinfunction "P8_4_137") (pintype "bidirectional"))
    )
    (net (code "196") (name "P8_05") (class "Default")
      (node (ref "J4") (pin "P$3") (pinfunction "P$3_P$3") (pintype "bidirectional"))
      (node (ref "U3") (pin "173") (pinfunction "P8_5_173") (pintype "bidirectional"))
    )
    (net (code "197") (name "PB_00") (class "Default")
      (node (ref "J4") (pin "P$12") (pinfunction "P$12_P$12") (pintype "bidirectional"))
      (node (ref "U3") (pin "16") (pinfunction "PB_0_16") (pintype "bidirectional"))
    )
    (net (code "198") (name "R51") (class "Default")
      (node (ref "R7") (pin "P$1") (pinfunction "1_P$1") (pintype "passive"))
      (node (ref "RJ1") (pin "12") (pinfunction "YHI_12") (pintype "bidirectional"))
    )
    (net (code "199") (name "R52") (class "Default")
      (node (ref "R8") (pin "P$1") (pinfunction "1_P$1") (pintype "passive"))
      (node (ref "RJ1") (pin "9") (pinfunction "GHI_9") (pintype "bidirectional"))
    )
    (net (code "200") (name "RELAY_1") (class "Default")
      (node (ref "R29") (pin "P$1") (pinfunction "1_P$1") (pintype "passive"))
      (node (ref "U3") (pin "56") (pinfunction "P3_14_56") (pintype "bidirectional"))
    )
    (net (code "201") (name "RELAY_2") (class "Default")
      (node (ref "R30") (pin "P$1") (pinfunction "1_P$1") (pintype "passive"))
      (node (ref "U3") (pin "55") (pinfunction "P3_13_55") (pintype "bidirectional"))
    )
    (net (code "202") (name "RELAY_3") (class "Default")
      (node (ref "R49") (pin "P$1") (pinfunction "1_P$1") (pintype "passive"))
      (node (ref "U3") (pin "52") (pinfunction "P2_4_52") (pintype "bidirectional"))
    )
    (net (code "203") (name "RELAY_4") (class "Default")
      (node (ref "R50") (pin "P$1") (pinfunction "1_P$1") (pintype "passive"))
      (node (ref "U3") (pin "49") (pinfunction "P2_7_49") (pintype "bidirectional"))
    )
    (net (code "204") (name "RESET") (class "Default")
      (node (ref "C16") (pin "P$1") (pinfunction "1_P$1") (pintype "passive"))
      (node (ref "J3") (pin "9") (pinfunction "9_9") (pintype "passive"))
      (node (ref "R13") (pin "P$1") (pinfunction "1_P$1") (pintype "passive"))
      (node (ref "U3") (pin "67") (pinfunction "RES#_67") (pintype "bidirectional"))
    )
    (net (code "205") (name "REXT") (class "Default")
      (node (ref "C3") (pin "P$1") (pinfunction "1_P$1") (pintype "passive"))
      (node (ref "R1") (pin "P$2") (pinfunction "2_P$2") (pintype "passive"))
      (node (ref "U1") (pin "9") (pinfunction "REXT_9") (pintype "input"))
    )
    (net (code "206") (name "RO_NEG_1") (class "Default")
      (node (ref "J15") (pin "P$2") (pinfunction "P$2_P$2") (pintype "bidirectional"))
      (node (ref "U$1") (pin "P$3") (pinfunction "VO-_P$3") (pintype "bidirectional"))
    )
    (net (code "207") (name "RO_NEG_2") (class "Default")
      (node (ref "J16") (pin "P$2") (pinfunction "P$2_P$2") (pintype "bidirectional"))
      (node (ref "U$2") (pin "P$3") (pinfunction "VO-_P$3") (pintype "bidirectional"))
    )
    (net (code "208") (name "RO_NEG_3") (class "Default")
      (node (ref "J23") (pin "P$2") (pinfunction "P$2_P$2") (pintype "bidirectional"))
      (node (ref "U$7") (pin "P$3") (pinfunction "VO-_P$3") (pintype "bidirectional"))
    )
    (net (code "209") (name "RO_NEG_4") (class "Default")
      (node (ref "J24") (pin "P$2") (pinfunction "P$2_P$2") (pintype "bidirectional"))
      (node (ref "U$8") (pin "P$3") (pinfunction "VO-_P$3") (pintype "bidirectional"))
    )
    (net (code "210") (name "RO_POS_1") (class "Default")
      (node (ref "J15") (pin "P$1") (pinfunction "P$1_P$1") (pintype "bidirectional"))
      (node (ref "U$1") (pin "P$4") (pinfunction "VO+_P$4") (pintype "bidirectional"))
    )
    (net (code "211") (name "RO_POS_2") (class "Default")
      (node (ref "J16") (pin "P$1") (pinfunction "P$1_P$1") (pintype "bidirectional"))
      (node (ref "U$2") (pin "P$4") (pinfunction "VO+_P$4") (pintype "bidirectional"))
    )
    (net (code "212") (name "RO_POS_3") (class "Default")
      (node (ref "J23") (pin "P$1") (pinfunction "P$1_P$1") (pintype "bidirectional"))
      (node (ref "U$7") (pin "P$4") (pinfunction "VO+_P$4") (pintype "bidirectional"))
    )
    (net (code "213") (name "RO_POS_4") (class "Default")
      (node (ref "J24") (pin "P$1") (pinfunction "P$1_P$1") (pintype "bidirectional"))
      (node (ref "U$8") (pin "P$4") (pinfunction "VO+_P$4") (pintype "bidirectional"))
    )
    (net (code "214") (name "RXD0") (class "Default")
      (node (ref "R10") (pin "P$2") (pinfunction "2_P$2") (pintype "passive"))
      (node (ref "U1") (pin "13") (pinfunction "RXD0_13") (pintype "bidirectional"))
    )
    (net (code "215") (name "RXD1") (class "Default")
      (node (ref "R9") (pin "P$2") (pinfunction "2_P$2") (pintype "passive"))
      (node (ref "U1") (pin "12") (pinfunction "RXD1_12") (pintype "bidirectional"))
    )
    (net (code "216") (name "RXER") (class "Default")
      (node (ref "R11") (pin "P$2") (pinfunction "2_P$2") (pintype "passive"))
      (node (ref "U1") (pin "17") (pinfunction "RXER_17") (pintype "bidirectional"))
    )
    (net (code "217") (name "RXM") (class "Default")
      (node (ref "RJ1") (pin "6") (pinfunction "RD-_6") (pintype "bidirectional"))
      (node (ref "U1") (pin "3") (pinfunction "RXM_3") (pintype "bidirectional"))
    )
    (net (code "218") (name "RXP") (class "Default")
      (node (ref "RJ1") (pin "3") (pinfunction "RD+_3") (pintype "bidirectional"))
      (node (ref "U1") (pin "4") (pinfunction "RXP_4") (pintype "bidirectional"))
    )
    (net (code "219") (name "SD1_CD") (class "Default")
      (node (ref "J1") (pin "10") (pinfunction "CD_SWITCH2_10") (pintype "bidirectional"))
      (node (ref "U3") (pin "146") (pinfunction "P5_6/AN019_146") (pintype "bidirectional"))
    )
    (net (code "220") (name "SD1_CLK") (class "Default")
      (node (ref "J1") (pin "5") (pinfunction "CLOCK_5") (pintype "bidirectional"))
      (node (ref "U3") (pin "140") (pinfunction "P5_0/AN016_140") (pintype "bidirectional"))
    )
    (net (code "221") (name "SD1_CMD") (class "Default")
      (node (ref "J1") (pin "3") (pinfunction "COMMAND/RESPONSE_3") (pintype "bidirectional"))
      (node (ref "U3") (pin "141") (pinfunction "P5_1/AN116_141") (pintype "bidirectional"))
    )
    (net (code "222") (name "SD1_DAT0") (class "Default")
      (node (ref "J1") (pin "7") (pinfunction "DATA_LINE[BIT_0]_7") (pintype "bidirectional"))
      (node (ref "U3") (pin "142") (pinfunction "P5_2/AN017_142") (pintype "bidirectional"))
    )
    (net (code "223") (name "SD1_DAT1") (class "Default")
      (node (ref "J1") (pin "8") (pinfunction "DATA_LINE[BIT_1]_8") (pintype "bidirectional"))
      (node (ref "U3") (pin "143") (pinfunction "P5_3/AN117_143") (pintype "bidirectional"))
    )
    (net (code "224") (name "SD1_DAT2") (class "Default")
      (node (ref "J1") (pin "1") (pinfunction "DATA_LINE[BIT_2]_1") (pintype "bidirectional"))
      (node (ref "U3") (pin "144") (pinfunction "P5_4/AN018_144") (pintype "bidirectional"))
    )
    (net (code "225") (name "SD1_DAT3") (class "Default")
      (node (ref "J1") (pin "2") (pinfunction "CARD_DETECT/DATA_LINE[BIT_3]_2") (pintype "bidirectional"))
      (node (ref "U3") (pin "145") (pinfunction "P5_5/AN118_145") (pintype "bidirectional"))
    )
    (net (code "226") (name "SD1_WP") (class "Default")
      (node (ref "J1") (pin "9") (pinfunction "CD_SWITCH1_9") (pintype "bidirectional"))
      (node (ref "U3") (pin "147") (pinfunction "P5_7/AN119_147") (pintype "bidirectional"))
    )
    (net (code "227") (name "TCK") (class "Default")
      (node (ref "J3") (pin "7") (pinfunction "7_7") (pintype "passive"))
      (node (ref "U3") (pin "88") (pinfunction "P3_0_88") (pintype "bidirectional"))
    )
    (net (code "228") (name "TDI") (class "Default")
      (node (ref "J3") (pin "1") (pinfunction "1_1") (pintype "passive"))
      (node (ref "U3") (pin "91") (pinfunction "P1_10_91") (pintype "bidirectional"))
    )
    (net (code "229") (name "TDO") (class "Default")
      (node (ref "J3") (pin "3") (pinfunction "3_3") (pintype "passive"))
      (node (ref "U3") (pin "90") (pinfunction "P1_9_90") (pintype "bidirectional"))
    )
    (net (code "230") (name "TMS") (class "Default")
      (node (ref "J3") (pin "5") (pinfunction "5_5") (pintype "passive"))
      (node (ref "U3") (pin "89") (pinfunction "P1_8_89") (pintype "bidirectional"))
    )
    (net (code "231") (name "TXM") (class "Default")
      (node (ref "RJ1") (pin "2") (pinfunction "TD-_2") (pintype "bidirectional"))
      (node (ref "U1") (pin "5") (pinfunction "TXM_5") (pintype "bidirectional"))
    )
    (net (code "232") (name "TXP") (class "Default")
      (node (ref "RJ1") (pin "1") (pinfunction "TD+_1") (pintype "bidirectional"))
      (node (ref "U1") (pin "6") (pinfunction "TXP_6") (pintype "bidirectional"))
    )
    (net (code "233") (name "USBHS_FAULT") (class "Default")
      (node (ref "R19") (pin "P$1") (pinfunction "1_P$1") (pintype "passive"))
      (node (ref "U2") (pin "3") (pinfunction "FLG_3") (pintype "input"))
      (node (ref "U3") (pin "78") (pinfunction "P3_8_78") (pintype "bidirectional"))
    )
    (net (code "234") (name "USBHS_N") (class "Default")
      (node (ref "J6") (pin "D-") (pinfunction "D-_D-") (pintype "bidirectional"))
      (node (ref "U3") (pin "31") (pinfunction "USBHS_DM_31") (pintype "bidirectional"))
    )
    (net (code "235") (name "USBHS_P") (class "Default")
      (node (ref "J6") (pin "D+") (pinfunction "D+_D+") (pintype "bidirectional"))
      (node (ref "U3") (pin "32") (pinfunction "USBHS_DP_32") (pintype "bidirectional"))
    )
    (net (code "236") (name "USBHS_VBUS") (class "Default")
      (node (ref "C29") (pin "P$1") (pinfunction "1_P$1") (pintype "passive"))
      (node (ref "C31") (pin "1") (pinfunction "1_1") (pintype "passive"))
      (node (ref "J6") (pin "VBUS") (pinfunction "VBUS_VBUS") (pintype "power_in"))
      (node (ref "U2") (pin "5") (pinfunction "OUT_5") (pintype "input"))
      (node (ref "U3") (pin "17") (pinfunction "PB_1_17") (pintype "bidirectional"))
    )
    (net (code "237") (name "USBHS_VBUSEN") (class "Default")
      (node (ref "R20") (pin "P$1") (pinfunction "1_P$1") (pintype "passive"))
      (node (ref "U2") (pin "1") (pinfunction "EN_1") (pintype "input"))
    )
    (net (code "238") (name "USB_N") (class "Default")
      (node (ref "R17") (pin "P$1") (pinfunction "1_P$1") (pintype "passive"))
      (node (ref "U3") (pin "46") (pinfunction "USB_DM_46") (pintype "bidirectional"))
    )
    (net (code "239") (name "USB_P") (class "Default")
      (node (ref "R18") (pin "P$1") (pinfunction "1_P$1") (pintype "passive"))
      (node (ref "U3") (pin "47") (pinfunction "USB_DP_47") (pintype "bidirectional"))
    )
    (net (code "240") (name "USB_VBUS_B") (class "Default")
      (node (ref "R16") (pin "P$1") (pinfunction "1_P$1") (pintype "passive"))
      (node (ref "U3") (pin "44") (pinfunction "P4_7_44") (pintype "bidirectional"))
    )
    (net (code "241") (name "VCL_F(FLASH)") (class "Default")
      (node (ref "C34") (pin "P$2") (pinfunction "2_P$2") (pintype "passive"))
      (node (ref "U3") (pin "112") (pinfunction "VCL_F(FLASH)_112") (pintype "bidirectional"))
    )
    (net (code "242") (name "VDD") (class "Default")
      (node (ref "C14") (pin "P$1") (pinfunction "1_P$1") (pintype "passive"))
      (node (ref "C15") (pin "P$1") (pinfunction "1_P$1") (pintype "passive"))
      (node (ref "C19") (pin "P$2") (pinfunction "2_P$2") (pintype "passive"))
      (node (ref "C20") (pin "P$2") (pinfunction "2_P$2") (pintype "passive"))
      (node (ref "C21") (pin "P$2") (pinfunction "2_P$2") (pintype "passive"))
      (node (ref "C22") (pin "P$2") (pinfunction "2_P$2") (pintype "passive"))
      (node (ref "C25") (pin "P$2") (pinfunction "2_P$2") (pintype "passive"))
      (node (ref "C27") (pin "P$2") (pinfunction "2_P$2") (pintype "passive"))
      (node (ref "C30") (pin "P$2") (pinfunction "2_P$2") (pintype "passive"))
      (node (ref "C35") (pin "P$2") (pinfunction "2_P$2") (pintype "passive"))
      (node (ref "C36") (pin "P$1") (pinfunction "1_P$1") (pintype "passive"))
      (node (ref "C38") (pin "P$2") (pinfunction "2_P$2") (pintype "passive"))
      (node (ref "C39") (pin "P$1") (pinfunction "1_P$1") (pintype "passive"))
      (node (ref "C4") (pin "P$1") (pinfunction "1_P$1") (pintype "passive"))
      (node (ref "C40") (pin "P$1") (pinfunction "1_P$1") (pintype "passive"))
      (node (ref "C41") (pin "P$1") (pinfunction "1_P$1") (pintype "passive"))
      (node (ref "C43") (pin "P$2") (pinfunction "2_P$2") (pintype "passive"))
      (node (ref "C5") (pin "P$1") (pinfunction "1_P$1") (pintype "passive"))
      (node (ref "C7") (pin "P$1") (pinfunction "1_P$1") (pintype "passive"))
      (node (ref "FB1") (pin "1") (pinfunction "P$1_1") (pintype "bidirectional"))
      (node (ref "J1") (pin "4") (pinfunction "SUPPLY_VOLTAGE_4") (pintype "power_in"))
      (node (ref "J3") (pin "2") (pinfunction "2_2") (pintype "passive"))
      (node (ref "J3") (pin "4") (pinfunction "4_4") (pintype "passive"))
      (node (ref "L1") (pin "2") (pinfunction "P$2_2") (pintype "bidirectional"))
      (node (ref "R102") (pin "P$2") (pinfunction "2_P$2") (pintype "passive"))
      (node (ref "R103") (pin "P$2") (pinfunction "2_P$2") (pintype "passive"))
      (node (ref "R104") (pin "P$2") (pinfunction "2_P$2") (pintype "passive"))
      (node (ref "R105") (pin "P$2") (pinfunction "2_P$2") (pintype "passive"))
      (node (ref "R106") (pin "P$2") (pinfunction "2_P$2") (pintype "passive"))
      (node (ref "R107") (pin "P$2") (pinfunction "2_P$2") (pintype "passive"))
      (node (ref "R108") (pin "P$2") (pinfunction "2_P$2") (pintype "passive"))
      (node (ref "R13") (pin "P$2") (pinfunction "2_P$2") (pintype "passive"))
      (node (ref "R14") (pin "P$1") (pinfunction "1_P$1") (pintype "passive"))
      (node (ref "R15") (pin "P$1") (pinfunction "1_P$1") (pintype "passive"))
      (node (ref "R2") (pin "P$2") (pinfunction "2_P$2") (pintype "passive"))
      (node (ref "R25") (pin "P$2") (pinfunction "2_P$2") (pintype "passive"))
      (node (ref "R26") (pin "P$2") (pinfunction "2_P$2") (pintype "passive"))
      (node (ref "R27") (pin "P$2") (pinfunction "2_P$2") (pintype "passive"))
      (node (ref "R3") (pin "P$2") (pinfunction "2_P$2") (pintype "passive"))
      (node (ref "R4") (pin "P$2") (pinfunction "2_P$2") (pintype "passive"))
      (node (ref "R5") (pin "P$2") (pinfunction "2_P$2") (pintype "passive"))
      (node (ref "R6") (pin "P$2") (pinfunction "2_P$2") (pintype "passive"))
      (node (ref "R7") (pin "P$2") (pinfunction "2_P$2") (pintype "passive"))
      (node (ref "R8") (pin "P$2") (pinfunction "2_P$2") (pintype "passive"))
      (node (ref "U1") (pin "14") (pinfunction "VDDIO_14") (pintype "power_in"))
      (node (ref "U3") (pin "110") (pinfunction "VCC(IO)5_110") (pintype "bidirectional"))
      (node (ref "U3") (pin "123") (pinfunction "VCC(IO)6_123") (pintype "bidirectional"))
      (node (ref "U3") (pin "138") (pinfunction "VCC(IO)7_138") (pintype "bidirectional"))
      (node (ref "U3") (pin "149") (pinfunction "VCC(IO)8_149") (pintype "bidirectional"))
      (node (ref "U3") (pin "154") (pinfunction "VREFH_154") (pintype "bidirectional"))
      (node (ref "U3") (pin "155") (pinfunction "AVCC0_155") (pintype "bidirectional"))
      (node (ref "U3") (pin "158") (pinfunction "VREFH0_158") (pintype "bidirectional"))
      (node (ref "U3") (pin "171") (pinfunction "VCC(IO)9_171") (pintype "bidirectional"))
      (node (ref "U3") (pin "25") (pinfunction "VCC1_25") (pintype "bidirectional"))
      (node (ref "U3") (pin "26") (pinfunction "AVCC_SUBHS_26") (pintype "bidirectional"))
      (node (ref "U3") (pin "34") (pinfunction "VCC_USBHS_34") (pintype "bidirectional"))
      (node (ref "U3") (pin "48") (pinfunction "VCC_USB_48") (pintype "bidirectional"))
      (node (ref "U3") (pin "61") (pinfunction "VCC(IO)2_61") (pintype "bidirectional"))
      (node (ref "U3") (pin "84") (pinfunction "VCC(IO)3_84") (pintype "bidirectional"))
      (node (ref "U3") (pin "97") (pinfunction "VCC(IO)4_97") (pintype "bidirectional"))
    )
    (net (code "243") (name "VDD5") (class "Default")
      (node (ref "C23") (pin "P$1") (pinfunction "1_P$1") (pintype "passive"))
      (node (ref "C26") (pin "P$1") (pinfunction "1_P$1") (pintype "passive"))
      (node (ref "J2") (pin "P$3") (pinfunction "P$3_P$3") (pintype "bidirectional"))
      (node (ref "R19") (pin "P$2") (pinfunction "2_P$2") (pintype "passive"))
      (node (ref "R20") (pin "P$2") (pinfunction "2_P$2") (pintype "passive"))
      (node (ref "R31") (pin "P$2") (pinfunction "2_P$2") (pintype "passive"))
      (node (ref "R32") (pin "P$2") (pinfunction "2_P$2") (pintype "passive"))
      (node (ref "R51") (pin "P$2") (pinfunction "2_P$2") (pintype "passive"))
      (node (ref "R52") (pin "P$2") (pinfunction "2_P$2") (pintype "passive"))
      (node (ref "U$1") (pin "P$2") (pinfunction "VC+_P$2") (pintype "bidirectional"))
      (node (ref "U$2") (pin "P$2") (pinfunction "VC+_P$2") (pintype "bidirectional"))
      (node (ref "U$7") (pin "P$2") (pinfunction "VC+_P$2") (pintype "bidirectional"))
      (node (ref "U$8") (pin "P$2") (pinfunction "VC+_P$2") (pintype "bidirectional"))
      (node (ref "U18") (pin "3") (pinfunction "C(3)_3") (pintype "input"))
      (node (ref "U19") (pin "3") (pinfunction "C(3)_3") (pintype "input"))
      (node (ref "U2") (pin "4") (pinfunction "VIN_4") (pintype "input"))
      (node (ref "U20") (pin "3") (pinfunction "C(3)_3") (pintype "input"))
      (node (ref "U21") (pin "3") (pinfunction "C(3)_3") (pintype "input"))
      (node (ref "U28") (pin "3") (pinfunction "C(3)_3") (pintype "input"))
      (node (ref "U29") (pin "3") (pinfunction "C(3)_3") (pintype "input"))
      (node (ref "U30") (pin "3") (pinfunction "C(3)_3") (pintype "input"))
      (node (ref "U5") (pin "3") (pinfunction "C(3)_3") (pintype "input"))
      (node (ref "U8") (pin "3") (pinfunction "C(3)_3") (pintype "input"))
      (node (ref "U9") (pin "3") (pinfunction "C(3)_3") (pintype "input"))
    )
    (net (code "244") (name "VDD12") (class "Default")
      (node (ref "J10") (pin "P$1") (pinfunction "P$1_P$1") (pintype "bidirectional"))
      (node (ref "J10") (pin "P$2") (pinfunction "P$2_P$2") (pintype "bidirectional"))
      (node (ref "J11") (pin "P$2") (pinfunction "P$2_P$2") (pintype "bidirectional"))
      (node (ref "J12") (pin "P$2") (pinfunction "P$2_P$2") (pintype "bidirectional"))
      (node (ref "J13") (pin "1") (pinfunction "1-HLFB+_1") (pintype "passive"))
      (node (ref "J13") (pin "2") (pinfunction "2-INPUT_B+_2") (pintype "passive"))
      (node (ref "J13") (pin "3") (pinfunction "3-INPUT_A+_3") (pintype "passive"))
      (node (ref "J13") (pin "4") (pinfunction "4-ENABLE+_4") (pintype "passive"))
      (node (ref "J14") (pin "1") (pinfunction "1-HLFB+_1") (pintype "passive"))
      (node (ref "J14") (pin "2") (pinfunction "2-INPUT_B+_2") (pintype "passive"))
      (node (ref "J14") (pin "3") (pinfunction "3-INPUT_A+_3") (pintype "passive"))
      (node (ref "J14") (pin "4") (pinfunction "4-ENABLE+_4") (pintype "passive"))
      (node (ref "J17") (pin "1") (pinfunction "1-HLFB+_1") (pintype "passive"))
      (node (ref "J17") (pin "2") (pinfunction "2-INPUT_B+_2") (pintype "passive"))
      (node (ref "J17") (pin "3") (pinfunction "3-INPUT_A+_3") (pintype "passive"))
      (node (ref "J17") (pin "4") (pinfunction "4-ENABLE+_4") (pintype "passive"))
      (node (ref "J18") (pin "1") (pinfunction "1-HLFB+_1") (pintype "passive"))
      (node (ref "J18") (pin "2") (pinfunction "2-INPUT_B+_2") (pintype "passive"))
      (node (ref "J18") (pin "3") (pinfunction "3-INPUT_A+_3") (pintype "passive"))
      (node (ref "J18") (pin "4") (pinfunction "4-ENABLE+_4") (pintype "passive"))
      (node (ref "J19") (pin "P$2") (pinfunction "P$2_P$2") (pintype "bidirectional"))
      (node (ref "J20") (pin "P$2") (pinfunction "P$2_P$2") (pintype "bidirectional"))
      (node (ref "J21") (pin "1") (pinfunction "1-HLFB+_1") (pintype "passive"))
      (node (ref "J21") (pin "2") (pinfunction "2-INPUT_B+_2") (pintype "passive"))
      (node (ref "J21") (pin "3") (pinfunction "3-INPUT_A+_3") (pintype "passive"))
      (node (ref "J21") (pin "4") (pinfunction "4-ENABLE+_4") (pintype "passive"))
      (node (ref "J22") (pin "1") (pinfunction "1-HLFB+_1") (pintype "passive"))
      (node (ref "J22") (pin "2") (pinfunction "2-INPUT_B+_2") (pintype "passive"))
      (node (ref "J22") (pin "3") (pinfunction "3-INPUT_A+_3") (pintype "passive"))
      (node (ref "J22") (pin "4") (pinfunction "4-ENABLE+_4") (pintype "passive"))
      (node (ref "J25") (pin "1") (pinfunction "1-HLFB+_1") (pintype "passive"))
      (node (ref "J25") (pin "2") (pinfunction "2-INPUT_B+_2") (pintype "passive"))
      (node (ref "J25") (pin "3") (pinfunction "3-INPUT_A+_3") (pintype "passive"))
      (node (ref "J25") (pin "4") (pinfunction "4-ENABLE+_4") (pintype "passive"))
      (node (ref "J26") (pin "1") (pinfunction "1-HLFB+_1") (pintype "passive"))
      (node (ref "J26") (pin "2") (pinfunction "2-INPUT_B+_2") (pintype "passive"))
      (node (ref "J26") (pin "3") (pinfunction "3-INPUT_A+_3") (pintype "passive"))
      (node (ref "J26") (pin "4") (pinfunction "4-ENABLE+_4") (pintype "passive"))
      (node (ref "J27") (pin "P$2") (pinfunction "P$2_P$2") (pintype "bidirectional"))
      (node (ref "J28") (pin "P$2") (pinfunction "P$2_P$2") (pintype "bidirectional"))
      (node (ref "J29") (pin "1") (pinfunction "1-HLFB+_1") (pintype "passive"))
      (node (ref "J29") (pin "2") (pinfunction "2-INPUT_B+_2") (pintype "passive"))
      (node (ref "J29") (pin "3") (pinfunction "3-INPUT_A+_3") (pintype "passive"))
      (node (ref "J29") (pin "4") (pinfunction "4-ENABLE+_4") (pintype "passive"))
      (node (ref "J30") (pin "1") (pinfunction "1-HLFB+_1") (pintype "passive"))
      (node (ref "J30") (pin "2") (pinfunction "2-INPUT_B+_2") (pintype "passive"))
      (node (ref "J30") (pin "3") (pinfunction "3-INPUT_A+_3") (pintype "passive"))
      (node (ref "J30") (pin "4") (pinfunction "4-ENABLE+_4") (pintype "passive"))
      (node (ref "J31") (pin "P$2") (pinfunction "P$2_P$2") (pintype "bidirectional"))
      (node (ref "J33") (pin "1") (pinfunction "1-HLFB+_1") (pintype "passive"))
      (node (ref "J33") (pin "2") (pinfunction "2-INPUT_B+_2") (pintype "passive"))
      (node (ref "J33") (pin "3") (pinfunction "3-INPUT_A+_3") (pintype "passive"))
      (node (ref "J33") (pin "4") (pinfunction "4-ENABLE+_4") (pintype "passive"))
      (node (ref "J34") (pin "1") (pinfunction "1-HLFB+_1") (pintype "passive"))
      (node (ref "J34") (pin "2") (pinfunction "2-INPUT_B+_2") (pintype "passive"))
      (node (ref "J34") (pin "3") (pinfunction "3-INPUT_A+_3") (pintype "passive"))
      (node (ref "J34") (pin "4") (pinfunction "4-ENABLE+_4") (pintype "passive"))
      (node (ref "J9") (pin "P$2") (pinfunction "P$2_P$2") (pintype "bidirectional"))
      (node (ref "P2") (pin "P$1") (pinfunction "P$1_P$1") (pintype "bidirectional"))
      (node (ref "P4") (pin "P$1") (pinfunction "P$1_P$1") (pintype "bidirectional"))
      (node (ref "R109") (pin "2") (pinfunction "2_2") (pintype "passive"))
      (node (ref "R113") (pin "2") (pinfunction "2_2") (pintype "passive"))
      (node (ref "R114") (pin "2") (pinfunction "2_2") (pintype "passive"))
      (node (ref "R115") (pin "2") (pinfunction "2_2") (pintype "passive"))
      (node (ref "R119") (pin "2") (pinfunction "2_2") (pintype "passive"))
      (node (ref "R120") (pin "2") (pinfunction "2_2") (pintype "passive"))
      (node (ref "R133") (pin "2") (pinfunction "2_2") (pintype "passive"))
      (node (ref "R137") (pin "2") (pinfunction "2_2") (pintype "passive"))
      (node (ref "R138") (pin "2") (pinfunction "2_2") (pintype "passive"))
      (node (ref "R139") (pin "2") (pinfunction "2_2") (pintype "passive"))
      (node (ref "R143") (pin "2") (pinfunction "2_2") (pintype "passive"))
      (node (ref "R144") (pin "2") (pinfunction "2_2") (pintype "passive"))
      (node (ref "R157") (pin "2") (pinfunction "2_2") (pintype "passive"))
      (node (ref "R161") (pin "2") (pinfunction "2_2") (pintype "passive"))
      (node (ref "R162") (pin "2") (pinfunction "2_2") (pintype "passive"))
      (node (ref "R163") (pin "2") (pinfunction "2_2") (pintype "passive"))
      (node (ref "R167") (pin "2") (pinfunction "2_2") (pintype "passive"))
      (node (ref "R168") (pin "2") (pinfunction "2_2") (pintype "passive"))
      (node (ref "R37") (pin "2") (pinfunction "2_2") (pintype "passive"))
      (node (ref "R41") (pin "2") (pinfunction "2_2") (pintype "passive"))
      (node (ref "R42") (pin "2") (pinfunction "2_2") (pintype "passive"))
      (node (ref "R43") (pin "2") (pinfunction "2_2") (pintype "passive"))
      (node (ref "R47") (pin "2") (pinfunction "2_2") (pintype "passive"))
      (node (ref "R48") (pin "2") (pinfunction "2_2") (pintype "passive"))
      (node (ref "R61") (pin "2") (pinfunction "2_2") (pintype "passive"))
      (node (ref "R65") (pin "2") (pinfunction "2_2") (pintype "passive"))
      (node (ref "R66") (pin "2") (pinfunction "2_2") (pintype "passive"))
      (node (ref "R67") (pin "2") (pinfunction "2_2") (pintype "passive"))
      (node (ref "R71") (pin "2") (pinfunction "2_2") (pintype "passive"))
      (node (ref "R72") (pin "2") (pinfunction "2_2") (pintype "passive"))
      (node (ref "R85") (pin "2") (pinfunction "2_2") (pintype "passive"))
      (node (ref "R89") (pin "2") (pinfunction "2_2") (pintype "passive"))
      (node (ref "R90") (pin "2") (pinfunction "2_2") (pintype "passive"))
      (node (ref "R91") (pin "2") (pinfunction "2_2") (pintype "passive"))
      (node (ref "R95") (pin "2") (pinfunction "2_2") (pintype "passive"))
      (node (ref "R96") (pin "2") (pinfunction "2_2") (pintype "passive"))
    )
    (net (code "245") (name "VDDIN") (class "Default")
      (node (ref "J2") (pin "P$2") (pinfunction "P$2_P$2") (pintype "bidirectional"))
      (node (ref "L1") (pin "1") (pinfunction "P$1_1") (pintype "bidirectional"))
    )
    (net (code "246") (name "VDD_1.2") (class "Default")
      (node (ref "C10") (pin "P$1") (pinfunction "1_P$1") (pintype "passive"))
      (node (ref "C11") (pin "P$1") (pinfunction "1_P$1") (pintype "passive"))
      (node (ref "U1") (pin "1") (pinfunction "VDD_1.2_1") (pintype "power_in"))
    )
    (net (code "247") (name "WF_A_DIR") (class "Default")
      (node (ref "R159") (pin "1") (pinfunction "1_1") (pintype "passive"))
      (node (ref "U3") (pin "99") (pinfunction "P6_8_99") (pintype "bidirectional"))
    )
    (net (code "248") (name "WF_A_ENABLE") (class "Default")
      (node (ref "R160") (pin "1") (pinfunction "1_1") (pintype "passive"))
      (node (ref "U3") (pin "96") (pinfunction "P1_15_96") (pintype "bidirectional"))
    )
    (net (code "249") (name "WF_A_HLFB_OUT") (class "Default")
      (node (ref "J33") (pin "5") (pinfunction "5-HLFB-_5") (pintype "passive"))
    )
    (net (code "250") (name "WF_A_MI_DIR") (class "Default")
      (node (ref "J33") (pin "7") (pinfunction "7-INPUT_A-_7") (pintype "passive"))
      (node (ref "R161") (pin "1") (pinfunction "1_1") (pintype "passive"))
      (node (ref "U71") (pin "3") (pinfunction "C(3)_3") (pintype "input"))
    )
    (net (code "251") (name "WF_A_MI_ENABLE") (class "Default")
      (node (ref "J33") (pin "8") (pinfunction "8-ENABLE-_8") (pintype "passive"))
      (node (ref "R162") (pin "1") (pinfunction "1_1") (pintype "passive"))
      (node (ref "U72") (pin "3") (pinfunction "C(3)_3") (pintype "input"))
    )
    (net (code "252") (name "WF_A_MI_STEP") (class "Default")
      (node (ref "J33") (pin "6") (pinfunction "6-INPUT_B-_6") (pintype "passive"))
      (node (ref "R157") (pin "1") (pinfunction "1_1") (pintype "passive"))
      (node (ref "U70") (pin "3") (pinfunction "C(3)_3") (pintype "input"))
    )
    (net (code "253") (name "WF_A_STEP") (class "Default")
      (node (ref "R158") (pin "1") (pinfunction "1_1") (pintype "passive"))
      (node (ref "U3") (pin "100") (pinfunction "P6_9_100") (pintype "bidirectional"))
    )
    (net (code "254") (name "WF_B_DIR") (class "Default")
      (node (ref "R165") (pin "1") (pinfunction "1_1") (pintype "passive"))
      (node (ref "U3") (pin "94") (pinfunction "P1_13_94") (pintype "bidirectional"))
    )
    (net (code "255") (name "WF_B_ENABLE") (class "Default")
      (node (ref "R166") (pin "1") (pinfunction "1_1") (pintype "passive"))
      (node (ref "U3") (pin "93") (pinfunction "P1_12_93") (pintype "bidirectional"))
    )
    (net (code "256") (name "WF_B_HLFB_OUT") (class "Default")
      (node (ref "J34") (pin "5") (pinfunction "5-HLFB-_5") (pintype "passive"))
    )
    (net (code "257") (name "WF_B_MI_ENABLE") (class "Default")
      (node (ref "J34") (pin "8") (pinfunction "8-ENABLE-_8") (pintype "passive"))
      (node (ref "R168") (pin "1") (pinfunction "1_1") (pintype "passive"))
      (node (ref "U75") (pin "3") (pinfunction "C(3)_3") (pintype "input"))
    )
    (net (code "258") (name "WF_B_MI_STEP") (class "Default")
      (node (ref "J34") (pin "6") (pinfunction "6-INPUT_B-_6") (pintype "passive"))
      (node (ref "R163") (pin "1") (pinfunction "1_1") (pintype "passive"))
      (node (ref "U73") (pin "3") (pinfunction "C(3)_3") (pintype "input"))
    )
    (net (code "259") (name "WF_B_STEP") (class "Default")
      (node (ref "R164") (pin "1") (pinfunction "1_1") (pintype "passive"))
      (node (ref "U3") (pin "95") (pinfunction "P1_14_95") (pintype "bidirectional"))
    )
    (net (code "260") (name "XCIN") (class "Default")
      (node (ref "C32") (pin "P$1") (pinfunction "1_P$1") (pintype "passive"))
      (node (ref "U3") (pin "20") (pinfunction "XCIN_20") (pintype "bidirectional"))
      (node (ref "X3") (pin "P$1") (pinfunction "P$1_P$1") (pintype "bidirectional"))
    )
    (net (code "261") (name "XCOUT") (class "Default")
      (node (ref "C37") (pin "P$1") (pinfunction "1_P$1") (pintype "passive"))
      (node (ref "U3") (pin "21") (pinfunction "XCOUT_21") (pintype "bidirectional"))
      (node (ref "X3") (pin "P$2") (pinfunction "P$2_P$2") (pintype "bidirectional"))
    )
    (net (code "262") (name "XII") (class "Default")
      (node (ref "C1") (pin "P$1") (pinfunction "1_P$1") (pintype "passive"))
      (node (ref "U1") (pin "8") (pinfunction "XI_8") (pintype "input"))
      (node (ref "X1") (pin "1") (pinfunction "1_1") (pintype "bidirectional"))
    )
    (net (code "263") (name "XOO") (class "Default")
      (node (ref "C2") (pin "P$1") (pinfunction "1_P$1") (pintype "passive"))
      (node (ref "U1") (pin "7") (pinfunction "XO_7") (pintype "output"))
      (node (ref "X1") (pin "3") (pinfunction "3_3") (pintype "bidirectional"))
    )
    (net (code "264") (name "XTAL1") (class "Default")
      (node (ref "C17") (pin "P$1") (pinfunction "1_P$1") (pintype "passive"))
      (node (ref "U3") (pin "23") (pinfunction "P2_13/XTAL_23") (pintype "bidirectional"))
      (node (ref "X2") (pin "1") (pinfunction "1_1") (pintype "bidirectional"))
    )
    (net (code "265") (name "XTAL2") (class "Default")
      (node (ref "C18") (pin "P$1") (pinfunction "1_P$1") (pintype "passive"))
      (node (ref "U3") (pin "24") (pinfunction "P2_12/EXTAL_24") (pintype "bidirectional"))
      (node (ref "X2") (pin "3") (pinfunction "3_3") (pintype "bidirectional"))
    )
    (net (code "266") (name "X_A_DIR") (class "Default")
      (node (ref "R39") (pin "1") (pinfunction "1_1") (pintype "passive"))
      (node (ref "U3") (pin "117") (pinfunction "P6_5_117") (pintype "bidirectional"))
    )
    (net (code "267") (name "X_A_ENABLE") (class "Default")
      (node (ref "R40") (pin "1") (pinfunction "1_1") (pintype "passive"))
      (node (ref "U3") (pin "116") (pinfunction "P6_6_116") (pintype "bidirectional"))
    )
    (net (code "268") (name "X_A_HLFB_OUT") (class "Default")
      (node (ref "J13") (pin "5") (pinfunction "5-HLFB-_5") (pintype "passive"))
    )
    (net (code "269") (name "X_A_MI_DIR") (class "Default")
      (node (ref "J13") (pin "7") (pinfunction "7-INPUT_A-_7") (pintype "passive"))
      (node (ref "R41") (pin "1") (pinfunction "1_1") (pintype "passive"))
      (node (ref "U11") (pin "3") (pinfunction "C(3)_3") (pintype "input"))
    )
    (net (code "270") (name "X_A_MI_ENABLE") (class "Default")
      (node (ref "J13") (pin "8") (pinfunction "8-ENABLE-_8") (pintype "passive"))
      (node (ref "R42") (pin "1") (pinfunction "1_1") (pintype "passive"))
      (node (ref "U12") (pin "3") (pinfunction "C(3)_3") (pintype "input"))
    )
    (net (code "271") (name "X_A_MI_STEP") (class "Default")
      (node (ref "J13") (pin "6") (pinfunction "6-INPUT_B-_6") (pintype "passive"))
      (node (ref "R37") (pin "1") (pinfunction "1_1") (pintype "passive"))
      (node (ref "U10") (pin "3") (pinfunction "C(3)_3") (pintype "input"))
    )
    (net (code "272") (name "X_A_STEP") (class "Default")
      (node (ref "R38") (pin "1") (pinfunction "1_1") (pintype "passive"))
      (node (ref "U3") (pin "118") (pinfunction "P6_4_118") (pintype "bidirectional"))
    )
    (net (code "273") (name "X_B_DIR") (class "Default")
      (node (ref "R45") (pin "1") (pinfunction "1_1") (pintype "passive"))
      (node (ref "U3") (pin "120") (pinfunction "P6_2_120") (pintype "bidirectional"))
    )
    (net (code "274") (name "X_B_ENABLE") (class "Default")
      (node (ref "R46") (pin "1") (pinfunction "1_1") (pintype "passive"))
      (node (ref "U3") (pin "119") (pinfunction "P6_3_119") (pintype "bidirectional"))
    )
    (net (code "275") (name "X_B_HLFB_OUT") (class "Default")
      (node (ref "J14") (pin "5") (pinfunction "5-HLFB-_5") (pintype "passive"))
    )
    (net (code "276") (name "X_B_MI_DIR") (class "Default")
      (node (ref "J14") (pin "7") (pinfunction "7-INPUT_A-_7") (pintype "passive"))
      (node (ref "R47") (pin "1") (pinfunction "1_1") (pintype "passive"))
      (node (ref "U14") (pin "3") (pinfunction "C(3)_3") (pintype "input"))
    )
    (net (code "277") (name "X_B_MI_ENABLE") (class "Default")
      (node (ref "J14") (pin "8") (pinfunction "8-ENABLE-_8") (pintype "passive"))
      (node (ref "R48") (pin "1") (pinfunction "1_1") (pintype "passive"))
      (node (ref "U15") (pin "3") (pinfunction "C(3)_3") (pintype "input"))
    )
    (net (code "278") (name "X_B_MI_STEP") (class "Default")
      (node (ref "J14") (pin "6") (pinfunction "6-INPUT_B-_6") (pintype "passive"))
      (node (ref "R43") (pin "1") (pinfunction "1_1") (pintype "passive"))
      (node (ref "U13") (pin "3") (pinfunction "C(3)_3") (pintype "input"))
    )
    (net (code "279") (name "X_B_STEP") (class "Default")
      (node (ref "R44") (pin "1") (pinfunction "1_1") (pintype "passive"))
      (node (ref "U3") (pin "121") (pinfunction "P6_1_121") (pintype "bidirectional"))
    )
    (net (code "280") (name "Y_A_DIR") (class "Default")
      (node (ref "R63") (pin "1") (pinfunction "1_1") (pintype "passive"))
      (node (ref "U3") (pin "114") (pinfunction "PA_0_114") (pintype "bidirectional"))
    )
    (net (code "281") (name "Y_A_ENABLE") (class "Default")
      (node (ref "R64") (pin "1") (pinfunction "1_1") (pintype "passive"))
      (node (ref "U3") (pin "113") (pinfunction "PA_1_113") (pintype "bidirectional"))
    )
    (net (code "282") (name "Y_A_HLFB_OUT") (class "Default")
      (node (ref "J17") (pin "5") (pinfunction "5-HLFB-_5") (pintype "passive"))
    )
    (net (code "283") (name "Y_A_MI_DIR") (class "Default")
      (node (ref "J17") (pin "7") (pinfunction "7-INPUT_A-_7") (pintype "passive"))
      (node (ref "R65") (pin "1") (pinfunction "1_1") (pintype "passive"))
      (node (ref "U23") (pin "3") (pinfunction "C(3)_3") (pintype "input"))
    )
    (net (code "284") (name "Y_A_MI_ENABLE") (class "Default")
      (node (ref "J17") (pin "8") (pinfunction "8-ENABLE-_8") (pintype "passive"))
      (node (ref "R66") (pin "1") (pinfunction "1_1") (pintype "passive"))
      (node (ref "U24") (pin "3") (pinfunction "C(3)_3") (pintype "input"))
    )
    (net (code "285") (name "Y_A_MI_STEP") (class "Default")
      (node (ref "J17") (pin "6") (pinfunction "6-INPUT_B-_6") (pintype "passive"))
      (node (ref "R61") (pin "1") (pinfunction "1_1") (pintype "passive"))
      (node (ref "U22") (pin "3") (pinfunction "C(3)_3") (pintype "input"))
    )
    (net (code "286") (name "Y_A_STEP") (class "Default")
      (node (ref "R62") (pin "1") (pinfunction "1_1") (pintype "passive"))
      (node (ref "U3") (pin "115") (pinfunction "P6_7_115") (pintype "bidirectional"))
    )
    (net (code "287") (name "Y_B_DIR") (class "Default")
      (node (ref "R69") (pin "1") (pinfunction "1_1") (pintype "passive"))
      (node (ref "U3") (pin "108") (pinfunction "PA_9_108") (pintype "bidirectional"))
    )
    (net (code "288") (name "Y_B_ENABLE") (class "Default")
      (node (ref "R70") (pin "1") (pinfunction "1_1") (pintype "passive"))
      (node (ref "U3") (pin "107") (pinfunction "PA_8_107") (pintype "bidirectional"))
    )
    (net (code "289") (name "Y_B_HLFB_OUT") (class "Default")
      (node (ref "J18") (pin "5") (pinfunction "5-HLFB-_5") (pintype "passive"))
    )
    (net (code "290") (name "Y_B_MI_DIR") (class "Default")
      (node (ref "J18") (pin "7") (pinfunction "7-INPUT_A-_7") (pintype "passive"))
      (node (ref "R71") (pin "1") (pinfunction "1_1") (pintype "passive"))
      (node (ref "U26") (pin "3") (pinfunction "C(3)_3") (pintype "input"))
    )
    (net (code "291") (name "Y_B_MI_ENABLE") (class "Default")
      (node (ref "J18") (pin "8") (pinfunction "8-ENABLE-_8") (pintype "passive"))
      (node (ref "R72") (pin "1") (pinfunction "1_1") (pintype "passive"))
      (node (ref "U27") (pin "3") (pinfunction "C(3)_3") (pintype "input"))
    )
    (net (code "292") (name "Y_B_MI_STEP") (class "Default")
      (node (ref "J18") (pin "6") (pinfunction "6-INPUT_B-_6") (pintype "passive"))
      (node (ref "R67") (pin "1") (pinfunction "1_1") (pintype "passive"))
      (node (ref "U25") (pin "3") (pinfunction "C(3)_3") (pintype "input"))
    )
    (net (code "293") (name "Y_B_STEP") (class "Default")
      (node (ref "R68") (pin "1") (pinfunction "1_1") (pintype "passive"))
      (node (ref "U3") (pin "109") (pinfunction "PA_10_109") (pintype "bidirectional"))
    )
    (net (code "294") (name "Z_A_DIR") (class "Default")
      (node (ref "R87") (pin "1") (pinfunction "1_1") (pintype "passive"))
      (node (ref "U3") (pin "105") (pinfunction "P6_14_105") (pintype "bidirectional"))
    )
    (net (code "295") (name "Z_A_ENABLE") (class "Default")
      (node (ref "R88") (pin "1") (pinfunction "1_1") (pintype "passive"))
      (node (ref "U3") (pin "104") (pinfunction "P6_13_104") (pintype "bidirectional"))
    )
    (net (code "296") (name "Z_A_HLFB_OUT") (class "Default")
      (node (ref "J21") (pin "5") (pinfunction "5-HLFB-_5") (pintype "passive"))
    )
    (net (code "297") (name "Z_A_MI_DIR") (class "Default")
      (node (ref "J21") (pin "7") (pinfunction "7-INPUT_A-_7") (pintype "passive"))
      (node (ref "R89") (pin "1") (pinfunction "1_1") (pintype "passive"))
      (node (ref "U35") (pin "3") (pinfunction "C(3)_3") (pintype "input"))
    )
    (net (code "298") (name "Z_A_MI_ENABLE") (class "Default")
      (node (ref "J21") (pin "8") (pinfunction "8-ENABLE-_8") (pintype "passive"))
      (node (ref "R90") (pin "1") (pinfunction "1_1") (pintype "passive"))
      (node (ref "U36") (pin "3") (pinfunction "C(3)_3") (pintype "input"))
    )
    (net (code "299") (name "Z_A_MI_STEP") (class "Default")
      (node (ref "J21") (pin "6") (pinfunction "6-INPUT_B-_6") (pintype "passive"))
      (node (ref "R85") (pin "1") (pinfunction "1_1") (pintype "passive"))
      (node (ref "U34") (pin "3") (pinfunction "C(3)_3") (pintype "input"))
    )
    (net (code "300") (name "Z_A_STEP") (class "Default")
      (node (ref "R86") (pin "1") (pinfunction "1_1") (pintype "passive"))
      (node (ref "U3") (pin "106") (pinfunction "P6_15_106") (pintype "bidirectional"))
    )
    (net (code "301") (name "Z_B_DIR") (class "Default")
      (node (ref "R93") (pin "1") (pinfunction "1_1") (pintype "passive"))
      (node (ref "U3") (pin "102") (pinfunction "P6_11_102") (pintype "bidirectional"))
    )
    (net (code "302") (name "Z_B_ENABLE") (class "Default")
      (node (ref "R94") (pin "1") (pinfunction "1_1") (pintype "passive"))
      (node (ref "U3") (pin "101") (pinfunction "P6_10_101") (pintype "bidirectional"))
    )
    (net (code "303") (name "Z_B_HLFB_OUT") (class "Default")
      (node (ref "J22") (pin "5") (pinfunction "5-HLFB-_5") (pintype "passive"))
    )
    (net (code "304") (name "Z_B_MI_DIR") (class "Default")
      (node (ref "J22") (pin "7") (pinfunction "7-INPUT_A-_7") (pintype "passive"))
      (node (ref "R95") (pin "1") (pinfunction "1_1") (pintype "passive"))
      (node (ref "U38") (pin "3") (pinfunction "C(3)_3") (pintype "input"))
    )
    (net (code "305") (name "Z_B_MI_ENABLE") (class "Default")
      (node (ref "J22") (pin "8") (pinfunction "8-ENABLE-_8") (pintype "passive"))
      (node (ref "R96") (pin "1") (pinfunction "1_1") (pintype "passive"))
      (node (ref "U39") (pin "3") (pinfunction "C(3)_3") (pintype "input"))
    )
    (net (code "306") (name "Z_B_MI_STEP") (class "Default")
      (node (ref "J22") (pin "6") (pinfunction "6-INPUT_B-_6") (pintype "passive"))
      (node (ref "R91") (pin "1") (pinfunction "1_1") (pintype "passive"))
      (node (ref "U37") (pin "3") (pinfunction "C(3)_3") (pintype "input"))
    )
    (net (code "307") (name "Z_B_STEP") (class "Default")
      (node (ref "R92") (pin "1") (pinfunction "1_1") (pintype "passive"))
      (node (ref "U3") (pin "103") (pinfunction "P6_12_103") (pintype "bidirectional"))
    )
    (net (code "308") (name "unconnected-(U3-VBAT-Pad18)") (class "Default")
      (node (ref "U3") (pin "18") (pinfunction "VBAT_18") (pintype "bidirectional"))
    )
  )
)
